# FPGA_SUP.net
KiCad netlist of a schematic drawn in Altium Designer
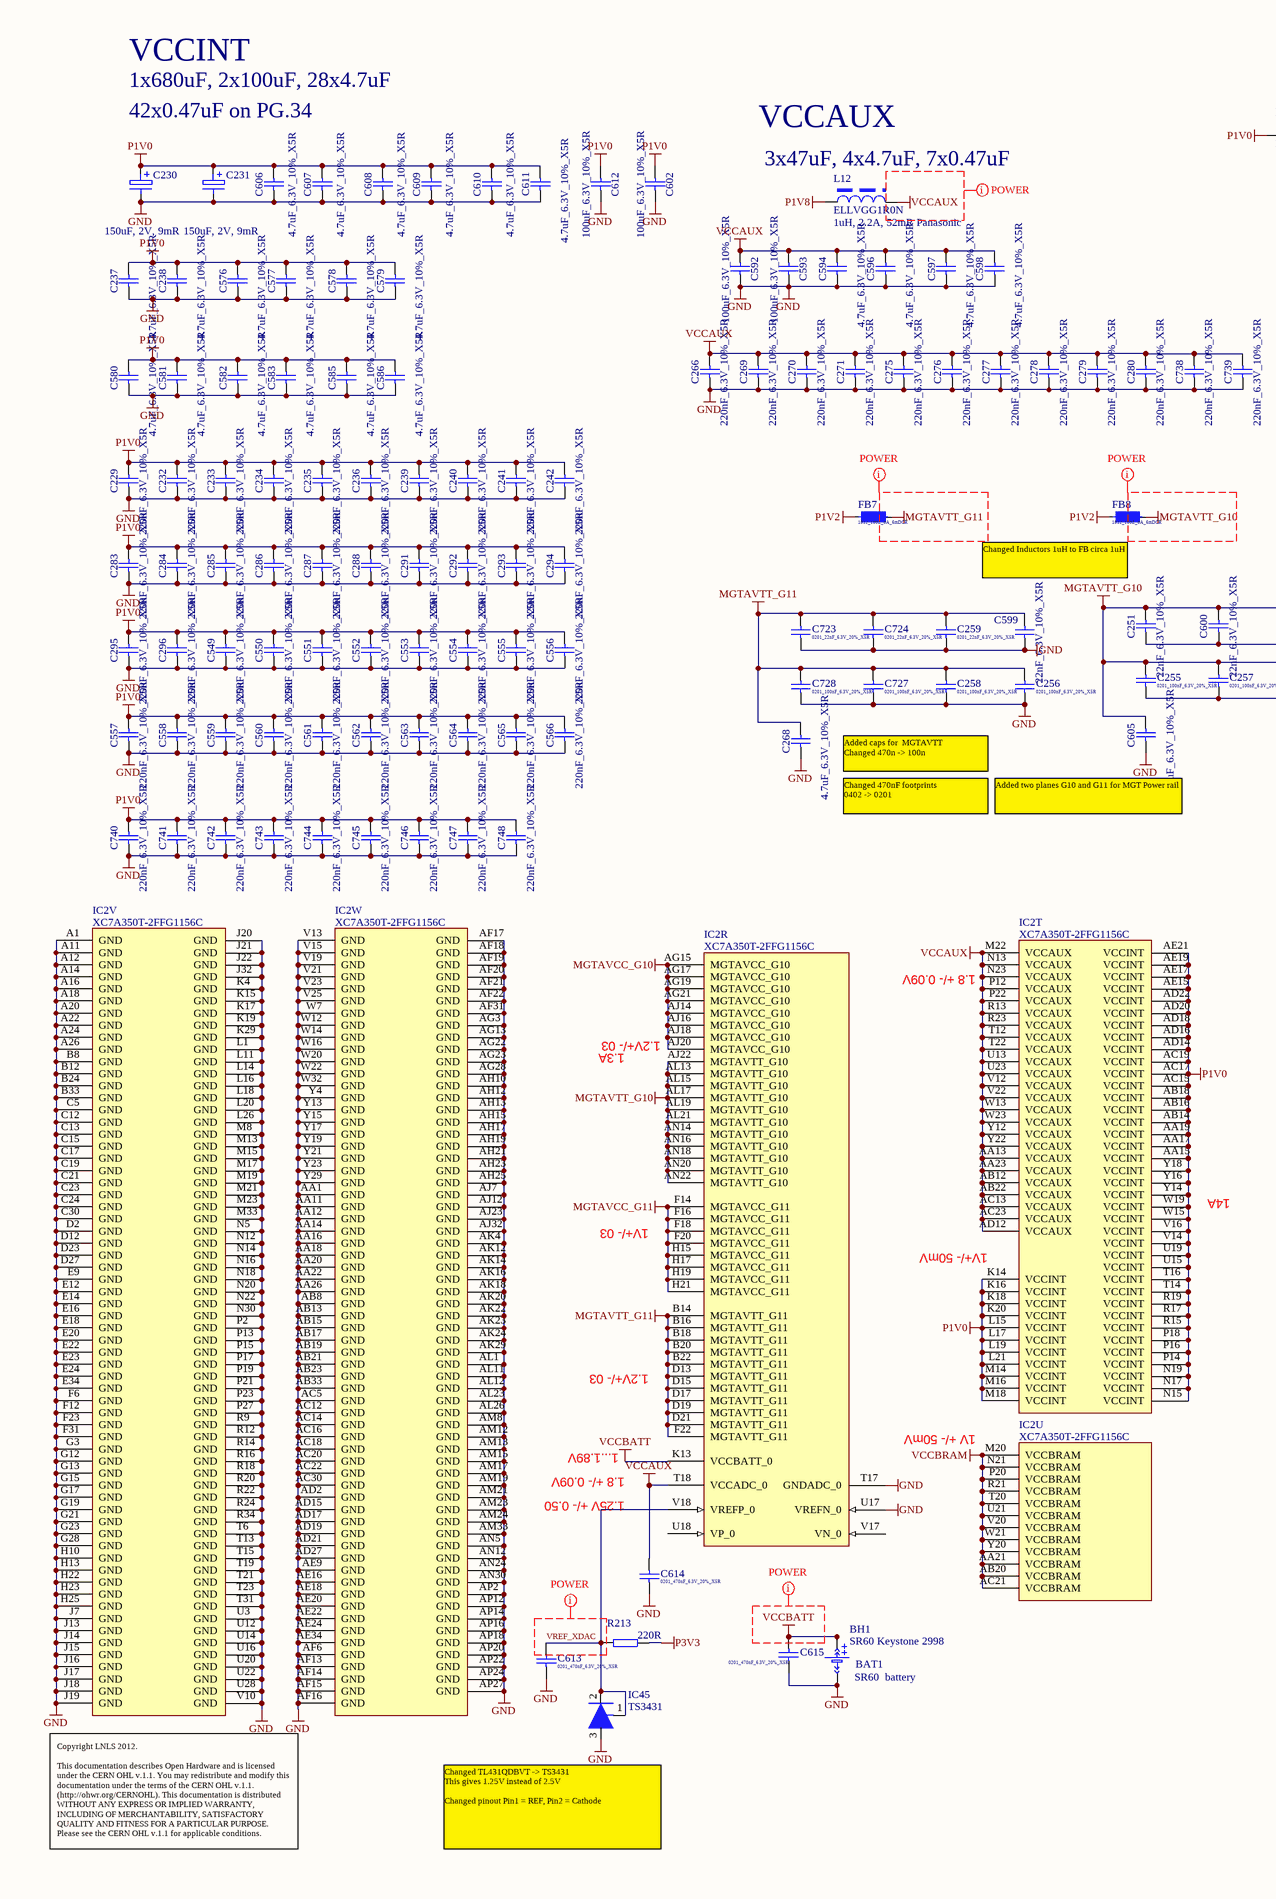
[diagram p0: FPGA_SUP.SchDoc, left]
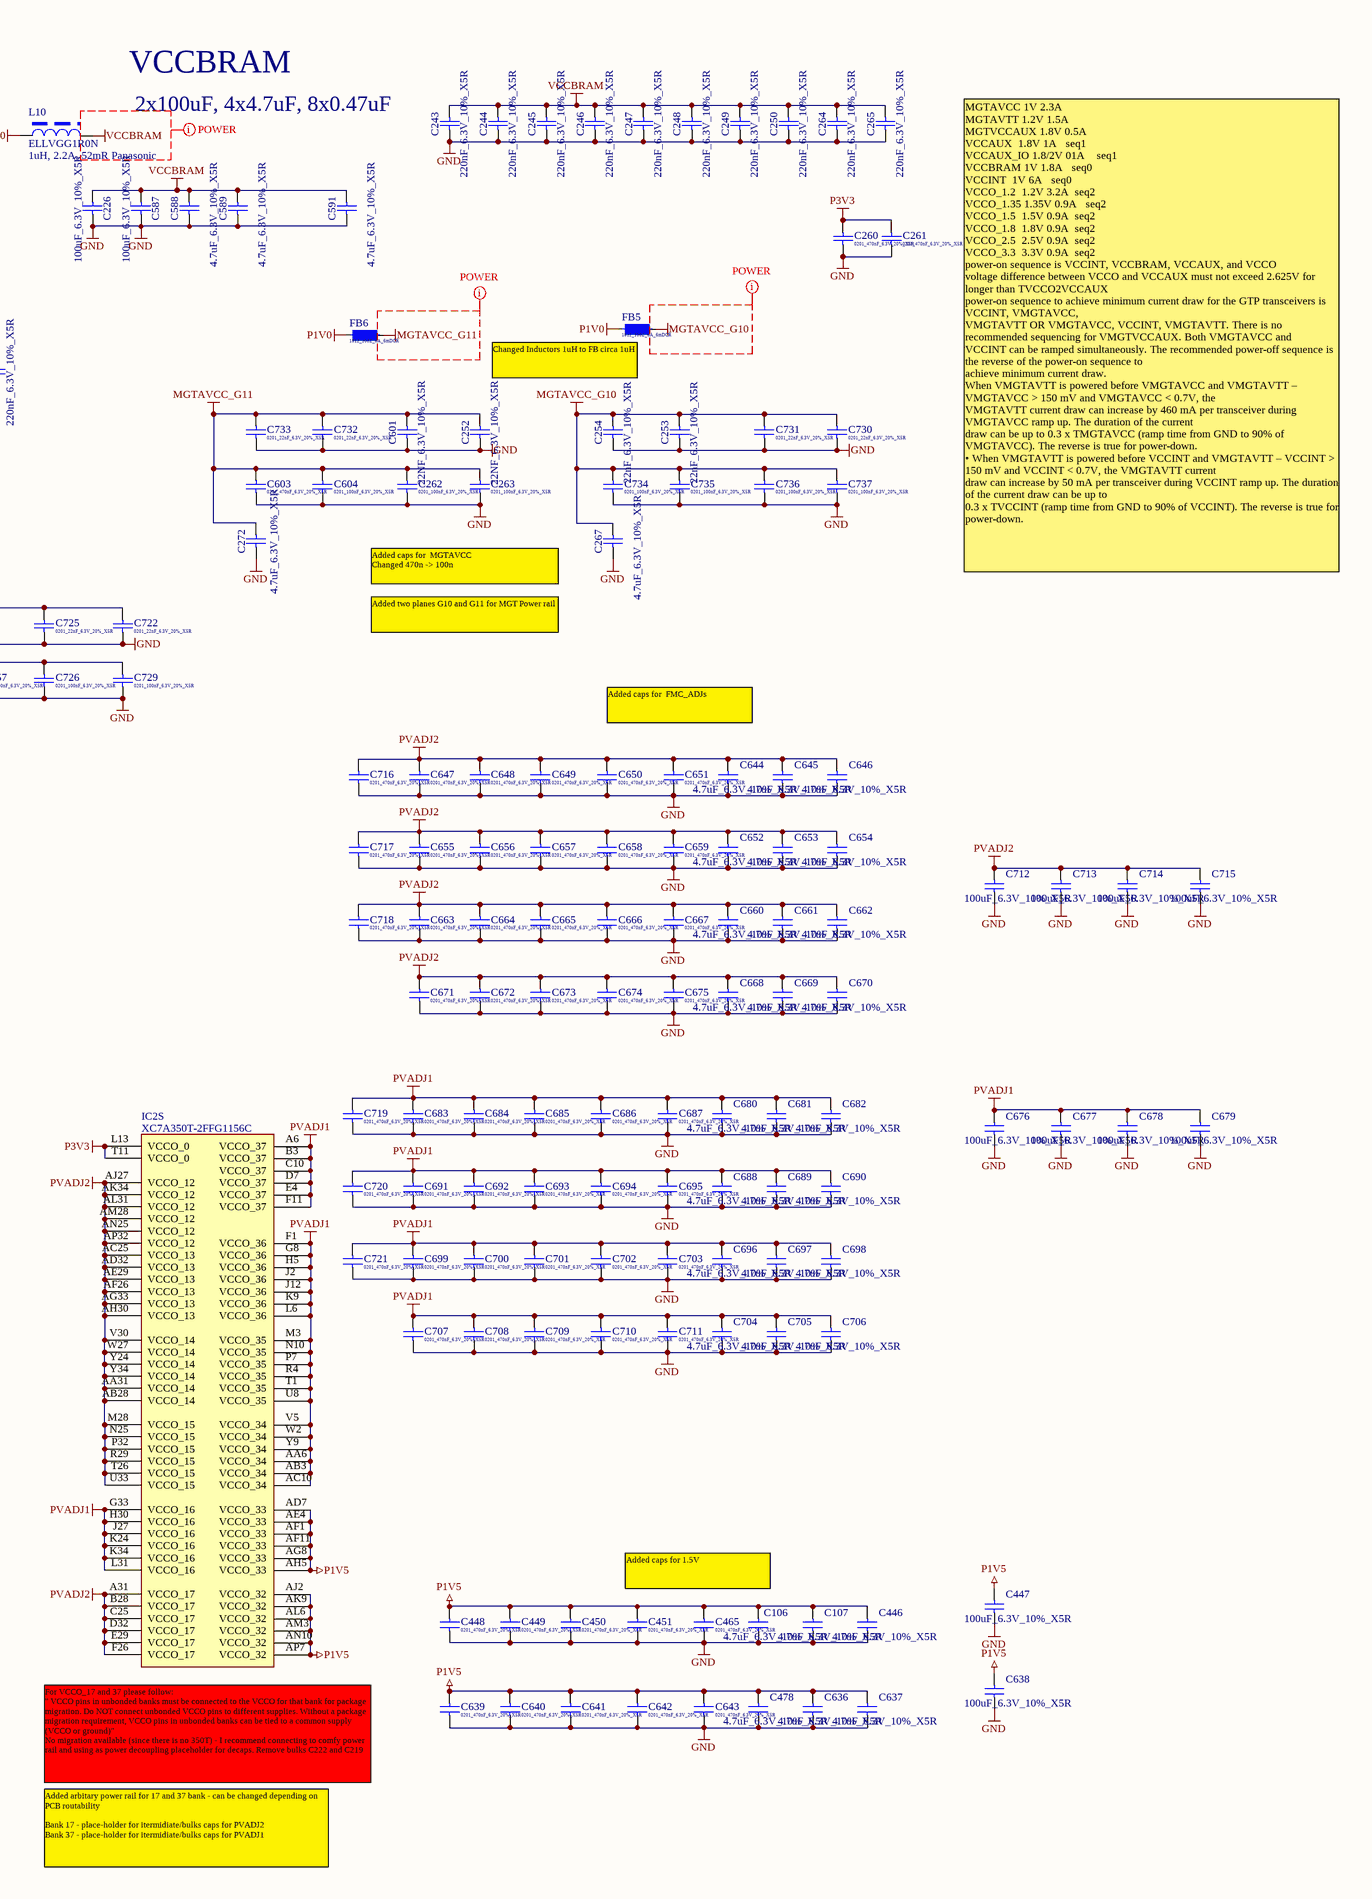
[diagram p1: FPGA_SUP.SchDoc, right]

(export (version "E")
  (design (tool "Eeschema 10.0.6"))
  (components
    (comp (ref "BAT1")
      (value "SR60  battery")
      (footprint "SR60")
      (description "SR60 6.8x2.15mm Battery 1.5V, 15mAh")
      (libsource (lib "LIBRARY_SCH") (part "BATTERY_SR60"))
    )
    (comp (ref "BH1")
      (value "SR60 Keystone 2998")
      (footprint "keystone_2998")
      (description "SR60 Battery 1.5V 17mAh (Farnell: 1854967)")
      (libsource (lib "LIBRARY_SCH") (part "BATTERY_HOLD_SR60"))
    )
    (comp (ref "C106")
      (value "4.7uF_6.3V_10%_X5R")
      (footprint "CAPC1608X87N")
      (description "Non-polarised capacitor")
      (fields
        (field (name "PART NUMBER") "CC0603_4.7UF_6.3V_10%_X5R")
        (field (name "VOLTAGE") "6.3V")
        (field (name "AUTHOR") "CERN DEM JLC")
      )
      (libsource (lib "Capacitors") (part "Capacitor - non polarized"))
    )
    (comp (ref "C107")
      (value "4.7uF_6.3V_10%_X5R")
      (footprint "CAPC1608X87N")
      (description "Non-polarised capacitor")
      (fields
        (field (name "PART NUMBER") "CC0603_4.7UF_6.3V_10%_X5R")
        (field (name "VOLTAGE") "6.3V")
        (field (name "AUTHOR") "CERN DEM JLC")
      )
      (libsource (lib "Capacitors") (part "Capacitor - non polarized"))
    )
    (comp (ref "C226")
      (value "100uF_6.3V_10%_X5R")
      (footprint "CAPC3225X270N")
      (description "Non-polarised capacitor")
      (fields
        (field (name "PART NUMBER") "CC1210_100UF_6.3V_20%_X5R")
        (field (name "VOLTAGE") "6.3V")
        (field (name "AUTHOR") "CERN DEM JLC")
      )
      (libsource (lib "Capacitors") (part "Capacitor - non polarized"))
    )
    (comp (ref "C229")
      (value "220nF_6.3V_10%_X5R")
      (footprint "CAPC0603X33N")
      (description "Non-polarised capacitor")
      (fields
        (field (name "PART NUMBER") "CC0201_220NF_6.3V_20%_X5R")
        (field (name "VOLTAGE") "6.3V")
        (field (name "AUTHOR") "CERN DEM JLC")
      )
      (libsource (lib "Capacitors") (part "Capacitor - non polarized"))
    )
    (comp (ref "C230")
      (value "150uF, 2V, 9mR")
      (footprint "2917_POLY")
      (description "POLY, 150uF, 2V, ESR: 9mR")
      (fields (field (name "Comment") "ECASD40D157M009K00"))
      (libsource (lib "LIBRARY_SCH") (part "CAP_POLYMER_SMDD"))
    )
    (comp (ref "C231")
      (value "150uF, 2V, 9mR")
      (footprint "2917_POLY")
      (description "POLY, 150uF, 2V, ESR: 9mR")
      (fields (field (name "Comment") "ECASD40D157M009K00"))
      (libsource (lib "LIBRARY_SCH") (part "CAP_POLYMER_SMDD"))
    )
    (comp (ref "C232")
      (value "220nF_6.3V_10%_X5R")
      (footprint "CAPC0603X33N")
      (description "Non-polarised capacitor")
      (fields
        (field (name "PART NUMBER") "CC0201_220NF_6.3V_20%_X5R")
        (field (name "VOLTAGE") "6.3V")
        (field (name "AUTHOR") "CERN DEM JLC")
      )
      (libsource (lib "Capacitors") (part "Capacitor - non polarized"))
    )
    (comp (ref "C233")
      (value "220nF_6.3V_10%_X5R")
      (footprint "CAPC0603X33N")
      (description "Non-polarised capacitor")
      (fields
        (field (name "PART NUMBER") "CC0201_220NF_6.3V_20%_X5R")
        (field (name "VOLTAGE") "6.3V")
        (field (name "AUTHOR") "CERN DEM JLC")
      )
      (libsource (lib "Capacitors") (part "Capacitor - non polarized"))
    )
    (comp (ref "C234")
      (value "220nF_6.3V_10%_X5R")
      (footprint "CAPC0603X33N")
      (description "Non-polarised capacitor")
      (fields
        (field (name "PART NUMBER") "CC0201_220NF_6.3V_20%_X5R")
        (field (name "VOLTAGE") "6.3V")
        (field (name "AUTHOR") "CERN DEM JLC")
      )
      (libsource (lib "Capacitors") (part "Capacitor - non polarized"))
    )
    (comp (ref "C235")
      (value "220nF_6.3V_10%_X5R")
      (footprint "CAPC0603X33N")
      (description "Non-polarised capacitor")
      (fields
        (field (name "PART NUMBER") "CC0201_220NF_6.3V_20%_X5R")
        (field (name "VOLTAGE") "6.3V")
        (field (name "AUTHOR") "CERN DEM JLC")
      )
      (libsource (lib "Capacitors") (part "Capacitor - non polarized"))
    )
    (comp (ref "C236")
      (value "220nF_6.3V_10%_X5R")
      (footprint "CAPC0603X33N")
      (description "Non-polarised capacitor")
      (fields
        (field (name "PART NUMBER") "CC0201_220NF_6.3V_20%_X5R")
        (field (name "VOLTAGE") "6.3V")
        (field (name "AUTHOR") "CERN DEM JLC")
      )
      (libsource (lib "Capacitors") (part "Capacitor - non polarized"))
    )
    (comp (ref "C237")
      (value "4.7uF_6.3V_10%_X5R")
      (footprint "CAPC1608X87N")
      (description "Non-polarised capacitor")
      (fields
        (field (name "PART NUMBER") "CC0603_4.7UF_6.3V_10%_X5R")
        (field (name "VOLTAGE") "6.3V")
        (field (name "AUTHOR") "CERN DEM JLC")
      )
      (libsource (lib "Capacitors") (part "Capacitor - non polarized"))
    )
    (comp (ref "C238")
      (value "4.7uF_6.3V_10%_X5R")
      (footprint "CAPC1608X87N")
      (description "Non-polarised capacitor")
      (fields
        (field (name "PART NUMBER") "CC0603_4.7UF_6.3V_10%_X5R")
        (field (name "VOLTAGE") "6.3V")
        (field (name "AUTHOR") "CERN DEM JLC")
      )
      (libsource (lib "Capacitors") (part "Capacitor - non polarized"))
    )
    (comp (ref "C239")
      (value "220nF_6.3V_10%_X5R")
      (footprint "CAPC0603X33N")
      (description "Non-polarised capacitor")
      (fields
        (field (name "PART NUMBER") "CC0201_220NF_6.3V_20%_X5R")
        (field (name "VOLTAGE") "6.3V")
        (field (name "AUTHOR") "CERN DEM JLC")
      )
      (libsource (lib "Capacitors") (part "Capacitor - non polarized"))
    )
    (comp (ref "C240")
      (value "220nF_6.3V_10%_X5R")
      (footprint "CAPC0603X33N")
      (description "Non-polarised capacitor")
      (fields
        (field (name "PART NUMBER") "CC0201_220NF_6.3V_20%_X5R")
        (field (name "VOLTAGE") "6.3V")
        (field (name "AUTHOR") "CERN DEM JLC")
      )
      (libsource (lib "Capacitors") (part "Capacitor - non polarized"))
    )
    (comp (ref "C241")
      (value "220nF_6.3V_10%_X5R")
      (footprint "CAPC0603X33N")
      (description "Non-polarised capacitor")
      (fields
        (field (name "PART NUMBER") "CC0201_220NF_6.3V_20%_X5R")
        (field (name "VOLTAGE") "6.3V")
        (field (name "AUTHOR") "CERN DEM JLC")
      )
      (libsource (lib "Capacitors") (part "Capacitor - non polarized"))
    )
    (comp (ref "C242")
      (value "220nF_6.3V_10%_X5R")
      (footprint "CAPC0603X33N")
      (description "Non-polarised capacitor")
      (fields
        (field (name "PART NUMBER") "CC0201_220NF_6.3V_20%_X5R")
        (field (name "VOLTAGE") "6.3V")
        (field (name "AUTHOR") "CERN DEM JLC")
      )
      (libsource (lib "Capacitors") (part "Capacitor - non polarized"))
    )
    (comp (ref "C243")
      (value "220nF_6.3V_10%_X5R")
      (footprint "CAPC0603X33N")
      (description "Non-polarised capacitor")
      (fields
        (field (name "PART NUMBER") "CC0201_220NF_6.3V_20%_X5R")
        (field (name "VOLTAGE") "6.3V")
        (field (name "AUTHOR") "CERN DEM JLC")
      )
      (libsource (lib "Capacitors") (part "Capacitor - non polarized"))
    )
    (comp (ref "C244")
      (value "220nF_6.3V_10%_X5R")
      (footprint "CAPC0603X33N")
      (description "Non-polarised capacitor")
      (fields
        (field (name "PART NUMBER") "CC0201_220NF_6.3V_20%_X5R")
        (field (name "VOLTAGE") "6.3V")
        (field (name "AUTHOR") "CERN DEM JLC")
      )
      (libsource (lib "Capacitors") (part "Capacitor - non polarized"))
    )
    (comp (ref "C245")
      (value "220nF_6.3V_10%_X5R")
      (footprint "CAPC0603X33N")
      (description "Non-polarised capacitor")
      (fields
        (field (name "PART NUMBER") "CC0201_220NF_6.3V_20%_X5R")
        (field (name "VOLTAGE") "6.3V")
        (field (name "AUTHOR") "CERN DEM JLC")
      )
      (libsource (lib "Capacitors") (part "Capacitor - non polarized"))
    )
    (comp (ref "C246")
      (value "220nF_6.3V_10%_X5R")
      (footprint "CAPC0603X33N")
      (description "Non-polarised capacitor")
      (fields
        (field (name "PART NUMBER") "CC0201_220NF_6.3V_20%_X5R")
        (field (name "VOLTAGE") "6.3V")
        (field (name "AUTHOR") "CERN DEM JLC")
      )
      (libsource (lib "Capacitors") (part "Capacitor - non polarized"))
    )
    (comp (ref "C247")
      (value "220nF_6.3V_10%_X5R")
      (footprint "CAPC0603X33N")
      (description "Non-polarised capacitor")
      (fields
        (field (name "PART NUMBER") "CC0201_220NF_6.3V_20%_X5R")
        (field (name "VOLTAGE") "6.3V")
        (field (name "AUTHOR") "CERN DEM JLC")
      )
      (libsource (lib "Capacitors") (part "Capacitor - non polarized"))
    )
    (comp (ref "C248")
      (value "220nF_6.3V_10%_X5R")
      (footprint "CAPC0603X33N")
      (description "Non-polarised capacitor")
      (fields
        (field (name "PART NUMBER") "CC0201_220NF_6.3V_20%_X5R")
        (field (name "VOLTAGE") "6.3V")
        (field (name "AUTHOR") "CERN DEM JLC")
      )
      (libsource (lib "Capacitors") (part "Capacitor - non polarized"))
    )
    (comp (ref "C249")
      (value "220nF_6.3V_10%_X5R")
      (footprint "CAPC0603X33N")
      (description "Non-polarised capacitor")
      (fields
        (field (name "PART NUMBER") "CC0201_220NF_6.3V_20%_X5R")
        (field (name "VOLTAGE") "6.3V")
        (field (name "AUTHOR") "CERN DEM JLC")
      )
      (libsource (lib "Capacitors") (part "Capacitor - non polarized"))
    )
    (comp (ref "C250")
      (value "220nF_6.3V_10%_X5R")
      (footprint "CAPC0603X33N")
      (description "Non-polarised capacitor")
      (fields
        (field (name "PART NUMBER") "CC0201_220NF_6.3V_20%_X5R")
        (field (name "VOLTAGE") "6.3V")
        (field (name "AUTHOR") "CERN DEM JLC")
      )
      (libsource (lib "Capacitors") (part "Capacitor - non polarized"))
    )
    (comp (ref "C251")
      (value "22nF_6.3V_10%_X5R")
      (footprint "CAPC0603X33N")
      (description "Non-polarised capacitor")
      (fields
        (field (name "PART NUMBER") "CC0201_22NF_6.3V_10%_X5R")
        (field (name "VOLTAGE") "6.3V")
        (field (name "AUTHOR") "CERN DEM JLC")
      )
      (libsource (lib "Capacitors") (part "Capacitor - non polarized"))
    )
    (comp (ref "C252")
      (value "22NF_6.3V_10%_X5R")
      (footprint "CAPC0603X33N")
      (description "Non-polarised capacitor")
      (fields
        (field (name "PART NUMBER") "CC0201_22NF_6.3V_10%_X5R")
        (field (name "VOLTAGE") "6.3V")
        (field (name "AUTHOR") "CERN DEM JLC")
      )
      (libsource (lib "Capacitors") (part "Capacitor - non polarized"))
    )
    (comp (ref "C253")
      (value "22nF_6.3V_10%_X5R")
      (footprint "CAPC0603X33N")
      (description "Non-polarised capacitor")
      (fields
        (field (name "PART NUMBER") "CC0201_22NF_6.3V_10%_X5R")
        (field (name "VOLTAGE") "6.3V")
        (field (name "AUTHOR") "CERN DEM JLC")
      )
      (libsource (lib "Capacitors") (part "Capacitor - non polarized"))
    )
    (comp (ref "C254")
      (value "22nF_6.3V_10%_X5R")
      (footprint "CAPC0603X33N")
      (description "Non-polarised capacitor")
      (fields
        (field (name "PART NUMBER") "CC0201_22NF_6.3V_10%_X5R")
        (field (name "VOLTAGE") "6.3V")
        (field (name "AUTHOR") "CERN DEM JLC")
      )
      (libsource (lib "Capacitors") (part "Capacitor - non polarized"))
    )
    (comp (ref "C255")
      (value "0201_100nF_6.3V_20%_X5R")
      (footprint "CAPC0603X33N")
      (fields (field (name "PART NUMBER") "Ceramic_0201"))
      (libsource (lib "Capacitors") (part "Capacitor"))
    )
    (comp (ref "C256")
      (value "0201_100nF_6.3V_20%_X5R")
      (footprint "CAPC0603X33N")
      (fields (field (name "PART NUMBER") "Ceramic_0201"))
      (libsource (lib "Capacitors") (part "Capacitor"))
    )
    (comp (ref "C257")
      (value "0201_100nF_6.3V_20%_X5R")
      (footprint "CAPC0603X33N")
      (fields (field (name "PART NUMBER") "Ceramic_0201"))
      (libsource (lib "Capacitors") (part "Capacitor"))
    )
    (comp (ref "C258")
      (value "0201_100nF_6.3V_20%_X5R")
      (footprint "CAPC0603X33N")
      (fields (field (name "PART NUMBER") "Ceramic_0201"))
      (libsource (lib "Capacitors") (part "Capacitor"))
    )
    (comp (ref "C259")
      (value "0201_22nF_6.3V_20%_X5R")
      (footprint "CAPC0603X33N")
      (fields (field (name "PART NUMBER") "Ceramic_0201"))
      (libsource (lib "Capacitors") (part "Capacitor"))
    )
    (comp (ref "C260")
      (value "0201_470nF_6.3V_20%_X5R")
      (footprint "CAPC0603X33N")
      (fields (field (name "PART NUMBER") "Ceramic_0201"))
      (libsource (lib "Capacitors") (part "Capacitor"))
    )
    (comp (ref "C261")
      (value "0201_470nF_6.3V_20%_X5R")
      (footprint "CAPC0603X33N")
      (fields (field (name "PART NUMBER") "Ceramic_0201"))
      (libsource (lib "Capacitors") (part "Capacitor"))
    )
    (comp (ref "C262")
      (value "0201_100nF_6.3V_20%_X5R")
      (footprint "CAPC0603X33N")
      (fields (field (name "PART NUMBER") "Ceramic_0201"))
      (libsource (lib "Capacitors") (part "Capacitor"))
    )
    (comp (ref "C263")
      (value "0201_100nF_6.3V_20%_X5R")
      (footprint "CAPC0603X33N")
      (fields (field (name "PART NUMBER") "Ceramic_0201"))
      (libsource (lib "Capacitors") (part "Capacitor"))
    )
    (comp (ref "C264")
      (value "220nF_6.3V_10%_X5R")
      (footprint "CAPC0603X33N")
      (description "Non-polarised capacitor")
      (fields
        (field (name "PART NUMBER") "CC0201_220NF_6.3V_20%_X5R")
        (field (name "VOLTAGE") "6.3V")
        (field (name "AUTHOR") "CERN DEM JLC")
      )
      (libsource (lib "Capacitors") (part "Capacitor - non polarized"))
    )
    (comp (ref "C265")
      (value "220nF_6.3V_10%_X5R")
      (footprint "CAPC0603X33N")
      (description "Non-polarised capacitor")
      (fields
        (field (name "PART NUMBER") "CC0201_220NF_6.3V_20%_X5R")
        (field (name "VOLTAGE") "6.3V")
        (field (name "AUTHOR") "CERN DEM JLC")
      )
      (libsource (lib "Capacitors") (part "Capacitor - non polarized"))
    )
    (comp (ref "C266")
      (value "220nF_6.3V_10%_X5R")
      (footprint "CAPC0603X33N")
      (description "Non-polarised capacitor")
      (fields
        (field (name "PART NUMBER") "CC0201_220NF_6.3V_20%_X5R")
        (field (name "VOLTAGE") "6.3V")
        (field (name "AUTHOR") "CERN DEM JLC")
      )
      (libsource (lib "Capacitors") (part "Capacitor - non polarized"))
    )
    (comp (ref "C267")
      (value "4.7uF_6.3V_10%_X5R")
      (footprint "CAPC1608X87N")
      (description "Non-polarised capacitor")
      (fields
        (field (name "PART NUMBER") "CC0603_4.7UF_6.3V_10%_X5R")
        (field (name "VOLTAGE") "6.3V")
        (field (name "AUTHOR") "CERN DEM JLC")
      )
      (libsource (lib "Capacitors") (part "Capacitor - non polarized"))
    )
    (comp (ref "C268")
      (value "4.7uF_6.3V_10%_X5R")
      (footprint "CAPC1608X87N")
      (description "Non-polarised capacitor")
      (fields
        (field (name "PART NUMBER") "CC0603_4.7UF_6.3V_10%_X5R")
        (field (name "VOLTAGE") "6.3V")
        (field (name "AUTHOR") "CERN DEM JLC")
      )
      (libsource (lib "Capacitors") (part "Capacitor - non polarized"))
    )
    (comp (ref "C269")
      (value "220nF_6.3V_10%_X5R")
      (footprint "CAPC0603X33N")
      (description "Non-polarised capacitor")
      (fields
        (field (name "PART NUMBER") "CC0201_220NF_6.3V_20%_X5R")
        (field (name "VOLTAGE") "6.3V")
        (field (name "AUTHOR") "CERN DEM JLC")
      )
      (libsource (lib "Capacitors") (part "Capacitor - non polarized"))
    )
    (comp (ref "C270")
      (value "220nF_6.3V_10%_X5R")
      (footprint "CAPC0603X33N")
      (description "Non-polarised capacitor")
      (fields
        (field (name "PART NUMBER") "CC0201_220NF_6.3V_20%_X5R")
        (field (name "VOLTAGE") "6.3V")
        (field (name "AUTHOR") "CERN DEM JLC")
      )
      (libsource (lib "Capacitors") (part "Capacitor - non polarized"))
    )
    (comp (ref "C271")
      (value "220nF_6.3V_10%_X5R")
      (footprint "CAPC0603X33N")
      (description "Non-polarised capacitor")
      (fields
        (field (name "PART NUMBER") "CC0201_220NF_6.3V_20%_X5R")
        (field (name "VOLTAGE") "6.3V")
        (field (name "AUTHOR") "CERN DEM JLC")
      )
      (libsource (lib "Capacitors") (part "Capacitor - non polarized"))
    )
    (comp (ref "C272")
      (value "4.7uF_6.3V_10%_X5R")
      (footprint "CAPC1608X87N")
      (description "Non-polarised capacitor")
      (fields
        (field (name "PART NUMBER") "CC0603_4.7UF_6.3V_10%_X5R")
        (field (name "VOLTAGE") "6.3V")
        (field (name "AUTHOR") "CERN DEM JLC")
      )
      (libsource (lib "Capacitors") (part "Capacitor - non polarized"))
    )
    (comp (ref "C275")
      (value "220nF_6.3V_10%_X5R")
      (footprint "CAPC0603X33N")
      (description "Non-polarised capacitor")
      (fields
        (field (name "PART NUMBER") "CC0201_220NF_6.3V_20%_X5R")
        (field (name "VOLTAGE") "6.3V")
        (field (name "AUTHOR") "CERN DEM JLC")
      )
      (libsource (lib "Capacitors") (part "Capacitor - non polarized"))
    )
    (comp (ref "C276")
      (value "220nF_6.3V_10%_X5R")
      (footprint "CAPC0603X33N")
      (description "Non-polarised capacitor")
      (fields
        (field (name "PART NUMBER") "CC0201_220NF_6.3V_20%_X5R")
        (field (name "VOLTAGE") "6.3V")
        (field (name "AUTHOR") "CERN DEM JLC")
      )
      (libsource (lib "Capacitors") (part "Capacitor - non polarized"))
    )
    (comp (ref "C277")
      (value "220nF_6.3V_10%_X5R")
      (footprint "CAPC0603X33N")
      (description "Non-polarised capacitor")
      (fields
        (field (name "PART NUMBER") "CC0201_220NF_6.3V_20%_X5R")
        (field (name "VOLTAGE") "6.3V")
        (field (name "AUTHOR") "CERN DEM JLC")
      )
      (libsource (lib "Capacitors") (part "Capacitor - non polarized"))
    )
    (comp (ref "C278")
      (value "220nF_6.3V_10%_X5R")
      (footprint "CAPC0603X33N")
      (description "Non-polarised capacitor")
      (fields
        (field (name "PART NUMBER") "CC0201_220NF_6.3V_20%_X5R")
        (field (name "VOLTAGE") "6.3V")
        (field (name "AUTHOR") "CERN DEM JLC")
      )
      (libsource (lib "Capacitors") (part "Capacitor - non polarized"))
    )
    (comp (ref "C279")
      (value "220nF_6.3V_10%_X5R")
      (footprint "CAPC0603X33N")
      (description "Non-polarised capacitor")
      (fields
        (field (name "PART NUMBER") "CC0201_220NF_6.3V_20%_X5R")
        (field (name "VOLTAGE") "6.3V")
        (field (name "AUTHOR") "CERN DEM JLC")
      )
      (libsource (lib "Capacitors") (part "Capacitor - non polarized"))
    )
    (comp (ref "C280")
      (value "220nF_6.3V_10%_X5R")
      (footprint "CAPC0603X33N")
      (description "Non-polarised capacitor")
      (fields
        (field (name "PART NUMBER") "CC0201_220NF_6.3V_20%_X5R")
        (field (name "VOLTAGE") "6.3V")
        (field (name "AUTHOR") "CERN DEM JLC")
      )
      (libsource (lib "Capacitors") (part "Capacitor - non polarized"))
    )
    (comp (ref "C283")
      (value "220nF_6.3V_10%_X5R")
      (footprint "CAPC0603X33N")
      (description "Non-polarised capacitor")
      (fields
        (field (name "PART NUMBER") "CC0201_220NF_6.3V_20%_X5R")
        (field (name "VOLTAGE") "6.3V")
        (field (name "AUTHOR") "CERN DEM JLC")
      )
      (libsource (lib "Capacitors") (part "Capacitor - non polarized"))
    )
    (comp (ref "C284")
      (value "220nF_6.3V_10%_X5R")
      (footprint "CAPC0603X33N")
      (description "Non-polarised capacitor")
      (fields
        (field (name "PART NUMBER") "CC0201_220NF_6.3V_20%_X5R")
        (field (name "VOLTAGE") "6.3V")
        (field (name "AUTHOR") "CERN DEM JLC")
      )
      (libsource (lib "Capacitors") (part "Capacitor - non polarized"))
    )
    (comp (ref "C285")
      (value "220nF_6.3V_10%_X5R")
      (footprint "CAPC0603X33N")
      (description "Non-polarised capacitor")
      (fields
        (field (name "PART NUMBER") "CC0201_220NF_6.3V_20%_X5R")
        (field (name "VOLTAGE") "6.3V")
        (field (name "AUTHOR") "CERN DEM JLC")
      )
      (libsource (lib "Capacitors") (part "Capacitor - non polarized"))
    )
    (comp (ref "C286")
      (value "220nF_6.3V_10%_X5R")
      (footprint "CAPC0603X33N")
      (description "Non-polarised capacitor")
      (fields
        (field (name "PART NUMBER") "CC0201_220NF_6.3V_20%_X5R")
        (field (name "VOLTAGE") "6.3V")
        (field (name "AUTHOR") "CERN DEM JLC")
      )
      (libsource (lib "Capacitors") (part "Capacitor - non polarized"))
    )
    (comp (ref "C287")
      (value "220nF_6.3V_10%_X5R")
      (footprint "CAPC0603X33N")
      (description "Non-polarised capacitor")
      (fields
        (field (name "PART NUMBER") "CC0201_220NF_6.3V_20%_X5R")
        (field (name "VOLTAGE") "6.3V")
        (field (name "AUTHOR") "CERN DEM JLC")
      )
      (libsource (lib "Capacitors") (part "Capacitor - non polarized"))
    )
    (comp (ref "C288")
      (value "220nF_6.3V_10%_X5R")
      (footprint "CAPC0603X33N")
      (description "Non-polarised capacitor")
      (fields
        (field (name "PART NUMBER") "CC0201_220NF_6.3V_20%_X5R")
        (field (name "VOLTAGE") "6.3V")
        (field (name "AUTHOR") "CERN DEM JLC")
      )
      (libsource (lib "Capacitors") (part "Capacitor - non polarized"))
    )
    (comp (ref "C291")
      (value "220nF_6.3V_10%_X5R")
      (footprint "CAPC0603X33N")
      (description "Non-polarised capacitor")
      (fields
        (field (name "PART NUMBER") "CC0201_220NF_6.3V_20%_X5R")
        (field (name "VOLTAGE") "6.3V")
        (field (name "AUTHOR") "CERN DEM JLC")
      )
      (libsource (lib "Capacitors") (part "Capacitor - non polarized"))
    )
    (comp (ref "C292")
      (value "220nF_6.3V_10%_X5R")
      (footprint "CAPC0603X33N")
      (description "Non-polarised capacitor")
      (fields
        (field (name "PART NUMBER") "CC0201_220NF_6.3V_20%_X5R")
        (field (name "VOLTAGE") "6.3V")
        (field (name "AUTHOR") "CERN DEM JLC")
      )
      (libsource (lib "Capacitors") (part "Capacitor - non polarized"))
    )
    (comp (ref "C293")
      (value "220nF_6.3V_10%_X5R")
      (footprint "CAPC0603X33N")
      (description "Non-polarised capacitor")
      (fields
        (field (name "PART NUMBER") "CC0201_220NF_6.3V_20%_X5R")
        (field (name "VOLTAGE") "6.3V")
        (field (name "AUTHOR") "CERN DEM JLC")
      )
      (libsource (lib "Capacitors") (part "Capacitor - non polarized"))
    )
    (comp (ref "C294")
      (value "220nF_6.3V_10%_X5R")
      (footprint "CAPC0603X33N")
      (description "Non-polarised capacitor")
      (fields
        (field (name "PART NUMBER") "CC0201_220NF_6.3V_20%_X5R")
        (field (name "VOLTAGE") "6.3V")
        (field (name "AUTHOR") "CERN DEM JLC")
      )
      (libsource (lib "Capacitors") (part "Capacitor - non polarized"))
    )
    (comp (ref "C295")
      (value "220nF_6.3V_10%_X5R")
      (footprint "CAPC0603X33N")
      (description "Non-polarised capacitor")
      (fields
        (field (name "PART NUMBER") "CC0201_220NF_6.3V_20%_X5R")
        (field (name "VOLTAGE") "6.3V")
        (field (name "AUTHOR") "CERN DEM JLC")
      )
      (libsource (lib "Capacitors") (part "Capacitor - non polarized"))
    )
    (comp (ref "C296")
      (value "220nF_6.3V_10%_X5R")
      (footprint "CAPC0603X33N")
      (description "Non-polarised capacitor")
      (fields
        (field (name "PART NUMBER") "CC0201_220NF_6.3V_20%_X5R")
        (field (name "VOLTAGE") "6.3V")
        (field (name "AUTHOR") "CERN DEM JLC")
      )
      (libsource (lib "Capacitors") (part "Capacitor - non polarized"))
    )
    (comp (ref "C446")
      (value "4.7uF_6.3V_10%_X5R")
      (footprint "CAPC1608X87N")
      (description "Non-polarised capacitor")
      (fields
        (field (name "PART NUMBER") "CC0603_4.7UF_6.3V_10%_X5R")
        (field (name "VOLTAGE") "6.3V")
        (field (name "AUTHOR") "CERN DEM JLC")
      )
      (libsource (lib "Capacitors") (part "Capacitor - non polarized"))
    )
    (comp (ref "C447")
      (value "100uF_6.3V_10%_X5R")
      (footprint "CAPC3225X270N")
      (description "Non-polarised capacitor")
      (fields
        (field (name "PART NUMBER") "CC1210_100UF_6.3V_20%_X5R")
        (field (name "VOLTAGE") "6.3V")
        (field (name "AUTHOR") "CERN DEM JLC")
      )
      (libsource (lib "Capacitors") (part "Capacitor - non polarized"))
    )
    (comp (ref "C448")
      (value "0201_470nF_6.3V_20%_X5R")
      (footprint "CAPC0603X33N")
      (fields (field (name "PART NUMBER") "Ceramic_0201"))
      (libsource (lib "Capacitors") (part "Capacitor"))
    )
    (comp (ref "C449")
      (value "0201_470nF_6.3V_20%_X5R")
      (footprint "CAPC0603X33N")
      (fields (field (name "PART NUMBER") "Ceramic_0201"))
      (libsource (lib "Capacitors") (part "Capacitor"))
    )
    (comp (ref "C450")
      (value "0201_470nF_6.3V_20%_X5R")
      (footprint "CAPC0603X33N")
      (fields (field (name "PART NUMBER") "Ceramic_0201"))
      (libsource (lib "Capacitors") (part "Capacitor"))
    )
    (comp (ref "C451")
      (value "0201_470nF_6.3V_20%_X5R")
      (footprint "CAPC0603X33N")
      (fields (field (name "PART NUMBER") "Ceramic_0201"))
      (libsource (lib "Capacitors") (part "Capacitor"))
    )
    (comp (ref "C465")
      (value "0201_470nF_6.3V_20%_X5R")
      (footprint "CAPC0603X33N")
      (fields (field (name "PART NUMBER") "Ceramic_0201"))
      (libsource (lib "Capacitors") (part "Capacitor"))
    )
    (comp (ref "C478")
      (value "4.7uF_6.3V_10%_X5R")
      (footprint "CAPC1608X87N")
      (description "Non-polarised capacitor")
      (fields
        (field (name "PART NUMBER") "CC0603_4.7UF_6.3V_10%_X5R")
        (field (name "VOLTAGE") "6.3V")
        (field (name "AUTHOR") "CERN DEM JLC")
      )
      (libsource (lib "Capacitors") (part "Capacitor - non polarized"))
    )
    (comp (ref "C549")
      (value "220nF_6.3V_10%_X5R")
      (footprint "CAPC0603X33N")
      (description "Non-polarised capacitor")
      (fields
        (field (name "PART NUMBER") "CC0201_220NF_6.3V_20%_X5R")
        (field (name "VOLTAGE") "6.3V")
        (field (name "AUTHOR") "CERN DEM JLC")
      )
      (libsource (lib "Capacitors") (part "Capacitor - non polarized"))
    )
    (comp (ref "C550")
      (value "220nF_6.3V_10%_X5R")
      (footprint "CAPC0603X33N")
      (description "Non-polarised capacitor")
      (fields
        (field (name "PART NUMBER") "CC0201_220NF_6.3V_20%_X5R")
        (field (name "VOLTAGE") "6.3V")
        (field (name "AUTHOR") "CERN DEM JLC")
      )
      (libsource (lib "Capacitors") (part "Capacitor - non polarized"))
    )
    (comp (ref "C551")
      (value "220nF_6.3V_10%_X5R")
      (footprint "CAPC0603X33N")
      (description "Non-polarised capacitor")
      (fields
        (field (name "PART NUMBER") "CC0201_220NF_6.3V_20%_X5R")
        (field (name "VOLTAGE") "6.3V")
        (field (name "AUTHOR") "CERN DEM JLC")
      )
      (libsource (lib "Capacitors") (part "Capacitor - non polarized"))
    )
    (comp (ref "C552")
      (value "220nF_6.3V_10%_X5R")
      (footprint "CAPC0603X33N")
      (description "Non-polarised capacitor")
      (fields
        (field (name "PART NUMBER") "CC0201_220NF_6.3V_20%_X5R")
        (field (name "VOLTAGE") "6.3V")
        (field (name "AUTHOR") "CERN DEM JLC")
      )
      (libsource (lib "Capacitors") (part "Capacitor - non polarized"))
    )
    (comp (ref "C553")
      (value "220nF_6.3V_10%_X5R")
      (footprint "CAPC0603X33N")
      (description "Non-polarised capacitor")
      (fields
        (field (name "PART NUMBER") "CC0201_220NF_6.3V_20%_X5R")
        (field (name "VOLTAGE") "6.3V")
        (field (name "AUTHOR") "CERN DEM JLC")
      )
      (libsource (lib "Capacitors") (part "Capacitor - non polarized"))
    )
    (comp (ref "C554")
      (value "220nF_6.3V_10%_X5R")
      (footprint "CAPC0603X33N")
      (description "Non-polarised capacitor")
      (fields
        (field (name "PART NUMBER") "CC0201_220NF_6.3V_20%_X5R")
        (field (name "VOLTAGE") "6.3V")
        (field (name "AUTHOR") "CERN DEM JLC")
      )
      (libsource (lib "Capacitors") (part "Capacitor - non polarized"))
    )
    (comp (ref "C555")
      (value "220nF_6.3V_10%_X5R")
      (footprint "CAPC0603X33N")
      (description "Non-polarised capacitor")
      (fields
        (field (name "PART NUMBER") "CC0201_220NF_6.3V_20%_X5R")
        (field (name "VOLTAGE") "6.3V")
        (field (name "AUTHOR") "CERN DEM JLC")
      )
      (libsource (lib "Capacitors") (part "Capacitor - non polarized"))
    )
    (comp (ref "C556")
      (value "220nF_6.3V_10%_X5R")
      (footprint "CAPC0603X33N")
      (description "Non-polarised capacitor")
      (fields
        (field (name "PART NUMBER") "CC0201_220NF_6.3V_20%_X5R")
        (field (name "VOLTAGE") "6.3V")
        (field (name "AUTHOR") "CERN DEM JLC")
      )
      (libsource (lib "Capacitors") (part "Capacitor - non polarized"))
    )
    (comp (ref "C557")
      (value "220nF_6.3V_10%_X5R")
      (footprint "CAPC0603X33N")
      (description "Non-polarised capacitor")
      (fields
        (field (name "PART NUMBER") "CC0201_220NF_6.3V_20%_X5R")
        (field (name "VOLTAGE") "6.3V")
        (field (name "AUTHOR") "CERN DEM JLC")
      )
      (libsource (lib "Capacitors") (part "Capacitor - non polarized"))
    )
    (comp (ref "C558")
      (value "220nF_6.3V_10%_X5R")
      (footprint "CAPC0603X33N")
      (description "Non-polarised capacitor")
      (fields
        (field (name "PART NUMBER") "CC0201_220NF_6.3V_20%_X5R")
        (field (name "VOLTAGE") "6.3V")
        (field (name "AUTHOR") "CERN DEM JLC")
      )
      (libsource (lib "Capacitors") (part "Capacitor - non polarized"))
    )
    (comp (ref "C559")
      (value "220nF_6.3V_10%_X5R")
      (footprint "CAPC0603X33N")
      (description "Non-polarised capacitor")
      (fields
        (field (name "PART NUMBER") "CC0201_220NF_6.3V_20%_X5R")
        (field (name "VOLTAGE") "6.3V")
        (field (name "AUTHOR") "CERN DEM JLC")
      )
      (libsource (lib "Capacitors") (part "Capacitor - non polarized"))
    )
    (comp (ref "C560")
      (value "220nF_6.3V_10%_X5R")
      (footprint "CAPC0603X33N")
      (description "Non-polarised capacitor")
      (fields
        (field (name "PART NUMBER") "CC0201_220NF_6.3V_20%_X5R")
        (field (name "VOLTAGE") "6.3V")
        (field (name "AUTHOR") "CERN DEM JLC")
      )
      (libsource (lib "Capacitors") (part "Capacitor - non polarized"))
    )
    (comp (ref "C561")
      (value "220nF_6.3V_10%_X5R")
      (footprint "CAPC0603X33N")
      (description "Non-polarised capacitor")
      (fields
        (field (name "PART NUMBER") "CC0201_220NF_6.3V_20%_X5R")
        (field (name "VOLTAGE") "6.3V")
        (field (name "AUTHOR") "CERN DEM JLC")
      )
      (libsource (lib "Capacitors") (part "Capacitor - non polarized"))
    )
    (comp (ref "C562")
      (value "220nF_6.3V_10%_X5R")
      (footprint "CAPC0603X33N")
      (description "Non-polarised capacitor")
      (fields
        (field (name "PART NUMBER") "CC0201_220NF_6.3V_20%_X5R")
        (field (name "VOLTAGE") "6.3V")
        (field (name "AUTHOR") "CERN DEM JLC")
      )
      (libsource (lib "Capacitors") (part "Capacitor - non polarized"))
    )
    (comp (ref "C563")
      (value "220nF_6.3V_10%_X5R")
      (footprint "CAPC0603X33N")
      (description "Non-polarised capacitor")
      (fields
        (field (name "PART NUMBER") "CC0201_220NF_6.3V_20%_X5R")
        (field (name "VOLTAGE") "6.3V")
        (field (name "AUTHOR") "CERN DEM JLC")
      )
      (libsource (lib "Capacitors") (part "Capacitor - non polarized"))
    )
    (comp (ref "C564")
      (value "220nF_6.3V_10%_X5R")
      (footprint "CAPC0603X33N")
      (description "Non-polarised capacitor")
      (fields
        (field (name "PART NUMBER") "CC0201_220NF_6.3V_20%_X5R")
        (field (name "VOLTAGE") "6.3V")
        (field (name "AUTHOR") "CERN DEM JLC")
      )
      (libsource (lib "Capacitors") (part "Capacitor - non polarized"))
    )
    (comp (ref "C565")
      (value "220nF_6.3V_10%_X5R")
      (footprint "CAPC0603X33N")
      (description "Non-polarised capacitor")
      (fields
        (field (name "PART NUMBER") "CC0201_220NF_6.3V_20%_X5R")
        (field (name "VOLTAGE") "6.3V")
        (field (name "AUTHOR") "CERN DEM JLC")
      )
      (libsource (lib "Capacitors") (part "Capacitor - non polarized"))
    )
    (comp (ref "C566")
      (value "220nF_6.3V_10%_X5R")
      (footprint "CAPC0603X33N")
      (description "Non-polarised capacitor")
      (fields
        (field (name "PART NUMBER") "CC0201_220NF_6.3V_20%_X5R")
        (field (name "VOLTAGE") "6.3V")
        (field (name "AUTHOR") "CERN DEM JLC")
      )
      (libsource (lib "Capacitors") (part "Capacitor - non polarized"))
    )
    (comp (ref "C576")
      (value "4.7uF_6.3V_10%_X5R")
      (footprint "CAPC1608X87N")
      (description "Non-polarised capacitor")
      (fields
        (field (name "PART NUMBER") "CC0603_4.7UF_6.3V_10%_X5R")
        (field (name "VOLTAGE") "6.3V")
        (field (name "AUTHOR") "CERN DEM JLC")
      )
      (libsource (lib "Capacitors") (part "Capacitor - non polarized"))
    )
    (comp (ref "C577")
      (value "4.7uF_6.3V_10%_X5R")
      (footprint "CAPC1608X87N")
      (description "Non-polarised capacitor")
      (fields
        (field (name "PART NUMBER") "CC0603_4.7UF_6.3V_10%_X5R")
        (field (name "VOLTAGE") "6.3V")
        (field (name "AUTHOR") "CERN DEM JLC")
      )
      (libsource (lib "Capacitors") (part "Capacitor - non polarized"))
    )
    (comp (ref "C578")
      (value "4.7uF_6.3V_10%_X5R")
      (footprint "CAPC1608X87N")
      (description "Non-polarised capacitor")
      (fields
        (field (name "PART NUMBER") "CC0603_4.7UF_6.3V_10%_X5R")
        (field (name "VOLTAGE") "6.3V")
        (field (name "AUTHOR") "CERN DEM JLC")
      )
      (libsource (lib "Capacitors") (part "Capacitor - non polarized"))
    )
    (comp (ref "C579")
      (value "4.7uF_6.3V_10%_X5R")
      (footprint "CAPC1608X87N")
      (description "Non-polarised capacitor")
      (fields
        (field (name "PART NUMBER") "CC0603_4.7UF_6.3V_10%_X5R")
        (field (name "VOLTAGE") "6.3V")
        (field (name "AUTHOR") "CERN DEM JLC")
      )
      (libsource (lib "Capacitors") (part "Capacitor - non polarized"))
    )
    (comp (ref "C580")
      (value "4.7uF_6.3V_10%_X5R")
      (footprint "CAPC1608X87N")
      (description "Non-polarised capacitor")
      (fields
        (field (name "PART NUMBER") "CC0603_4.7UF_6.3V_10%_X5R")
        (field (name "VOLTAGE") "6.3V")
        (field (name "AUTHOR") "CERN DEM JLC")
      )
      (libsource (lib "Capacitors") (part "Capacitor - non polarized"))
    )
    (comp (ref "C581")
      (value "4.7uF_6.3V_10%_X5R")
      (footprint "CAPC1608X87N")
      (description "Non-polarised capacitor")
      (fields
        (field (name "PART NUMBER") "CC0603_4.7UF_6.3V_10%_X5R")
        (field (name "VOLTAGE") "6.3V")
        (field (name "AUTHOR") "CERN DEM JLC")
      )
      (libsource (lib "Capacitors") (part "Capacitor - non polarized"))
    )
    (comp (ref "C582")
      (value "4.7uF_6.3V_10%_X5R")
      (footprint "CAPC1608X87N")
      (description "Non-polarised capacitor")
      (fields
        (field (name "PART NUMBER") "CC0603_4.7UF_6.3V_10%_X5R")
        (field (name "VOLTAGE") "6.3V")
        (field (name "AUTHOR") "CERN DEM JLC")
      )
      (libsource (lib "Capacitors") (part "Capacitor - non polarized"))
    )
    (comp (ref "C583")
      (value "4.7uF_6.3V_10%_X5R")
      (footprint "CAPC1608X87N")
      (description "Non-polarised capacitor")
      (fields
        (field (name "PART NUMBER") "CC0603_4.7UF_6.3V_10%_X5R")
        (field (name "VOLTAGE") "6.3V")
        (field (name "AUTHOR") "CERN DEM JLC")
      )
      (libsource (lib "Capacitors") (part "Capacitor - non polarized"))
    )
    (comp (ref "C585")
      (value "4.7uF_6.3V_10%_X5R")
      (footprint "CAPC1608X87N")
      (description "Non-polarised capacitor")
      (fields
        (field (name "PART NUMBER") "CC0603_4.7UF_6.3V_10%_X5R")
        (field (name "VOLTAGE") "6.3V")
        (field (name "AUTHOR") "CERN DEM JLC")
      )
      (libsource (lib "Capacitors") (part "Capacitor - non polarized"))
    )
    (comp (ref "C586")
      (value "4.7uF_6.3V_10%_X5R")
      (footprint "CAPC1608X87N")
      (description "Non-polarised capacitor")
      (fields
        (field (name "PART NUMBER") "CC0603_4.7UF_6.3V_10%_X5R")
        (field (name "VOLTAGE") "6.3V")
        (field (name "AUTHOR") "CERN DEM JLC")
      )
      (libsource (lib "Capacitors") (part "Capacitor - non polarized"))
    )
    (comp (ref "C587")
      (value "100uF_6.3V_10%_X5R")
      (footprint "CAPC3225X270N")
      (description "Non-polarised capacitor")
      (fields
        (field (name "PART NUMBER") "CC1210_100UF_6.3V_20%_X5R")
        (field (name "VOLTAGE") "6.3V")
        (field (name "AUTHOR") "CERN DEM JLC")
      )
      (libsource (lib "Capacitors") (part "Capacitor - non polarized"))
    )
    (comp (ref "C588")
      (value "4.7uF_6.3V_10%_X5R")
      (footprint "CAPC1608X87N")
      (description "Non-polarised capacitor")
      (fields
        (field (name "PART NUMBER") "CC0603_4.7UF_6.3V_10%_X5R")
        (field (name "VOLTAGE") "6.3V")
        (field (name "AUTHOR") "CERN DEM JLC")
      )
      (libsource (lib "Capacitors") (part "Capacitor - non polarized"))
    )
    (comp (ref "C589")
      (value "4.7uF_6.3V_10%_X5R")
      (footprint "CAPC1608X87N")
      (description "Non-polarised capacitor")
      (fields
        (field (name "PART NUMBER") "CC0603_4.7UF_6.3V_10%_X5R")
        (field (name "VOLTAGE") "6.3V")
        (field (name "AUTHOR") "CERN DEM JLC")
      )
      (libsource (lib "Capacitors") (part "Capacitor - non polarized"))
    )
    (comp (ref "C591")
      (value "4.7uF_6.3V_10%_X5R")
      (footprint "CAPC1608X87N")
      (description "Non-polarised capacitor")
      (fields
        (field (name "PART NUMBER") "CC0603_4.7UF_6.3V_10%_X5R")
        (field (name "VOLTAGE") "6.3V")
        (field (name "AUTHOR") "CERN DEM JLC")
      )
      (libsource (lib "Capacitors") (part "Capacitor - non polarized"))
    )
    (comp (ref "C592")
      (value "100uF_6.3V_10%_X5R")
      (footprint "CAPC3225X270N")
      (description "Non-polarised capacitor")
      (fields
        (field (name "PART NUMBER") "CC1210_100UF_6.3V_20%_X5R")
        (field (name "VOLTAGE") "6.3V")
        (field (name "AUTHOR") "CERN DEM JLC")
      )
      (libsource (lib "Capacitors") (part "Capacitor - non polarized"))
    )
    (comp (ref "C593")
      (value "100uF_6.3V_10%_X5R")
      (footprint "CAPC3225X270N")
      (description "Non-polarised capacitor")
      (fields
        (field (name "PART NUMBER") "CC1210_100UF_6.3V_20%_X5R")
        (field (name "VOLTAGE") "6.3V")
        (field (name "AUTHOR") "CERN DEM JLC")
      )
      (libsource (lib "Capacitors") (part "Capacitor - non polarized"))
    )
    (comp (ref "C594")
      (value "4.7uF_6.3V_10%_X5R")
      (footprint "CAPC1608X87N")
      (description "Non-polarised capacitor")
      (fields
        (field (name "PART NUMBER") "CC0603_4.7UF_6.3V_10%_X5R")
        (field (name "VOLTAGE") "6.3V")
        (field (name "AUTHOR") "CERN DEM JLC")
      )
      (libsource (lib "Capacitors") (part "Capacitor - non polarized"))
    )
    (comp (ref "C596")
      (value "4.7uF_6.3V_10%_X5R")
      (footprint "CAPC1608X87N")
      (description "Non-polarised capacitor")
      (fields
        (field (name "PART NUMBER") "CC0603_4.7UF_6.3V_10%_X5R")
        (field (name "VOLTAGE") "6.3V")
        (field (name "AUTHOR") "CERN DEM JLC")
      )
      (libsource (lib "Capacitors") (part "Capacitor - non polarized"))
    )
    (comp (ref "C597")
      (value "4.7uF_6.3V_10%_X5R")
      (footprint "CAPC1608X87N")
      (description "Non-polarised capacitor")
      (fields
        (field (name "PART NUMBER") "CC0603_4.7UF_6.3V_10%_X5R")
        (field (name "VOLTAGE") "6.3V")
        (field (name "AUTHOR") "CERN DEM JLC")
      )
      (libsource (lib "Capacitors") (part "Capacitor - non polarized"))
    )
    (comp (ref "C598")
      (value "4.7uF_6.3V_10%_X5R")
      (footprint "CAPC1608X87N")
      (description "Non-polarised capacitor")
      (fields
        (field (name "PART NUMBER") "CC0603_4.7UF_6.3V_10%_X5R")
        (field (name "VOLTAGE") "6.3V")
        (field (name "AUTHOR") "CERN DEM JLC")
      )
      (libsource (lib "Capacitors") (part "Capacitor - non polarized"))
    )
    (comp (ref "C599")
      (value "22nF_6.3V_10%_X5R")
      (footprint "CAPC0603X33N")
      (description "Non-polarised capacitor")
      (fields
        (field (name "PART NUMBER") "CC0201_22NF_6.3V_10%_X5R")
        (field (name "VOLTAGE") "6.3V")
        (field (name "AUTHOR") "CERN DEM JLC")
      )
      (libsource (lib "Capacitors") (part "Capacitor - non polarized"))
    )
    (comp (ref "C600")
      (value "22nF_6.3V_10%_X5R")
      (footprint "CAPC0603X33N")
      (description "Non-polarised capacitor")
      (fields
        (field (name "PART NUMBER") "CC0201_22NF_6.3V_10%_X5R")
        (field (name "VOLTAGE") "6.3V")
        (field (name "AUTHOR") "CERN DEM JLC")
      )
      (libsource (lib "Capacitors") (part "Capacitor - non polarized"))
    )
    (comp (ref "C601")
      (value "22NF_6.3V_10%_X5R")
      (footprint "CAPC0603X33N")
      (description "Non-polarised capacitor")
      (fields
        (field (name "PART NUMBER") "CC0201_22NF_6.3V_10%_X5R")
        (field (name "VOLTAGE") "6.3V")
        (field (name "AUTHOR") "CERN DEM JLC")
      )
      (libsource (lib "Capacitors") (part "Capacitor - non polarized"))
    )
    (comp (ref "C602")
      (value "100uF_6.3V_10%_X5R")
      (footprint "CAPC3225X270N")
      (description "Non-polarised capacitor")
      (fields
        (field (name "PART NUMBER") "CC1210_100UF_6.3V_20%_X5R")
        (field (name "VOLTAGE") "6.3V")
        (field (name "AUTHOR") "CERN DEM JLC")
      )
      (libsource (lib "Capacitors") (part "Capacitor - non polarized"))
    )
    (comp (ref "C603")
      (value "0201_470nF_6.3V_20%_X5R")
      (footprint "CAPC0603X33N")
      (fields (field (name "PART NUMBER") "Ceramic_0201"))
      (libsource (lib "Capacitors") (part "Capacitor"))
    )
    (comp (ref "C604")
      (value "0201_100nF_6.3V_20%_X5R")
      (footprint "CAPC0603X33N")
      (fields (field (name "PART NUMBER") "Ceramic_0201"))
      (libsource (lib "Capacitors") (part "Capacitor"))
    )
    (comp (ref "C605")
      (value "4.7uF_6.3V_10%_X5R")
      (footprint "CAPC1608X87N")
      (description "Non-polarised capacitor")
      (fields
        (field (name "PART NUMBER") "CC0603_4.7UF_6.3V_10%_X5R")
        (field (name "VOLTAGE") "6.3V")
        (field (name "AUTHOR") "CERN DEM JLC")
      )
      (libsource (lib "Capacitors") (part "Capacitor - non polarized"))
    )
    (comp (ref "C606")
      (value "4.7uF_6.3V_10%_X5R")
      (footprint "CAPC1608X87N")
      (description "Non-polarised capacitor")
      (fields
        (field (name "PART NUMBER") "CC0603_4.7UF_6.3V_10%_X5R")
        (field (name "VOLTAGE") "6.3V")
        (field (name "AUTHOR") "CERN DEM JLC")
      )
      (libsource (lib "Capacitors") (part "Capacitor - non polarized"))
    )
    (comp (ref "C607")
      (value "4.7uF_6.3V_10%_X5R")
      (footprint "CAPC1608X87N")
      (description "Non-polarised capacitor")
      (fields
        (field (name "PART NUMBER") "CC0603_4.7UF_6.3V_10%_X5R")
        (field (name "VOLTAGE") "6.3V")
        (field (name "AUTHOR") "CERN DEM JLC")
      )
      (libsource (lib "Capacitors") (part "Capacitor - non polarized"))
    )
    (comp (ref "C608")
      (value "4.7uF_6.3V_10%_X5R")
      (footprint "CAPC1608X87N")
      (description "Non-polarised capacitor")
      (fields
        (field (name "PART NUMBER") "CC0603_4.7UF_6.3V_10%_X5R")
        (field (name "VOLTAGE") "6.3V")
        (field (name "AUTHOR") "CERN DEM JLC")
      )
      (libsource (lib "Capacitors") (part "Capacitor - non polarized"))
    )
    (comp (ref "C609")
      (value "4.7uF_6.3V_10%_X5R")
      (footprint "CAPC1608X87N")
      (description "Non-polarised capacitor")
      (fields
        (field (name "PART NUMBER") "CC0603_4.7UF_6.3V_10%_X5R")
        (field (name "VOLTAGE") "6.3V")
        (field (name "AUTHOR") "CERN DEM JLC")
      )
      (libsource (lib "Capacitors") (part "Capacitor - non polarized"))
    )
    (comp (ref "C610")
      (value "4.7uF_6.3V_10%_X5R")
      (footprint "CAPC1608X87N")
      (description "Non-polarised capacitor")
      (fields
        (field (name "PART NUMBER") "CC0603_4.7UF_6.3V_10%_X5R")
        (field (name "VOLTAGE") "6.3V")
        (field (name "AUTHOR") "CERN DEM JLC")
      )
      (libsource (lib "Capacitors") (part "Capacitor - non polarized"))
    )
    (comp (ref "C611")
      (value "4.7uF_6.3V_10%_X5R")
      (footprint "CAPC1608X87N")
      (description "Non-polarised capacitor")
      (fields
        (field (name "PART NUMBER") "CC0603_4.7UF_6.3V_10%_X5R")
        (field (name "VOLTAGE") "6.3V")
        (field (name "AUTHOR") "CERN DEM JLC")
      )
      (libsource (lib "Capacitors") (part "Capacitor - non polarized"))
    )
    (comp (ref "C612")
      (value "100uF_6.3V_10%_X5R")
      (footprint "CAPC3225X270N")
      (description "Non-polarised capacitor")
      (fields
        (field (name "PART NUMBER") "CC1210_100UF_6.3V_20%_X5R")
        (field (name "VOLTAGE") "6.3V")
        (field (name "AUTHOR") "CERN DEM JLC")
      )
      (libsource (lib "Capacitors") (part "Capacitor - non polarized"))
    )
    (comp (ref "C613")
      (value "0201_470nF_6.3V_20%_X5R")
      (footprint "CAPC0603X33N")
      (fields (field (name "PART NUMBER") "Ceramic_0201"))
      (libsource (lib "Capacitors") (part "Capacitor"))
    )
    (comp (ref "C614")
      (value "0201_470nF_6.3V_20%_X5R")
      (footprint "CAPC0603X33N")
      (fields (field (name "PART NUMBER") "Ceramic_0201"))
      (libsource (lib "Capacitors") (part "Capacitor"))
    )
    (comp (ref "C615")
      (value "0201_470nF_6.3V_20%_X5R")
      (footprint "CAPC0603X33N")
      (fields (field (name "PART NUMBER") "Ceramic_0201"))
      (libsource (lib "Capacitors") (part "Capacitor"))
    )
    (comp (ref "C636")
      (value "4.7uF_6.3V_10%_X5R")
      (footprint "CAPC1608X87N")
      (description "Non-polarised capacitor")
      (fields
        (field (name "PART NUMBER") "CC0603_4.7UF_6.3V_10%_X5R")
        (field (name "VOLTAGE") "6.3V")
        (field (name "AUTHOR") "CERN DEM JLC")
      )
      (libsource (lib "Capacitors") (part "Capacitor - non polarized"))
    )
    (comp (ref "C637")
      (value "4.7uF_6.3V_10%_X5R")
      (footprint "CAPC1608X87N")
      (description "Non-polarised capacitor")
      (fields
        (field (name "PART NUMBER") "CC0603_4.7UF_6.3V_10%_X5R")
        (field (name "VOLTAGE") "6.3V")
        (field (name "AUTHOR") "CERN DEM JLC")
      )
      (libsource (lib "Capacitors") (part "Capacitor - non polarized"))
    )
    (comp (ref "C638")
      (value "100uF_6.3V_10%_X5R")
      (footprint "CAPC3225X270N")
      (description "Non-polarised capacitor")
      (fields
        (field (name "PART NUMBER") "CC1210_100UF_6.3V_20%_X5R")
        (field (name "VOLTAGE") "6.3V")
        (field (name "AUTHOR") "CERN DEM JLC")
      )
      (libsource (lib "Capacitors") (part "Capacitor - non polarized"))
    )
    (comp (ref "C639")
      (value "0201_470nF_6.3V_20%_X5R")
      (footprint "CAPC0603X33N")
      (fields (field (name "PART NUMBER") "Ceramic_0201"))
      (libsource (lib "Capacitors") (part "Capacitor"))
    )
    (comp (ref "C640")
      (value "0201_470nF_6.3V_20%_X5R")
      (footprint "CAPC0603X33N")
      (fields (field (name "PART NUMBER") "Ceramic_0201"))
      (libsource (lib "Capacitors") (part "Capacitor"))
    )
    (comp (ref "C641")
      (value "0201_470nF_6.3V_20%_X5R")
      (footprint "CAPC0603X33N")
      (fields (field (name "PART NUMBER") "Ceramic_0201"))
      (libsource (lib "Capacitors") (part "Capacitor"))
    )
    (comp (ref "C642")
      (value "0201_470nF_6.3V_20%_X5R")
      (footprint "CAPC0603X33N")
      (fields (field (name "PART NUMBER") "Ceramic_0201"))
      (libsource (lib "Capacitors") (part "Capacitor"))
    )
    (comp (ref "C643")
      (value "0201_470nF_6.3V_20%_X5R")
      (footprint "CAPC0603X33N")
      (fields (field (name "PART NUMBER") "Ceramic_0201"))
      (libsource (lib "Capacitors") (part "Capacitor"))
    )
    (comp (ref "C644")
      (value "4.7uF_6.3V_10%_X5R")
      (footprint "CAPC1608X87N")
      (description "Non-polarised capacitor")
      (fields
        (field (name "PART NUMBER") "CC0603_4.7UF_6.3V_10%_X5R")
        (field (name "VOLTAGE") "6.3V")
        (field (name "AUTHOR") "CERN DEM JLC")
      )
      (libsource (lib "Capacitors") (part "Capacitor - non polarized"))
    )
    (comp (ref "C645")
      (value "4.7uF_6.3V_10%_X5R")
      (footprint "CAPC1608X87N")
      (description "Non-polarised capacitor")
      (fields
        (field (name "PART NUMBER") "CC0603_4.7UF_6.3V_10%_X5R")
        (field (name "VOLTAGE") "6.3V")
        (field (name "AUTHOR") "CERN DEM JLC")
      )
      (libsource (lib "Capacitors") (part "Capacitor - non polarized"))
    )
    (comp (ref "C646")
      (value "4.7uF_6.3V_10%_X5R")
      (footprint "CAPC1608X87N")
      (description "Non-polarised capacitor")
      (fields
        (field (name "PART NUMBER") "CC0603_4.7UF_6.3V_10%_X5R")
        (field (name "VOLTAGE") "6.3V")
        (field (name "AUTHOR") "CERN DEM JLC")
      )
      (libsource (lib "Capacitors") (part "Capacitor - non polarized"))
    )
    (comp (ref "C647")
      (value "0201_470nF_6.3V_20%_X5R")
      (footprint "CAPC0603X33N")
      (fields (field (name "PART NUMBER") "Ceramic_0201"))
      (libsource (lib "Capacitors") (part "Capacitor"))
    )
    (comp (ref "C648")
      (value "0201_470nF_6.3V_20%_X5R")
      (footprint "CAPC0603X33N")
      (fields (field (name "PART NUMBER") "Ceramic_0201"))
      (libsource (lib "Capacitors") (part "Capacitor"))
    )
    (comp (ref "C649")
      (value "0201_470nF_6.3V_20%_X5R")
      (footprint "CAPC0603X33N")
      (fields (field (name "PART NUMBER") "Ceramic_0201"))
      (libsource (lib "Capacitors") (part "Capacitor"))
    )
    (comp (ref "C650")
      (value "0201_470nF_6.3V_20%_X5R")
      (footprint "CAPC0603X33N")
      (fields (field (name "PART NUMBER") "Ceramic_0201"))
      (libsource (lib "Capacitors") (part "Capacitor"))
    )
    (comp (ref "C651")
      (value "0201_470nF_6.3V_20%_X5R")
      (footprint "CAPC0603X33N")
      (fields (field (name "PART NUMBER") "Ceramic_0201"))
      (libsource (lib "Capacitors") (part "Capacitor"))
    )
    (comp (ref "C652")
      (value "4.7uF_6.3V_10%_X5R")
      (footprint "CAPC1608X87N")
      (description "Non-polarised capacitor")
      (fields
        (field (name "PART NUMBER") "CC0603_4.7UF_6.3V_10%_X5R")
        (field (name "VOLTAGE") "6.3V")
        (field (name "AUTHOR") "CERN DEM JLC")
      )
      (libsource (lib "Capacitors") (part "Capacitor - non polarized"))
    )
    (comp (ref "C653")
      (value "4.7uF_6.3V_10%_X5R")
      (footprint "CAPC1608X87N")
      (description "Non-polarised capacitor")
      (fields
        (field (name "PART NUMBER") "CC0603_4.7UF_6.3V_10%_X5R")
        (field (name "VOLTAGE") "6.3V")
        (field (name "AUTHOR") "CERN DEM JLC")
      )
      (libsource (lib "Capacitors") (part "Capacitor - non polarized"))
    )
    (comp (ref "C654")
      (value "4.7uF_6.3V_10%_X5R")
      (footprint "CAPC1608X87N")
      (description "Non-polarised capacitor")
      (fields
        (field (name "PART NUMBER") "CC0603_4.7UF_6.3V_10%_X5R")
        (field (name "VOLTAGE") "6.3V")
        (field (name "AUTHOR") "CERN DEM JLC")
      )
      (libsource (lib "Capacitors") (part "Capacitor - non polarized"))
    )
    (comp (ref "C655")
      (value "0201_470nF_6.3V_20%_X5R")
      (footprint "CAPC0603X33N")
      (fields (field (name "PART NUMBER") "Ceramic_0201"))
      (libsource (lib "Capacitors") (part "Capacitor"))
    )
    (comp (ref "C656")
      (value "0201_470nF_6.3V_20%_X5R")
      (footprint "CAPC0603X33N")
      (fields (field (name "PART NUMBER") "Ceramic_0201"))
      (libsource (lib "Capacitors") (part "Capacitor"))
    )
    (comp (ref "C657")
      (value "0201_470nF_6.3V_20%_X5R")
      (footprint "CAPC0603X33N")
      (fields (field (name "PART NUMBER") "Ceramic_0201"))
      (libsource (lib "Capacitors") (part "Capacitor"))
    )
    (comp (ref "C658")
      (value "0201_470nF_6.3V_20%_X5R")
      (footprint "CAPC0603X33N")
      (fields (field (name "PART NUMBER") "Ceramic_0201"))
      (libsource (lib "Capacitors") (part "Capacitor"))
    )
    (comp (ref "C659")
      (value "0201_470nF_6.3V_20%_X5R")
      (footprint "CAPC0603X33N")
      (fields (field (name "PART NUMBER") "Ceramic_0201"))
      (libsource (lib "Capacitors") (part "Capacitor"))
    )
    (comp (ref "C660")
      (value "4.7uF_6.3V_10%_X5R")
      (footprint "CAPC1608X87N")
      (description "Non-polarised capacitor")
      (fields
        (field (name "PART NUMBER") "CC0603_4.7UF_6.3V_10%_X5R")
        (field (name "VOLTAGE") "6.3V")
        (field (name "AUTHOR") "CERN DEM JLC")
      )
      (libsource (lib "Capacitors") (part "Capacitor - non polarized"))
    )
    (comp (ref "C661")
      (value "4.7uF_6.3V_10%_X5R")
      (footprint "CAPC1608X87N")
      (description "Non-polarised capacitor")
      (fields
        (field (name "PART NUMBER") "CC0603_4.7UF_6.3V_10%_X5R")
        (field (name "VOLTAGE") "6.3V")
        (field (name "AUTHOR") "CERN DEM JLC")
      )
      (libsource (lib "Capacitors") (part "Capacitor - non polarized"))
    )
    (comp (ref "C662")
      (value "4.7uF_6.3V_10%_X5R")
      (footprint "CAPC1608X87N")
      (description "Non-polarised capacitor")
      (fields
        (field (name "PART NUMBER") "CC0603_4.7UF_6.3V_10%_X5R")
        (field (name "VOLTAGE") "6.3V")
        (field (name "AUTHOR") "CERN DEM JLC")
      )
      (libsource (lib "Capacitors") (part "Capacitor - non polarized"))
    )
    (comp (ref "C663")
      (value "0201_470nF_6.3V_20%_X5R")
      (footprint "CAPC0603X33N")
      (fields (field (name "PART NUMBER") "Ceramic_0201"))
      (libsource (lib "Capacitors") (part "Capacitor"))
    )
    (comp (ref "C664")
      (value "0201_470nF_6.3V_20%_X5R")
      (footprint "CAPC0603X33N")
      (fields (field (name "PART NUMBER") "Ceramic_0201"))
      (libsource (lib "Capacitors") (part "Capacitor"))
    )
    (comp (ref "C665")
      (value "0201_470nF_6.3V_20%_X5R")
      (footprint "CAPC0603X33N")
      (fields (field (name "PART NUMBER") "Ceramic_0201"))
      (libsource (lib "Capacitors") (part "Capacitor"))
    )
    (comp (ref "C666")
      (value "0201_470nF_6.3V_20%_X5R")
      (footprint "CAPC0603X33N")
      (fields (field (name "PART NUMBER") "Ceramic_0201"))
      (libsource (lib "Capacitors") (part "Capacitor"))
    )
    (comp (ref "C667")
      (value "0201_470nF_6.3V_20%_X5R")
      (footprint "CAPC0603X33N")
      (fields (field (name "PART NUMBER") "Ceramic_0201"))
      (libsource (lib "Capacitors") (part "Capacitor"))
    )
    (comp (ref "C668")
      (value "4.7uF_6.3V_10%_X5R")
      (footprint "CAPC1608X87N")
      (description "Non-polarised capacitor")
      (fields
        (field (name "PART NUMBER") "CC0603_4.7UF_6.3V_10%_X5R")
        (field (name "VOLTAGE") "6.3V")
        (field (name "AUTHOR") "CERN DEM JLC")
      )
      (libsource (lib "Capacitors") (part "Capacitor - non polarized"))
    )
    (comp (ref "C669")
      (value "4.7uF_6.3V_10%_X5R")
      (footprint "CAPC1608X87N")
      (description "Non-polarised capacitor")
      (fields
        (field (name "PART NUMBER") "CC0603_4.7UF_6.3V_10%_X5R")
        (field (name "VOLTAGE") "6.3V")
        (field (name "AUTHOR") "CERN DEM JLC")
      )
      (libsource (lib "Capacitors") (part "Capacitor - non polarized"))
    )
    (comp (ref "C670")
      (value "4.7uF_6.3V_10%_X5R")
      (footprint "CAPC1608X87N")
      (description "Non-polarised capacitor")
      (fields
        (field (name "PART NUMBER") "CC0603_4.7UF_6.3V_10%_X5R")
        (field (name "VOLTAGE") "6.3V")
        (field (name "AUTHOR") "CERN DEM JLC")
      )
      (libsource (lib "Capacitors") (part "Capacitor - non polarized"))
    )
    (comp (ref "C671")
      (value "0201_470nF_6.3V_20%_X5R")
      (footprint "CAPC0603X33N")
      (fields (field (name "PART NUMBER") "Ceramic_0201"))
      (libsource (lib "Capacitors") (part "Capacitor"))
    )
    (comp (ref "C672")
      (value "0201_470nF_6.3V_20%_X5R")
      (footprint "CAPC0603X33N")
      (fields (field (name "PART NUMBER") "Ceramic_0201"))
      (libsource (lib "Capacitors") (part "Capacitor"))
    )
    (comp (ref "C673")
      (value "0201_470nF_6.3V_20%_X5R")
      (footprint "CAPC0603X33N")
      (fields (field (name "PART NUMBER") "Ceramic_0201"))
      (libsource (lib "Capacitors") (part "Capacitor"))
    )
    (comp (ref "C674")
      (value "0201_470nF_6.3V_20%_X5R")
      (footprint "CAPC0603X33N")
      (fields (field (name "PART NUMBER") "Ceramic_0201"))
      (libsource (lib "Capacitors") (part "Capacitor"))
    )
    (comp (ref "C675")
      (value "0201_470nF_6.3V_20%_X5R")
      (footprint "CAPC0603X33N")
      (fields (field (name "PART NUMBER") "Ceramic_0201"))
      (libsource (lib "Capacitors") (part "Capacitor"))
    )
    (comp (ref "C676")
      (value "100uF_6.3V_10%_X5R")
      (footprint "CAPC3225X270N")
      (description "Non-polarised capacitor")
      (fields
        (field (name "PART NUMBER") "CC1210_100UF_6.3V_20%_X5R")
        (field (name "VOLTAGE") "6.3V")
        (field (name "AUTHOR") "CERN DEM JLC")
      )
      (libsource (lib "Capacitors") (part "Capacitor - non polarized"))
    )
    (comp (ref "C677")
      (value "100uF_6.3V_10%_X5R")
      (footprint "CAPC3225X270N")
      (description "Non-polarised capacitor")
      (fields
        (field (name "PART NUMBER") "CC1210_100UF_6.3V_20%_X5R")
        (field (name "VOLTAGE") "6.3V")
        (field (name "AUTHOR") "CERN DEM JLC")
      )
      (libsource (lib "Capacitors") (part "Capacitor - non polarized"))
    )
    (comp (ref "C678")
      (value "100uF_6.3V_10%_X5R")
      (footprint "CAPC3225X270N")
      (description "Non-polarised capacitor")
      (fields
        (field (name "PART NUMBER") "CC1210_100UF_6.3V_20%_X5R")
        (field (name "VOLTAGE") "6.3V")
        (field (name "AUTHOR") "CERN DEM JLC")
      )
      (libsource (lib "Capacitors") (part "Capacitor - non polarized"))
    )
    (comp (ref "C679")
      (value "100uF_6.3V_10%_X5R")
      (footprint "CAPC3225X270N")
      (description "Non-polarised capacitor")
      (fields
        (field (name "PART NUMBER") "CC1210_100UF_6.3V_20%_X5R")
        (field (name "VOLTAGE") "6.3V")
        (field (name "AUTHOR") "CERN DEM JLC")
      )
      (libsource (lib "Capacitors") (part "Capacitor - non polarized"))
    )
    (comp (ref "C680")
      (value "4.7uF_6.3V_10%_X5R")
      (footprint "CAPC1608X87N")
      (description "Non-polarised capacitor")
      (fields
        (field (name "PART NUMBER") "CC0603_4.7UF_6.3V_10%_X5R")
        (field (name "VOLTAGE") "6.3V")
        (field (name "AUTHOR") "CERN DEM JLC")
      )
      (libsource (lib "Capacitors") (part "Capacitor - non polarized"))
    )
    (comp (ref "C681")
      (value "4.7uF_6.3V_10%_X5R")
      (footprint "CAPC1608X87N")
      (description "Non-polarised capacitor")
      (fields
        (field (name "PART NUMBER") "CC0603_4.7UF_6.3V_10%_X5R")
        (field (name "VOLTAGE") "6.3V")
        (field (name "AUTHOR") "CERN DEM JLC")
      )
      (libsource (lib "Capacitors") (part "Capacitor - non polarized"))
    )
    (comp (ref "C682")
      (value "4.7uF_6.3V_10%_X5R")
      (footprint "CAPC1608X87N")
      (description "Non-polarised capacitor")
      (fields
        (field (name "PART NUMBER") "CC0603_4.7UF_6.3V_10%_X5R")
        (field (name "VOLTAGE") "6.3V")
        (field (name "AUTHOR") "CERN DEM JLC")
      )
      (libsource (lib "Capacitors") (part "Capacitor - non polarized"))
    )
    (comp (ref "C683")
      (value "0201_470nF_6.3V_20%_X5R")
      (footprint "CAPC0603X33N")
      (fields (field (name "PART NUMBER") "Ceramic_0201"))
      (libsource (lib "Capacitors") (part "Capacitor"))
    )
    (comp (ref "C684")
      (value "0201_470nF_6.3V_20%_X5R")
      (footprint "CAPC0603X33N")
      (fields (field (name "PART NUMBER") "Ceramic_0201"))
      (libsource (lib "Capacitors") (part "Capacitor"))
    )
    (comp (ref "C685")
      (value "0201_470nF_6.3V_20%_X5R")
      (footprint "CAPC0603X33N")
      (fields (field (name "PART NUMBER") "Ceramic_0201"))
      (libsource (lib "Capacitors") (part "Capacitor"))
    )
    (comp (ref "C686")
      (value "0201_470nF_6.3V_20%_X5R")
      (footprint "CAPC0603X33N")
      (fields (field (name "PART NUMBER") "Ceramic_0201"))
      (libsource (lib "Capacitors") (part "Capacitor"))
    )
    (comp (ref "C687")
      (value "0201_470nF_6.3V_20%_X5R")
      (footprint "CAPC0603X33N")
      (fields (field (name "PART NUMBER") "Ceramic_0201"))
      (libsource (lib "Capacitors") (part "Capacitor"))
    )
    (comp (ref "C688")
      (value "4.7uF_6.3V_10%_X5R")
      (footprint "CAPC1608X87N")
      (description "Non-polarised capacitor")
      (fields
        (field (name "PART NUMBER") "CC0603_4.7UF_6.3V_10%_X5R")
        (field (name "VOLTAGE") "6.3V")
        (field (name "AUTHOR") "CERN DEM JLC")
      )
      (libsource (lib "Capacitors") (part "Capacitor - non polarized"))
    )
    (comp (ref "C689")
      (value "4.7uF_6.3V_10%_X5R")
      (footprint "CAPC1608X87N")
      (description "Non-polarised capacitor")
      (fields
        (field (name "PART NUMBER") "CC0603_4.7UF_6.3V_10%_X5R")
        (field (name "VOLTAGE") "6.3V")
        (field (name "AUTHOR") "CERN DEM JLC")
      )
      (libsource (lib "Capacitors") (part "Capacitor - non polarized"))
    )
    (comp (ref "C690")
      (value "4.7uF_6.3V_10%_X5R")
      (footprint "CAPC1608X87N")
      (description "Non-polarised capacitor")
      (fields
        (field (name "PART NUMBER") "CC0603_4.7UF_6.3V_10%_X5R")
        (field (name "VOLTAGE") "6.3V")
        (field (name "AUTHOR") "CERN DEM JLC")
      )
      (libsource (lib "Capacitors") (part "Capacitor - non polarized"))
    )
    (comp (ref "C691")
      (value "0201_470nF_6.3V_20%_X5R")
      (footprint "CAPC0603X33N")
      (fields (field (name "PART NUMBER") "Ceramic_0201"))
      (libsource (lib "Capacitors") (part "Capacitor"))
    )
    (comp (ref "C692")
      (value "0201_470nF_6.3V_20%_X5R")
      (footprint "CAPC0603X33N")
      (fields (field (name "PART NUMBER") "Ceramic_0201"))
      (libsource (lib "Capacitors") (part "Capacitor"))
    )
    (comp (ref "C693")
      (value "0201_470nF_6.3V_20%_X5R")
      (footprint "CAPC0603X33N")
      (fields (field (name "PART NUMBER") "Ceramic_0201"))
      (libsource (lib "Capacitors") (part "Capacitor"))
    )
    (comp (ref "C694")
      (value "0201_470nF_6.3V_20%_X5R")
      (footprint "CAPC0603X33N")
      (fields (field (name "PART NUMBER") "Ceramic_0201"))
      (libsource (lib "Capacitors") (part "Capacitor"))
    )
    (comp (ref "C695")
      (value "0201_470nF_6.3V_20%_X5R")
      (footprint "CAPC0603X33N")
      (fields (field (name "PART NUMBER") "Ceramic_0201"))
      (libsource (lib "Capacitors") (part "Capacitor"))
    )
    (comp (ref "C696")
      (value "4.7uF_6.3V_10%_X5R")
      (footprint "CAPC1608X87N")
      (description "Non-polarised capacitor")
      (fields
        (field (name "PART NUMBER") "CC0603_4.7UF_6.3V_10%_X5R")
        (field (name "VOLTAGE") "6.3V")
        (field (name "AUTHOR") "CERN DEM JLC")
      )
      (libsource (lib "Capacitors") (part "Capacitor - non polarized"))
    )
    (comp (ref "C697")
      (value "4.7uF_6.3V_10%_X5R")
      (footprint "CAPC1608X87N")
      (description "Non-polarised capacitor")
      (fields
        (field (name "PART NUMBER") "CC0603_4.7UF_6.3V_10%_X5R")
        (field (name "VOLTAGE") "6.3V")
        (field (name "AUTHOR") "CERN DEM JLC")
      )
      (libsource (lib "Capacitors") (part "Capacitor - non polarized"))
    )
    (comp (ref "C698")
      (value "4.7uF_6.3V_10%_X5R")
      (footprint "CAPC1608X87N")
      (description "Non-polarised capacitor")
      (fields
        (field (name "PART NUMBER") "CC0603_4.7UF_6.3V_10%_X5R")
        (field (name "VOLTAGE") "6.3V")
        (field (name "AUTHOR") "CERN DEM JLC")
      )
      (libsource (lib "Capacitors") (part "Capacitor - non polarized"))
    )
    (comp (ref "C699")
      (value "0201_470nF_6.3V_20%_X5R")
      (footprint "CAPC0603X33N")
      (fields (field (name "PART NUMBER") "Ceramic_0201"))
      (libsource (lib "Capacitors") (part "Capacitor"))
    )
    (comp (ref "C700")
      (value "0201_470nF_6.3V_20%_X5R")
      (footprint "CAPC0603X33N")
      (fields (field (name "PART NUMBER") "Ceramic_0201"))
      (libsource (lib "Capacitors") (part "Capacitor"))
    )
    (comp (ref "C701")
      (value "0201_470nF_6.3V_20%_X5R")
      (footprint "CAPC0603X33N")
      (fields (field (name "PART NUMBER") "Ceramic_0201"))
      (libsource (lib "Capacitors") (part "Capacitor"))
    )
    (comp (ref "C702")
      (value "0201_470nF_6.3V_20%_X5R")
      (footprint "CAPC0603X33N")
      (fields (field (name "PART NUMBER") "Ceramic_0201"))
      (libsource (lib "Capacitors") (part "Capacitor"))
    )
    (comp (ref "C703")
      (value "0201_470nF_6.3V_20%_X5R")
      (footprint "CAPC0603X33N")
      (fields (field (name "PART NUMBER") "Ceramic_0201"))
      (libsource (lib "Capacitors") (part "Capacitor"))
    )
    (comp (ref "C704")
      (value "4.7uF_6.3V_10%_X5R")
      (footprint "CAPC1608X87N")
      (description "Non-polarised capacitor")
      (fields
        (field (name "PART NUMBER") "CC0603_4.7UF_6.3V_10%_X5R")
        (field (name "VOLTAGE") "6.3V")
        (field (name "AUTHOR") "CERN DEM JLC")
      )
      (libsource (lib "Capacitors") (part "Capacitor - non polarized"))
    )
    (comp (ref "C705")
      (value "4.7uF_6.3V_10%_X5R")
      (footprint "CAPC1608X87N")
      (description "Non-polarised capacitor")
      (fields
        (field (name "PART NUMBER") "CC0603_4.7UF_6.3V_10%_X5R")
        (field (name "VOLTAGE") "6.3V")
        (field (name "AUTHOR") "CERN DEM JLC")
      )
      (libsource (lib "Capacitors") (part "Capacitor - non polarized"))
    )
    (comp (ref "C706")
      (value "4.7uF_6.3V_10%_X5R")
      (footprint "CAPC1608X87N")
      (description "Non-polarised capacitor")
      (fields
        (field (name "PART NUMBER") "CC0603_4.7UF_6.3V_10%_X5R")
        (field (name "VOLTAGE") "6.3V")
        (field (name "AUTHOR") "CERN DEM JLC")
      )
      (libsource (lib "Capacitors") (part "Capacitor - non polarized"))
    )
    (comp (ref "C707")
      (value "0201_470nF_6.3V_20%_X5R")
      (footprint "CAPC0603X33N")
      (fields (field (name "PART NUMBER") "Ceramic_0201"))
      (libsource (lib "Capacitors") (part "Capacitor"))
    )
    (comp (ref "C708")
      (value "0201_470nF_6.3V_20%_X5R")
      (footprint "CAPC0603X33N")
      (fields (field (name "PART NUMBER") "Ceramic_0201"))
      (libsource (lib "Capacitors") (part "Capacitor"))
    )
    (comp (ref "C709")
      (value "0201_470nF_6.3V_20%_X5R")
      (footprint "CAPC0603X33N")
      (fields (field (name "PART NUMBER") "Ceramic_0201"))
      (libsource (lib "Capacitors") (part "Capacitor"))
    )
    (comp (ref "C710")
      (value "0201_470nF_6.3V_20%_X5R")
      (footprint "CAPC0603X33N")
      (fields (field (name "PART NUMBER") "Ceramic_0201"))
      (libsource (lib "Capacitors") (part "Capacitor"))
    )
    (comp (ref "C711")
      (value "0201_470nF_6.3V_20%_X5R")
      (footprint "CAPC0603X33N")
      (fields (field (name "PART NUMBER") "Ceramic_0201"))
      (libsource (lib "Capacitors") (part "Capacitor"))
    )
    (comp (ref "C712")
      (value "100uF_6.3V_10%_X5R")
      (footprint "CAPC3225X270N")
      (description "Non-polarised capacitor")
      (fields
        (field (name "PART NUMBER") "CC1210_100UF_6.3V_20%_X5R")
        (field (name "VOLTAGE") "6.3V")
        (field (name "AUTHOR") "CERN DEM JLC")
      )
      (libsource (lib "Capacitors") (part "Capacitor - non polarized"))
    )
    (comp (ref "C713")
      (value "100uF_6.3V_10%_X5R")
      (footprint "CAPC3225X270N")
      (description "Non-polarised capacitor")
      (fields
        (field (name "PART NUMBER") "CC1210_100UF_6.3V_20%_X5R")
        (field (name "VOLTAGE") "6.3V")
        (field (name "AUTHOR") "CERN DEM JLC")
      )
      (libsource (lib "Capacitors") (part "Capacitor - non polarized"))
    )
    (comp (ref "C714")
      (value "100uF_6.3V_10%_X5R")
      (footprint "CAPC3225X270N")
      (description "Non-polarised capacitor")
      (fields
        (field (name "PART NUMBER") "CC1210_100UF_6.3V_20%_X5R")
        (field (name "VOLTAGE") "6.3V")
        (field (name "AUTHOR") "CERN DEM JLC")
      )
      (libsource (lib "Capacitors") (part "Capacitor - non polarized"))
    )
    (comp (ref "C715")
      (value "100uF_6.3V_10%_X5R")
      (footprint "CAPC3225X270N")
      (description "Non-polarised capacitor")
      (fields
        (field (name "PART NUMBER") "CC1210_100UF_6.3V_20%_X5R")
        (field (name "VOLTAGE") "6.3V")
        (field (name "AUTHOR") "CERN DEM JLC")
      )
      (libsource (lib "Capacitors") (part "Capacitor - non polarized"))
    )
    (comp (ref "C716")
      (value "0201_470nF_6.3V_20%_X5R")
      (footprint "CAPC0603X33N")
      (fields (field (name "PART NUMBER") "Ceramic_0201"))
      (libsource (lib "Capacitors") (part "Capacitor"))
    )
    (comp (ref "C717")
      (value "0201_470nF_6.3V_20%_X5R")
      (footprint "CAPC0603X33N")
      (fields (field (name "PART NUMBER") "Ceramic_0201"))
      (libsource (lib "Capacitors") (part "Capacitor"))
    )
    (comp (ref "C718")
      (value "0201_470nF_6.3V_20%_X5R")
      (footprint "CAPC0603X33N")
      (fields (field (name "PART NUMBER") "Ceramic_0201"))
      (libsource (lib "Capacitors") (part "Capacitor"))
    )
    (comp (ref "C719")
      (value "0201_470nF_6.3V_20%_X5R")
      (footprint "CAPC0603X33N")
      (fields (field (name "PART NUMBER") "Ceramic_0201"))
      (libsource (lib "Capacitors") (part "Capacitor"))
    )
    (comp (ref "C720")
      (value "0201_470nF_6.3V_20%_X5R")
      (footprint "CAPC0603X33N")
      (fields (field (name "PART NUMBER") "Ceramic_0201"))
      (libsource (lib "Capacitors") (part "Capacitor"))
    )
    (comp (ref "C721")
      (value "0201_470nF_6.3V_20%_X5R")
      (footprint "CAPC0603X33N")
      (fields (field (name "PART NUMBER") "Ceramic_0201"))
      (libsource (lib "Capacitors") (part "Capacitor"))
    )
    (comp (ref "C722")
      (value "0201_22nF_6.3V_20%_X5R")
      (footprint "CAPC0603X33N")
      (fields (field (name "PART NUMBER") "Ceramic_0201"))
      (libsource (lib "Capacitors") (part "Capacitor"))
    )
    (comp (ref "C723")
      (value "0201_22nF_6.3V_20%_X5R")
      (footprint "CAPC0603X33N")
      (fields (field (name "PART NUMBER") "Ceramic_0201"))
      (libsource (lib "Capacitors") (part "Capacitor"))
    )
    (comp (ref "C724")
      (value "0201_22nF_6.3V_20%_X5R")
      (footprint "CAPC0603X33N")
      (fields (field (name "PART NUMBER") "Ceramic_0201"))
      (libsource (lib "Capacitors") (part "Capacitor"))
    )
    (comp (ref "C725")
      (value "0201_22nF_6.3V_20%_X5R")
      (footprint "CAPC0603X33N")
      (fields (field (name "PART NUMBER") "Ceramic_0201"))
      (libsource (lib "Capacitors") (part "Capacitor"))
    )
    (comp (ref "C726")
      (value "0201_100nF_6.3V_20%_X5R")
      (footprint "CAPC0603X33N")
      (fields (field (name "PART NUMBER") "Ceramic_0201"))
      (libsource (lib "Capacitors") (part "Capacitor"))
    )
    (comp (ref "C727")
      (value "0201_100nF_6.3V_20%_X5R")
      (footprint "CAPC0603X33N")
      (fields (field (name "PART NUMBER") "Ceramic_0201"))
      (libsource (lib "Capacitors") (part "Capacitor"))
    )
    (comp (ref "C728")
      (value "0201_100nF_6.3V_20%_X5R")
      (footprint "CAPC0603X33N")
      (fields (field (name "PART NUMBER") "Ceramic_0201"))
      (libsource (lib "Capacitors") (part "Capacitor"))
    )
    (comp (ref "C729")
      (value "0201_100nF_6.3V_20%_X5R")
      (footprint "CAPC0603X33N")
      (fields (field (name "PART NUMBER") "Ceramic_0201"))
      (libsource (lib "Capacitors") (part "Capacitor"))
    )
    (comp (ref "C730")
      (value "0201_22nF_6.3V_20%_X5R")
      (footprint "CAPC0603X33N")
      (fields (field (name "PART NUMBER") "Ceramic_0201"))
      (libsource (lib "Capacitors") (part "Capacitor"))
    )
    (comp (ref "C731")
      (value "0201_22nF_6.3V_20%_X5R")
      (footprint "CAPC0603X33N")
      (fields (field (name "PART NUMBER") "Ceramic_0201"))
      (libsource (lib "Capacitors") (part "Capacitor"))
    )
    (comp (ref "C732")
      (value "0201_22nF_6.3V_20%_X5R")
      (footprint "CAPC0603X33N")
      (fields (field (name "PART NUMBER") "Ceramic_0201"))
      (libsource (lib "Capacitors") (part "Capacitor"))
    )
    (comp (ref "C733")
      (value "0201_22nF_6.3V_20%_X5R")
      (footprint "CAPC0603X33N")
      (fields (field (name "PART NUMBER") "Ceramic_0201"))
      (libsource (lib "Capacitors") (part "Capacitor"))
    )
    (comp (ref "C734")
      (value "0201_100nF_6.3V_20%_X5R")
      (footprint "CAPC0603X33N")
      (fields (field (name "PART NUMBER") "Ceramic_0201"))
      (libsource (lib "Capacitors") (part "Capacitor"))
    )
    (comp (ref "C735")
      (value "0201_100nF_6.3V_20%_X5R")
      (footprint "CAPC0603X33N")
      (fields (field (name "PART NUMBER") "Ceramic_0201"))
      (libsource (lib "Capacitors") (part "Capacitor"))
    )
    (comp (ref "C736")
      (value "0201_100nF_6.3V_20%_X5R")
      (footprint "CAPC0603X33N")
      (fields (field (name "PART NUMBER") "Ceramic_0201"))
      (libsource (lib "Capacitors") (part "Capacitor"))
    )
    (comp (ref "C737")
      (value "0201_100nF_6.3V_20%_X5R")
      (footprint "CAPC0603X33N")
      (fields (field (name "PART NUMBER") "Ceramic_0201"))
      (libsource (lib "Capacitors") (part "Capacitor"))
    )
    (comp (ref "C738")
      (value "220nF_6.3V_10%_X5R")
      (footprint "CAPC0603X33N")
      (description "Non-polarised capacitor")
      (fields
        (field (name "PART NUMBER") "CC0201_220NF_6.3V_20%_X5R")
        (field (name "VOLTAGE") "6.3V")
        (field (name "AUTHOR") "CERN DEM JLC")
      )
      (libsource (lib "Capacitors") (part "Capacitor - non polarized"))
    )
    (comp (ref "C739")
      (value "220nF_6.3V_10%_X5R")
      (footprint "CAPC0603X33N")
      (description "Non-polarised capacitor")
      (fields
        (field (name "PART NUMBER") "CC0201_220NF_6.3V_20%_X5R")
        (field (name "VOLTAGE") "6.3V")
        (field (name "AUTHOR") "CERN DEM JLC")
      )
      (libsource (lib "Capacitors") (part "Capacitor - non polarized"))
    )
    (comp (ref "C740")
      (value "220nF_6.3V_10%_X5R")
      (footprint "CAPC0603X33N")
      (description "Non-polarised capacitor")
      (fields
        (field (name "PART NUMBER") "CC0201_220NF_6.3V_20%_X5R")
        (field (name "VOLTAGE") "6.3V")
        (field (name "AUTHOR") "CERN DEM JLC")
      )
      (libsource (lib "Capacitors") (part "Capacitor - non polarized"))
    )
    (comp (ref "C741")
      (value "220nF_6.3V_10%_X5R")
      (footprint "CAPC0603X33N")
      (description "Non-polarised capacitor")
      (fields
        (field (name "PART NUMBER") "CC0201_220NF_6.3V_20%_X5R")
        (field (name "VOLTAGE") "6.3V")
        (field (name "AUTHOR") "CERN DEM JLC")
      )
      (libsource (lib "Capacitors") (part "Capacitor - non polarized"))
    )
    (comp (ref "C742")
      (value "220nF_6.3V_10%_X5R")
      (footprint "CAPC0603X33N")
      (description "Non-polarised capacitor")
      (fields
        (field (name "PART NUMBER") "CC0201_220NF_6.3V_20%_X5R")
        (field (name "VOLTAGE") "6.3V")
        (field (name "AUTHOR") "CERN DEM JLC")
      )
      (libsource (lib "Capacitors") (part "Capacitor - non polarized"))
    )
    (comp (ref "C743")
      (value "220nF_6.3V_10%_X5R")
      (footprint "CAPC0603X33N")
      (description "Non-polarised capacitor")
      (fields
        (field (name "PART NUMBER") "CC0201_220NF_6.3V_20%_X5R")
        (field (name "VOLTAGE") "6.3V")
        (field (name "AUTHOR") "CERN DEM JLC")
      )
      (libsource (lib "Capacitors") (part "Capacitor - non polarized"))
    )
    (comp (ref "C744")
      (value "220nF_6.3V_10%_X5R")
      (footprint "CAPC0603X33N")
      (description "Non-polarised capacitor")
      (fields
        (field (name "PART NUMBER") "CC0201_220NF_6.3V_20%_X5R")
        (field (name "VOLTAGE") "6.3V")
        (field (name "AUTHOR") "CERN DEM JLC")
      )
      (libsource (lib "Capacitors") (part "Capacitor - non polarized"))
    )
    (comp (ref "C745")
      (value "220nF_6.3V_10%_X5R")
      (footprint "CAPC0603X33N")
      (description "Non-polarised capacitor")
      (fields
        (field (name "PART NUMBER") "CC0201_220NF_6.3V_20%_X5R")
        (field (name "VOLTAGE") "6.3V")
        (field (name "AUTHOR") "CERN DEM JLC")
      )
      (libsource (lib "Capacitors") (part "Capacitor - non polarized"))
    )
    (comp (ref "C746")
      (value "220nF_6.3V_10%_X5R")
      (footprint "CAPC0603X33N")
      (description "Non-polarised capacitor")
      (fields
        (field (name "PART NUMBER") "CC0201_220NF_6.3V_20%_X5R")
        (field (name "VOLTAGE") "6.3V")
        (field (name "AUTHOR") "CERN DEM JLC")
      )
      (libsource (lib "Capacitors") (part "Capacitor - non polarized"))
    )
    (comp (ref "C747")
      (value "220nF_6.3V_10%_X5R")
      (footprint "CAPC0603X33N")
      (description "Non-polarised capacitor")
      (fields
        (field (name "PART NUMBER") "CC0201_220NF_6.3V_20%_X5R")
        (field (name "VOLTAGE") "6.3V")
        (field (name "AUTHOR") "CERN DEM JLC")
      )
      (libsource (lib "Capacitors") (part "Capacitor - non polarized"))
    )
    (comp (ref "C748")
      (value "220nF_6.3V_10%_X5R")
      (footprint "CAPC0603X33N")
      (description "Non-polarised capacitor")
      (fields
        (field (name "PART NUMBER") "CC0201_220NF_6.3V_20%_X5R")
        (field (name "VOLTAGE") "6.3V")
        (field (name "AUTHOR") "CERN DEM JLC")
      )
      (libsource (lib "Capacitors") (part "Capacitor - non polarized"))
    )
    (comp (ref "FB5")
      (value "1812_100Z_8A_6mDCR")
      (footprint "INDC4532X340N")
      (description "FERRITE BEAD 100 OHM 8A SMD 1812")
      (fields
        (field (name "PART NUMBER") "74279226101")
        (field (name "MANUFACTURER") "Wurth Electronics Inc")
      )
      (libsource (lib "Filters") (part "Ferrite Bead 2-pin"))
    )
    (comp (ref "FB6")
      (value "1812_100Z_8A_6mDCR")
      (footprint "INDC4532X340N")
      (description "FERRITE BEAD 100 OHM 8A SMD 1812")
      (fields
        (field (name "PART NUMBER") "74279226101")
        (field (name "MANUFACTURER") "Wurth Electronics Inc")
      )
      (libsource (lib "Filters") (part "Ferrite Bead 2-pin"))
    )
    (comp (ref "FB7")
      (value "1812_100Z_8A_6mDCR")
      (footprint "INDC4532X340N")
      (description "FERRITE BEAD 100 OHM 8A SMD 1812")
      (fields
        (field (name "PART NUMBER") "74279226101")
        (field (name "MANUFACTURER") "Wurth Electronics Inc")
      )
      (libsource (lib "Filters") (part "Ferrite Bead 2-pin"))
    )
    (comp (ref "FB8")
      (value "1812_100Z_8A_6mDCR")
      (footprint "INDC4532X340N")
      (description "FERRITE BEAD 100 OHM 8A SMD 1812")
      (fields
        (field (name "PART NUMBER") "74279226101")
        (field (name "MANUFACTURER") "Wurth Electronics Inc")
      )
      (libsource (lib "Filters") (part "Ferrite Bead 2-pin"))
    )
    (comp (ref "IC2")
      (value "XC7A350T-2FFG1156C")
      (footprint "BGA1156C100P34X34_3500X3500X335")
      (description "Artix-6 FPGA, 16 GTPs, 600 User I/Os, 1156-Pin BGA, Speed Grade 2, Commercial Grade, Pb-Free")
      (fields (field (name "MANUFACTURER") "XILINX") (field (name "AUTHOR") "CERN DEM JLC"))
      (libsource (lib "AMC_FMC_Carrier") (part "XC7A350T-2FFG1156C"))
    )
    (comp (ref "IC45")
      (value "TS3431")
      (footprint "SOT-23")
      (description "2.5V ADJ Voltage reference")
      (libsource (lib "LIBRARY_SCH") (part "REF_TL431_SOT23"))
    )
    (comp (ref "L10")
      (value "ELLVGG1R0N")
      (footprint "L_ELLVGG2R2N")
      (description "2.2uH, 1.4A, 92mR Panasonic")
      (fields (field (name "ALTIUM_UNNAMED_1") "1uH, 2.2A, 52mR Panasonic"))
      (libsource (lib "LIBRARY_SCH") (part "L_CHOKE_ELLVGG"))
    )
    (comp (ref "L12")
      (value "ELLVGG1R0N")
      (footprint "L_ELLVGG2R2N")
      (description "2.2uH, 1.4A, 92mR Panasonic")
      (fields (field (name "ALTIUM_UNNAMED_1") "1uH, 2.2A, 52mR Panasonic"))
      (libsource (lib "LIBRARY_SCH") (part "L_CHOKE_ELLVGG"))
    )
    (comp (ref "R213")
      (value "220R")
      (footprint "0402R")
      (description "SMD Resistor")
      (libsource (lib "LIBRARY_SCH") (part "RES_0402"))
    )
  )
  (nets
    (net (code "1") (name "/VREF_XDAC") (class "Default")
      (node (ref "C613") (pin "2") (pinfunction "2_2") (pintype "passive"))
      (node (ref "IC2") (pin "V18") (pinfunction "VREFP_0_V18") (pintype "input"))
      (node (ref "IC45") (pin "1") (pinfunction "REF_1") (pintype "passive"))
      (node (ref "IC45") (pin "2") (pinfunction "C_2") (pintype "passive"))
      (node (ref "R213") (pin "1") (pinfunction "1_1") (pintype "passive"))
    )
    (net (code "2") (name "GND") (class "Default")
      (node (ref "BH1") (pin "neg") (pinfunction "+_neg") (pintype "power_in"))
      (node (ref "C106") (pin "1") (pinfunction "1_1") (pintype "passive"))
      (node (ref "C107") (pin "1") (pinfunction "1_1") (pintype "passive"))
      (node (ref "C226") (pin "2") (pinfunction "2_2") (pintype "passive"))
      (node (ref "C229") (pin "1") (pinfunction "1_1") (pintype "passive"))
      (node (ref "C230") (pin "2") (pinfunction "2_2") (pintype "passive"))
      (node (ref "C231") (pin "2") (pinfunction "2_2") (pintype "passive"))
      (node (ref "C232") (pin "1") (pinfunction "1_1") (pintype "passive"))
      (node (ref "C233") (pin "1") (pinfunction "1_1") (pintype "passive"))
      (node (ref "C234") (pin "1") (pinfunction "1_1") (pintype "passive"))
      (node (ref "C235") (pin "1") (pinfunction "1_1") (pintype "passive"))
      (node (ref "C236") (pin "1") (pinfunction "1_1") (pintype "passive"))
      (node (ref "C237") (pin "1") (pinfunction "1_1") (pintype "passive"))
      (node (ref "C238") (pin "1") (pinfunction "1_1") (pintype "passive"))
      (node (ref "C239") (pin "1") (pinfunction "1_1") (pintype "passive"))
      (node (ref "C240") (pin "1") (pinfunction "1_1") (pintype "passive"))
      (node (ref "C241") (pin "1") (pinfunction "1_1") (pintype "passive"))
      (node (ref "C242") (pin "1") (pinfunction "1_1") (pintype "passive"))
      (node (ref "C243") (pin "1") (pinfunction "1_1") (pintype "passive"))
      (node (ref "C244") (pin "1") (pinfunction "1_1") (pintype "passive"))
      (node (ref "C245") (pin "1") (pinfunction "1_1") (pintype "passive"))
      (node (ref "C246") (pin "1") (pinfunction "1_1") (pintype "passive"))
      (node (ref "C247") (pin "1") (pinfunction "1_1") (pintype "passive"))
      (node (ref "C248") (pin "1") (pinfunction "1_1") (pintype "passive"))
      (node (ref "C249") (pin "1") (pinfunction "1_1") (pintype "passive"))
      (node (ref "C250") (pin "1") (pinfunction "1_1") (pintype "passive"))
      (node (ref "C251") (pin "1") (pinfunction "1_1") (pintype "passive"))
      (node (ref "C252") (pin "1") (pinfunction "1_1") (pintype "passive"))
      (node (ref "C253") (pin "1") (pinfunction "1_1") (pintype "passive"))
      (node (ref "C254") (pin "1") (pinfunction "1_1") (pintype "passive"))
      (node (ref "C255") (pin "1") (pinfunction "1_1") (pintype "passive"))
      (node (ref "C256") (pin "1") (pinfunction "1_1") (pintype "passive"))
      (node (ref "C257") (pin "1") (pinfunction "1_1") (pintype "passive"))
      (node (ref "C258") (pin "1") (pinfunction "1_1") (pintype "passive"))
      (node (ref "C259") (pin "1") (pinfunction "1_1") (pintype "passive"))
      (node (ref "C260") (pin "1") (pinfunction "1_1") (pintype "passive"))
      (node (ref "C261") (pin "1") (pinfunction "1_1") (pintype "passive"))
      (node (ref "C262") (pin "1") (pinfunction "1_1") (pintype "passive"))
      (node (ref "C263") (pin "1") (pinfunction "1_1") (pintype "passive"))
      (node (ref "C264") (pin "1") (pinfunction "1_1") (pintype "passive"))
      (node (ref "C265") (pin "1") (pinfunction "1_1") (pintype "passive"))
      (node (ref "C266") (pin "1") (pinfunction "1_1") (pintype "passive"))
      (node (ref "C267") (pin "1") (pinfunction "1_1") (pintype "passive"))
      (node (ref "C268") (pin "1") (pinfunction "1_1") (pintype "passive"))
      (node (ref "C269") (pin "1") (pinfunction "1_1") (pintype "passive"))
      (node (ref "C270") (pin "1") (pinfunction "1_1") (pintype "passive"))
      (node (ref "C271") (pin "1") (pinfunction "1_1") (pintype "passive"))
      (node (ref "C272") (pin "1") (pinfunction "1_1") (pintype "passive"))
      (node (ref "C275") (pin "1") (pinfunction "1_1") (pintype "passive"))
      (node (ref "C276") (pin "1") (pinfunction "1_1") (pintype "passive"))
      (node (ref "C277") (pin "1") (pinfunction "1_1") (pintype "passive"))
      (node (ref "C278") (pin "1") (pinfunction "1_1") (pintype "passive"))
      (node (ref "C279") (pin "1") (pinfunction "1_1") (pintype "passive"))
      (node (ref "C280") (pin "1") (pinfunction "1_1") (pintype "passive"))
      (node (ref "C283") (pin "1") (pinfunction "1_1") (pintype "passive"))
      (node (ref "C284") (pin "1") (pinfunction "1_1") (pintype "passive"))
      (node (ref "C285") (pin "1") (pinfunction "1_1") (pintype "passive"))
      (node (ref "C286") (pin "1") (pinfunction "1_1") (pintype "passive"))
      (node (ref "C287") (pin "1") (pinfunction "1_1") (pintype "passive"))
      (node (ref "C288") (pin "1") (pinfunction "1_1") (pintype "passive"))
      (node (ref "C291") (pin "1") (pinfunction "1_1") (pintype "passive"))
      (node (ref "C292") (pin "1") (pinfunction "1_1") (pintype "passive"))
      (node (ref "C293") (pin "1") (pinfunction "1_1") (pintype "passive"))
      (node (ref "C294") (pin "1") (pinfunction "1_1") (pintype "passive"))
      (node (ref "C295") (pin "1") (pinfunction "1_1") (pintype "passive"))
      (node (ref "C296") (pin "1") (pinfunction "1_1") (pintype "passive"))
      (node (ref "C446") (pin "1") (pinfunction "1_1") (pintype "passive"))
      (node (ref "C447") (pin "2") (pinfunction "2_2") (pintype "passive"))
      (node (ref "C448") (pin "1") (pinfunction "1_1") (pintype "passive"))
      (node (ref "C449") (pin "1") (pinfunction "1_1") (pintype "passive"))
      (node (ref "C450") (pin "1") (pinfunction "1_1") (pintype "passive"))
      (node (ref "C451") (pin "1") (pinfunction "1_1") (pintype "passive"))
      (node (ref "C465") (pin "1") (pinfunction "1_1") (pintype "passive"))
      (node (ref "C478") (pin "1") (pinfunction "1_1") (pintype "passive"))
      (node (ref "C549") (pin "1") (pinfunction "1_1") (pintype "passive"))
      (node (ref "C550") (pin "1") (pinfunction "1_1") (pintype "passive"))
      (node (ref "C551") (pin "1") (pinfunction "1_1") (pintype "passive"))
      (node (ref "C552") (pin "1") (pinfunction "1_1") (pintype "passive"))
      (node (ref "C553") (pin "1") (pinfunction "1_1") (pintype "passive"))
      (node (ref "C554") (pin "1") (pinfunction "1_1") (pintype "passive"))
      (node (ref "C555") (pin "1") (pinfunction "1_1") (pintype "passive"))
      (node (ref "C556") (pin "1") (pinfunction "1_1") (pintype "passive"))
      (node (ref "C557") (pin "1") (pinfunction "1_1") (pintype "passive"))
      (node (ref "C558") (pin "1") (pinfunction "1_1") (pintype "passive"))
      (node (ref "C559") (pin "1") (pinfunction "1_1") (pintype "passive"))
      (node (ref "C560") (pin "1") (pinfunction "1_1") (pintype "passive"))
      (node (ref "C561") (pin "1") (pinfunction "1_1") (pintype "passive"))
      (node (ref "C562") (pin "1") (pinfunction "1_1") (pintype "passive"))
      (node (ref "C563") (pin "1") (pinfunction "1_1") (pintype "passive"))
      (node (ref "C564") (pin "1") (pinfunction "1_1") (pintype "passive"))
      (node (ref "C565") (pin "1") (pinfunction "1_1") (pintype "passive"))
      (node (ref "C566") (pin "1") (pinfunction "1_1") (pintype "passive"))
      (node (ref "C576") (pin "1") (pinfunction "1_1") (pintype "passive"))
      (node (ref "C577") (pin "1") (pinfunction "1_1") (pintype "passive"))
      (node (ref "C578") (pin "1") (pinfunction "1_1") (pintype "passive"))
      (node (ref "C579") (pin "1") (pinfunction "1_1") (pintype "passive"))
      (node (ref "C580") (pin "1") (pinfunction "1_1") (pintype "passive"))
      (node (ref "C581") (pin "1") (pinfunction "1_1") (pintype "passive"))
      (node (ref "C582") (pin "1") (pinfunction "1_1") (pintype "passive"))
      (node (ref "C583") (pin "1") (pinfunction "1_1") (pintype "passive"))
      (node (ref "C585") (pin "1") (pinfunction "1_1") (pintype "passive"))
      (node (ref "C586") (pin "1") (pinfunction "1_1") (pintype "passive"))
      (node (ref "C587") (pin "2") (pinfunction "2_2") (pintype "passive"))
      (node (ref "C588") (pin "1") (pinfunction "1_1") (pintype "passive"))
      (node (ref "C589") (pin "1") (pinfunction "1_1") (pintype "passive"))
      (node (ref "C591") (pin "1") (pinfunction "1_1") (pintype "passive"))
      (node (ref "C592") (pin "2") (pinfunction "2_2") (pintype "passive"))
      (node (ref "C593") (pin "2") (pinfunction "2_2") (pintype "passive"))
      (node (ref "C594") (pin "1") (pinfunction "1_1") (pintype "passive"))
      (node (ref "C596") (pin "1") (pinfunction "1_1") (pintype "passive"))
      (node (ref "C597") (pin "1") (pinfunction "1_1") (pintype "passive"))
      (node (ref "C598") (pin "1") (pinfunction "1_1") (pintype "passive"))
      (node (ref "C599") (pin "1") (pinfunction "1_1") (pintype "passive"))
      (node (ref "C600") (pin "1") (pinfunction "1_1") (pintype "passive"))
      (node (ref "C601") (pin "1") (pinfunction "1_1") (pintype "passive"))
      (node (ref "C602") (pin "2") (pinfunction "2_2") (pintype "passive"))
      (node (ref "C603") (pin "1") (pinfunction "1_1") (pintype "passive"))
      (node (ref "C604") (pin "1") (pinfunction "1_1") (pintype "passive"))
      (node (ref "C605") (pin "1") (pinfunction "1_1") (pintype "passive"))
      (node (ref "C606") (pin "1") (pinfunction "1_1") (pintype "passive"))
      (node (ref "C607") (pin "1") (pinfunction "1_1") (pintype "passive"))
      (node (ref "C608") (pin "1") (pinfunction "1_1") (pintype "passive"))
      (node (ref "C609") (pin "1") (pinfunction "1_1") (pintype "passive"))
      (node (ref "C610") (pin "1") (pinfunction "1_1") (pintype "passive"))
      (node (ref "C611") (pin "1") (pinfunction "1_1") (pintype "passive"))
      (node (ref "C612") (pin "2") (pinfunction "2_2") (pintype "passive"))
      (node (ref "C613") (pin "1") (pinfunction "1_1") (pintype "passive"))
      (node (ref "C614") (pin "1") (pinfunction "1_1") (pintype "passive"))
      (node (ref "C615") (pin "1") (pinfunction "1_1") (pintype "passive"))
      (node (ref "C636") (pin "1") (pinfunction "1_1") (pintype "passive"))
      (node (ref "C637") (pin "1") (pinfunction "1_1") (pintype "passive"))
      (node (ref "C638") (pin "2") (pinfunction "2_2") (pintype "passive"))
      (node (ref "C639") (pin "1") (pinfunction "1_1") (pintype "passive"))
      (node (ref "C640") (pin "1") (pinfunction "1_1") (pintype "passive"))
      (node (ref "C641") (pin "1") (pinfunction "1_1") (pintype "passive"))
      (node (ref "C642") (pin "1") (pinfunction "1_1") (pintype "passive"))
      (node (ref "C643") (pin "1") (pinfunction "1_1") (pintype "passive"))
      (node (ref "C644") (pin "1") (pinfunction "1_1") (pintype "passive"))
      (node (ref "C645") (pin "1") (pinfunction "1_1") (pintype "passive"))
      (node (ref "C646") (pin "1") (pinfunction "1_1") (pintype "passive"))
      (node (ref "C647") (pin "1") (pinfunction "1_1") (pintype "passive"))
      (node (ref "C648") (pin "1") (pinfunction "1_1") (pintype "passive"))
      (node (ref "C649") (pin "1") (pinfunction "1_1") (pintype "passive"))
      (node (ref "C650") (pin "1") (pinfunction "1_1") (pintype "passive"))
      (node (ref "C651") (pin "1") (pinfunction "1_1") (pintype "passive"))
      (node (ref "C652") (pin "1") (pinfunction "1_1") (pintype "passive"))
      (node (ref "C653") (pin "1") (pinfunction "1_1") (pintype "passive"))
      (node (ref "C654") (pin "1") (pinfunction "1_1") (pintype "passive"))
      (node (ref "C655") (pin "1") (pinfunction "1_1") (pintype "passive"))
      (node (ref "C656") (pin "1") (pinfunction "1_1") (pintype "passive"))
      (node (ref "C657") (pin "1") (pinfunction "1_1") (pintype "passive"))
      (node (ref "C658") (pin "1") (pinfunction "1_1") (pintype "passive"))
      (node (ref "C659") (pin "1") (pinfunction "1_1") (pintype "passive"))
      (node (ref "C660") (pin "1") (pinfunction "1_1") (pintype "passive"))
      (node (ref "C661") (pin "1") (pinfunction "1_1") (pintype "passive"))
      (node (ref "C662") (pin "1") (pinfunction "1_1") (pintype "passive"))
      (node (ref "C663") (pin "1") (pinfunction "1_1") (pintype "passive"))
      (node (ref "C664") (pin "1") (pinfunction "1_1") (pintype "passive"))
      (node (ref "C665") (pin "1") (pinfunction "1_1") (pintype "passive"))
      (node (ref "C666") (pin "1") (pinfunction "1_1") (pintype "passive"))
      (node (ref "C667") (pin "1") (pinfunction "1_1") (pintype "passive"))
      (node (ref "C668") (pin "1") (pinfunction "1_1") (pintype "passive"))
      (node (ref "C669") (pin "1") (pinfunction "1_1") (pintype "passive"))
      (node (ref "C670") (pin "1") (pinfunction "1_1") (pintype "passive"))
      (node (ref "C671") (pin "1") (pinfunction "1_1") (pintype "passive"))
      (node (ref "C672") (pin "1") (pinfunction "1_1") (pintype "passive"))
      (node (ref "C673") (pin "1") (pinfunction "1_1") (pintype "passive"))
      (node (ref "C674") (pin "1") (pinfunction "1_1") (pintype "passive"))
      (node (ref "C675") (pin "1") (pinfunction "1_1") (pintype "passive"))
      (node (ref "C676") (pin "2") (pinfunction "2_2") (pintype "passive"))
      (node (ref "C677") (pin "2") (pinfunction "2_2") (pintype "passive"))
      (node (ref "C678") (pin "2") (pinfunction "2_2") (pintype "passive"))
      (node (ref "C679") (pin "2") (pinfunction "2_2") (pintype "passive"))
      (node (ref "C680") (pin "1") (pinfunction "1_1") (pintype "passive"))
      (node (ref "C681") (pin "1") (pinfunction "1_1") (pintype "passive"))
      (node (ref "C682") (pin "1") (pinfunction "1_1") (pintype "passive"))
      (node (ref "C683") (pin "1") (pinfunction "1_1") (pintype "passive"))
      (node (ref "C684") (pin "1") (pinfunction "1_1") (pintype "passive"))
      (node (ref "C685") (pin "1") (pinfunction "1_1") (pintype "passive"))
      (node (ref "C686") (pin "1") (pinfunction "1_1") (pintype "passive"))
      (node (ref "C687") (pin "1") (pinfunction "1_1") (pintype "passive"))
      (node (ref "C688") (pin "1") (pinfunction "1_1") (pintype "passive"))
      (node (ref "C689") (pin "1") (pinfunction "1_1") (pintype "passive"))
      (node (ref "C690") (pin "1") (pinfunction "1_1") (pintype "passive"))
      (node (ref "C691") (pin "1") (pinfunction "1_1") (pintype "passive"))
      (node (ref "C692") (pin "1") (pinfunction "1_1") (pintype "passive"))
      (node (ref "C693") (pin "1") (pinfunction "1_1") (pintype "passive"))
      (node (ref "C694") (pin "1") (pinfunction "1_1") (pintype "passive"))
      (node (ref "C695") (pin "1") (pinfunction "1_1") (pintype "passive"))
      (node (ref "C696") (pin "1") (pinfunction "1_1") (pintype "passive"))
      (node (ref "C697") (pin "1") (pinfunction "1_1") (pintype "passive"))
      (node (ref "C698") (pin "1") (pinfunction "1_1") (pintype "passive"))
      (node (ref "C699") (pin "1") (pinfunction "1_1") (pintype "passive"))
      (node (ref "C700") (pin "1") (pinfunction "1_1") (pintype "passive"))
      (node (ref "C701") (pin "1") (pinfunction "1_1") (pintype "passive"))
      (node (ref "C702") (pin "1") (pinfunction "1_1") (pintype "passive"))
      (node (ref "C703") (pin "1") (pinfunction "1_1") (pintype "passive"))
      (node (ref "C704") (pin "1") (pinfunction "1_1") (pintype "passive"))
      (node (ref "C705") (pin "1") (pinfunction "1_1") (pintype "passive"))
      (node (ref "C706") (pin "1") (pinfunction "1_1") (pintype "passive"))
      (node (ref "C707") (pin "1") (pinfunction "1_1") (pintype "passive"))
      (node (ref "C708") (pin "1") (pinfunction "1_1") (pintype "passive"))
      (node (ref "C709") (pin "1") (pinfunction "1_1") (pintype "passive"))
      (node (ref "C710") (pin "1") (pinfunction "1_1") (pintype "passive"))
      (node (ref "C711") (pin "1") (pinfunction "1_1") (pintype "passive"))
      (node (ref "C712") (pin "2") (pinfunction "2_2") (pintype "passive"))
      (node (ref "C713") (pin "2") (pinfunction "2_2") (pintype "passive"))
      (node (ref "C714") (pin "2") (pinfunction "2_2") (pintype "passive"))
      (node (ref "C715") (pin "2") (pinfunction "2_2") (pintype "passive"))
      (node (ref "C716") (pin "1") (pinfunction "1_1") (pintype "passive"))
      (node (ref "C717") (pin "1") (pinfunction "1_1") (pintype "passive"))
      (node (ref "C718") (pin "1") (pinfunction "1_1") (pintype "passive"))
      (node (ref "C719") (pin "1") (pinfunction "1_1") (pintype "passive"))
      (node (ref "C720") (pin "1") (pinfunction "1_1") (pintype "passive"))
      (node (ref "C721") (pin "1") (pinfunction "1_1") (pintype "passive"))
      (node (ref "C722") (pin "1") (pinfunction "1_1") (pintype "passive"))
      (node (ref "C723") (pin "1") (pinfunction "1_1") (pintype "passive"))
      (node (ref "C724") (pin "1") (pinfunction "1_1") (pintype "passive"))
      (node (ref "C725") (pin "1") (pinfunction "1_1") (pintype "passive"))
      (node (ref "C726") (pin "1") (pinfunction "1_1") (pintype "passive"))
      (node (ref "C727") (pin "1") (pinfunction "1_1") (pintype "passive"))
      (node (ref "C728") (pin "1") (pinfunction "1_1") (pintype "passive"))
      (node (ref "C729") (pin "1") (pinfunction "1_1") (pintype "passive"))
      (node (ref "C730") (pin "1") (pinfunction "1_1") (pintype "passive"))
      (node (ref "C731") (pin "1") (pinfunction "1_1") (pintype "passive"))
      (node (ref "C732") (pin "1") (pinfunction "1_1") (pintype "passive"))
      (node (ref "C733") (pin "1") (pinfunction "1_1") (pintype "passive"))
      (node (ref "C734") (pin "1") (pinfunction "1_1") (pintype "passive"))
      (node (ref "C735") (pin "1") (pinfunction "1_1") (pintype "passive"))
      (node (ref "C736") (pin "1") (pinfunction "1_1") (pintype "passive"))
      (node (ref "C737") (pin "1") (pinfunction "1_1") (pintype "passive"))
      (node (ref "C738") (pin "1") (pinfunction "1_1") (pintype "passive"))
      (node (ref "C739") (pin "1") (pinfunction "1_1") (pintype "passive"))
      (node (ref "C740") (pin "1") (pinfunction "1_1") (pintype "passive"))
      (node (ref "C741") (pin "1") (pinfunction "1_1") (pintype "passive"))
      (node (ref "C742") (pin "1") (pinfunction "1_1") (pintype "passive"))
      (node (ref "C743") (pin "1") (pinfunction "1_1") (pintype "passive"))
      (node (ref "C744") (pin "1") (pinfunction "1_1") (pintype "passive"))
      (node (ref "C745") (pin "1") (pinfunction "1_1") (pintype "passive"))
      (node (ref "C746") (pin "1") (pinfunction "1_1") (pintype "passive"))
      (node (ref "C747") (pin "1") (pinfunction "1_1") (pintype "passive"))
      (node (ref "C748") (pin "1") (pinfunction "1_1") (pintype "passive"))
      (node (ref "IC2") (pin "A1") (pinfunction "GND_A1") (pintype "power_in"))
      (node (ref "IC2") (pin "A11") (pinfunction "GND_A11") (pintype "power_in"))
      (node (ref "IC2") (pin "A12") (pinfunction "GND_A12") (pintype "power_in"))
      (node (ref "IC2") (pin "A14") (pinfunction "GND_A14") (pintype "power_in"))
      (node (ref "IC2") (pin "A16") (pinfunction "GND_A16") (pintype "power_in"))
      (node (ref "IC2") (pin "A18") (pinfunction "GND_A18") (pintype "power_in"))
      (node (ref "IC2") (pin "A20") (pinfunction "GND_A20") (pintype "power_in"))
      (node (ref "IC2") (pin "A22") (pinfunction "GND_A22") (pintype "power_in"))
      (node (ref "IC2") (pin "A24") (pinfunction "GND_A24") (pintype "power_in"))
      (node (ref "IC2") (pin "A26") (pinfunction "GND_A26") (pintype "power_in"))
      (node (ref "IC2") (pin "AA1") (pinfunction "GND_AA1") (pintype "power_in"))
      (node (ref "IC2") (pin "AA11") (pinfunction "GND_AA11") (pintype "power_in"))
      (node (ref "IC2") (pin "AA12") (pinfunction "GND_AA12") (pintype "power_in"))
      (node (ref "IC2") (pin "AA14") (pinfunction "GND_AA14") (pintype "power_in"))
      (node (ref "IC2") (pin "AA16") (pinfunction "GND_AA16") (pintype "power_in"))
      (node (ref "IC2") (pin "AA18") (pinfunction "GND_AA18") (pintype "power_in"))
      (node (ref "IC2") (pin "AA20") (pinfunction "GND_AA20") (pintype "power_in"))
      (node (ref "IC2") (pin "AA22") (pinfunction "GND_AA22") (pintype "power_in"))
      (node (ref "IC2") (pin "AA26") (pinfunction "GND_AA26") (pintype "power_in"))
      (node (ref "IC2") (pin "AB13") (pinfunction "GND_AB13") (pintype "power_in"))
      (node (ref "IC2") (pin "AB15") (pinfunction "GND_AB15") (pintype "power_in"))
      (node (ref "IC2") (pin "AB17") (pinfunction "GND_AB17") (pintype "power_in"))
      (node (ref "IC2") (pin "AB19") (pinfunction "GND_AB19") (pintype "power_in"))
      (node (ref "IC2") (pin "AB21") (pinfunction "GND_AB21") (pintype "power_in"))
      (node (ref "IC2") (pin "AB23") (pinfunction "GND_AB23") (pintype "power_in"))
      (node (ref "IC2") (pin "AB33") (pinfunction "GND_AB33") (pintype "power_in"))
      (node (ref "IC2") (pin "AB8") (pinfunction "GND_AB8") (pintype "power_in"))
      (node (ref "IC2") (pin "AC12") (pinfunction "GND_AC12") (pintype "power_in"))
      (node (ref "IC2") (pin "AC14") (pinfunction "GND_AC14") (pintype "power_in"))
      (node (ref "IC2") (pin "AC16") (pinfunction "GND_AC16") (pintype "power_in"))
      (node (ref "IC2") (pin "AC18") (pinfunction "GND_AC18") (pintype "power_in"))
      (node (ref "IC2") (pin "AC20") (pinfunction "GND_AC20") (pintype "power_in"))
      (node (ref "IC2") (pin "AC22") (pinfunction "GND_AC22") (pintype "power_in"))
      (node (ref "IC2") (pin "AC30") (pinfunction "GND_AC30") (pintype "power_in"))
      (node (ref "IC2") (pin "AC5") (pinfunction "GND_AC5") (pintype "power_in"))
      (node (ref "IC2") (pin "AD15") (pinfunction "GND_AD15") (pintype "power_in"))
      (node (ref "IC2") (pin "AD17") (pinfunction "GND_AD17") (pintype "power_in"))
      (node (ref "IC2") (pin "AD19") (pinfunction "GND_AD19") (pintype "power_in"))
      (node (ref "IC2") (pin "AD2") (pinfunction "GND_AD2") (pintype "power_in"))
      (node (ref "IC2") (pin "AD21") (pinfunction "GND_AD21") (pintype "power_in"))
      (node (ref "IC2") (pin "AD27") (pinfunction "GND_AD27") (pintype "power_in"))
      (node (ref "IC2") (pin "AE16") (pinfunction "GND_AE16") (pintype "power_in"))
      (node (ref "IC2") (pin "AE18") (pinfunction "GND_AE18") (pintype "power_in"))
      (node (ref "IC2") (pin "AE20") (pinfunction "GND_AE20") (pintype "power_in"))
      (node (ref "IC2") (pin "AE22") (pinfunction "GND_AE22") (pintype "power_in"))
      (node (ref "IC2") (pin "AE24") (pinfunction "GND_AE24") (pintype "power_in"))
      (node (ref "IC2") (pin "AE34") (pinfunction "GND_AE34") (pintype "power_in"))
      (node (ref "IC2") (pin "AE9") (pinfunction "GND_AE9") (pintype "power_in"))
      (node (ref "IC2") (pin "AF13") (pinfunction "GND_AF13") (pintype "power_in"))
      (node (ref "IC2") (pin "AF14") (pinfunction "GND_AF14") (pintype "power_in"))
      (node (ref "IC2") (pin "AF15") (pinfunction "GND_AF15") (pintype "power_in"))
      (node (ref "IC2") (pin "AF16") (pinfunction "GND_AF16") (pintype "power_in"))
      (node (ref "IC2") (pin "AF17") (pinfunction "GND_AF17") (pintype "power_in"))
      (node (ref "IC2") (pin "AF18") (pinfunction "GND_AF18") (pintype "power_in"))
      (node (ref "IC2") (pin "AF19") (pinfunction "GND_AF19") (pintype "power_in"))
      (node (ref "IC2") (pin "AF20") (pinfunction "GND_AF20") (pintype "power_in"))
      (node (ref "IC2") (pin "AF21") (pinfunction "GND_AF21") (pintype "power_in"))
      (node (ref "IC2") (pin "AF22") (pinfunction "GND_AF22") (pintype "power_in"))
      (node (ref "IC2") (pin "AF31") (pinfunction "GND_AF31") (pintype "power_in"))
      (node (ref "IC2") (pin "AF6") (pinfunction "GND_AF6") (pintype "power_in"))
      (node (ref "IC2") (pin "AG13") (pinfunction "GND_AG13") (pintype "power_in"))
      (node (ref "IC2") (pin "AG22") (pinfunction "GND_AG22") (pintype "power_in"))
      (node (ref "IC2") (pin "AG23") (pinfunction "GND_AG23") (pintype "power_in"))
      (node (ref "IC2") (pin "AG28") (pinfunction "GND_AG28") (pintype "power_in"))
      (node (ref "IC2") (pin "AG3") (pinfunction "GND_AG3") (pintype "power_in"))
      (node (ref "IC2") (pin "AH10") (pinfunction "GND_AH10") (pintype "power_in"))
      (node (ref "IC2") (pin "AH12") (pinfunction "GND_AH12") (pintype "power_in"))
      (node (ref "IC2") (pin "AH13") (pinfunction "GND_AH13") (pintype "power_in"))
      (node (ref "IC2") (pin "AH15") (pinfunction "GND_AH15") (pintype "power_in"))
      (node (ref "IC2") (pin "AH17") (pinfunction "GND_AH17") (pintype "power_in"))
      (node (ref "IC2") (pin "AH19") (pinfunction "GND_AH19") (pintype "power_in"))
      (node (ref "IC2") (pin "AH21") (pinfunction "GND_AH21") (pintype "power_in"))
      (node (ref "IC2") (pin "AH23") (pinfunction "GND_AH23") (pintype "power_in"))
      (node (ref "IC2") (pin "AH25") (pinfunction "GND_AH25") (pintype "power_in"))
      (node (ref "IC2") (pin "AJ12") (pinfunction "GND_AJ12") (pintype "power_in"))
      (node (ref "IC2") (pin "AJ23") (pinfunction "GND_AJ23") (pintype "power_in"))
      (node (ref "IC2") (pin "AJ32") (pinfunction "GND_AJ32") (pintype "power_in"))
      (node (ref "IC2") (pin "AJ7") (pinfunction "GND_AJ7") (pintype "power_in"))
      (node (ref "IC2") (pin "AK12") (pinfunction "GND_AK12") (pintype "power_in"))
      (node (ref "IC2") (pin "AK14") (pinfunction "GND_AK14") (pintype "power_in"))
      (node (ref "IC2") (pin "AK16") (pinfunction "GND_AK16") (pintype "power_in"))
      (node (ref "IC2") (pin "AK18") (pinfunction "GND_AK18") (pintype "power_in"))
      (node (ref "IC2") (pin "AK20") (pinfunction "GND_AK20") (pintype "power_in"))
      (node (ref "IC2") (pin "AK22") (pinfunction "GND_AK22") (pintype "power_in"))
      (node (ref "IC2") (pin "AK23") (pinfunction "GND_AK23") (pintype "power_in"))
      (node (ref "IC2") (pin "AK24") (pinfunction "GND_AK24") (pintype "power_in"))
      (node (ref "IC2") (pin "AK29") (pinfunction "GND_AK29") (pintype "power_in"))
      (node (ref "IC2") (pin "AK4") (pinfunction "GND_AK4") (pintype "power_in"))
      (node (ref "IC2") (pin "AL1") (pinfunction "GND_AL1") (pintype "power_in"))
      (node (ref "IC2") (pin "AL11") (pinfunction "GND_AL11") (pintype "power_in"))
      (node (ref "IC2") (pin "AL12") (pinfunction "GND_AL12") (pintype "power_in"))
      (node (ref "IC2") (pin "AL23") (pinfunction "GND_AL23") (pintype "power_in"))
      (node (ref "IC2") (pin "AL26") (pinfunction "GND_AL26") (pintype "power_in"))
      (node (ref "IC2") (pin "AM12") (pinfunction "GND_AM12") (pintype "power_in"))
      (node (ref "IC2") (pin "AM13") (pinfunction "GND_AM13") (pintype "power_in"))
      (node (ref "IC2") (pin "AM15") (pinfunction "GND_AM15") (pintype "power_in"))
      (node (ref "IC2") (pin "AM17") (pinfunction "GND_AM17") (pintype "power_in"))
      (node (ref "IC2") (pin "AM19") (pinfunction "GND_AM19") (pintype "power_in"))
      (node (ref "IC2") (pin "AM21") (pinfunction "GND_AM21") (pintype "power_in"))
      (node (ref "IC2") (pin "AM23") (pinfunction "GND_AM23") (pintype "power_in"))
      (node (ref "IC2") (pin "AM24") (pinfunction "GND_AM24") (pintype "power_in"))
      (node (ref "IC2") (pin "AM33") (pinfunction "GND_AM33") (pintype "power_in"))
      (node (ref "IC2") (pin "AM8") (pinfunction "GND_AM8") (pintype "power_in"))
      (node (ref "IC2") (pin "AN12") (pinfunction "GND_AN12") (pintype "power_in"))
      (node (ref "IC2") (pin "AN24") (pinfunction "GND_AN24") (pintype "power_in"))
      (node (ref "IC2") (pin "AN30") (pinfunction "GND_AN30") (pintype "power_in"))
      (node (ref "IC2") (pin "AN5") (pinfunction "GND_AN5") (pintype "power_in"))
      (node (ref "IC2") (pin "AP12") (pinfunction "GND_AP12") (pintype "power_in"))
      (node (ref "IC2") (pin "AP14") (pinfunction "GND_AP14") (pintype "power_in"))
      (node (ref "IC2") (pin "AP16") (pinfunction "GND_AP16") (pintype "power_in"))
      (node (ref "IC2") (pin "AP18") (pinfunction "GND_AP18") (pintype "power_in"))
      (node (ref "IC2") (pin "AP2") (pinfunction "GND_AP2") (pintype "power_in"))
      (node (ref "IC2") (pin "AP20") (pinfunction "GND_AP20") (pintype "power_in"))
      (node (ref "IC2") (pin "AP22") (pinfunction "GND_AP22") (pintype "power_in"))
      (node (ref "IC2") (pin "AP24") (pinfunction "GND_AP24") (pintype "power_in"))
      (node (ref "IC2") (pin "AP27") (pinfunction "GND_AP27") (pintype "power_in"))
      (node (ref "IC2") (pin "B12") (pinfunction "GND_B12") (pintype "power_in"))
      (node (ref "IC2") (pin "B24") (pinfunction "GND_B24") (pintype "power_in"))
      (node (ref "IC2") (pin "B33") (pinfunction "GND_B33") (pintype "power_in"))
      (node (ref "IC2") (pin "B8") (pinfunction "GND_B8") (pintype "power_in"))
      (node (ref "IC2") (pin "C12") (pinfunction "GND_C12") (pintype "power_in"))
      (node (ref "IC2") (pin "C13") (pinfunction "GND_C13") (pintype "power_in"))
      (node (ref "IC2") (pin "C15") (pinfunction "GND_C15") (pintype "power_in"))
      (node (ref "IC2") (pin "C17") (pinfunction "GND_C17") (pintype "power_in"))
      (node (ref "IC2") (pin "C19") (pinfunction "GND_C19") (pintype "power_in"))
      (node (ref "IC2") (pin "C21") (pinfunction "GND_C21") (pintype "power_in"))
      (node (ref "IC2") (pin "C23") (pinfunction "GND_C23") (pintype "power_in"))
      (node (ref "IC2") (pin "C24") (pinfunction "GND_C24") (pintype "power_in"))
      (node (ref "IC2") (pin "C30") (pinfunction "GND_C30") (pintype "power_in"))
      (node (ref "IC2") (pin "C5") (pinfunction "GND_C5") (pintype "power_in"))
      (node (ref "IC2") (pin "D12") (pinfunction "GND_D12") (pintype "power_in"))
      (node (ref "IC2") (pin "D2") (pinfunction "GND_D2") (pintype "power_in"))
      (node (ref "IC2") (pin "D23") (pinfunction "GND_D23") (pintype "power_in"))
      (node (ref "IC2") (pin "D27") (pinfunction "GND_D27") (pintype "power_in"))
      (node (ref "IC2") (pin "E12") (pinfunction "GND_E12") (pintype "power_in"))
      (node (ref "IC2") (pin "E14") (pinfunction "GND_E14") (pintype "power_in"))
      (node (ref "IC2") (pin "E16") (pinfunction "GND_E16") (pintype "power_in"))
      (node (ref "IC2") (pin "E18") (pinfunction "GND_E18") (pintype "power_in"))
      (node (ref "IC2") (pin "E20") (pinfunction "GND_E20") (pintype "power_in"))
      (node (ref "IC2") (pin "E22") (pinfunction "GND_E22") (pintype "power_in"))
      (node (ref "IC2") (pin "E23") (pinfunction "GND_E23") (pintype "power_in"))
      (node (ref "IC2") (pin "E24") (pinfunction "GND_E24") (pintype "power_in"))
      (node (ref "IC2") (pin "E34") (pinfunction "GND_E34") (pintype "power_in"))
      (node (ref "IC2") (pin "E9") (pinfunction "GND_E9") (pintype "power_in"))
      (node (ref "IC2") (pin "F12") (pinfunction "GND_F12") (pintype "power_in"))
      (node (ref "IC2") (pin "F23") (pinfunction "GND_F23") (pintype "power_in"))
      (node (ref "IC2") (pin "F31") (pinfunction "GND_F31") (pintype "power_in"))
      (node (ref "IC2") (pin "F6") (pinfunction "GND_F6") (pintype "power_in"))
      (node (ref "IC2") (pin "G12") (pinfunction "GND_G12") (pintype "power_in"))
      (node (ref "IC2") (pin "G13") (pinfunction "GND_G13") (pintype "power_in"))
      (node (ref "IC2") (pin "G15") (pinfunction "GND_G15") (pintype "power_in"))
      (node (ref "IC2") (pin "G17") (pinfunction "GND_G17") (pintype "power_in"))
      (node (ref "IC2") (pin "G19") (pinfunction "GND_G19") (pintype "power_in"))
      (node (ref "IC2") (pin "G21") (pinfunction "GND_G21") (pintype "power_in"))
      (node (ref "IC2") (pin "G23") (pinfunction "GND_G23") (pintype "power_in"))
      (node (ref "IC2") (pin "G28") (pinfunction "GND_G28") (pintype "power_in"))
      (node (ref "IC2") (pin "G3") (pinfunction "GND_G3") (pintype "power_in"))
      (node (ref "IC2") (pin "H10") (pinfunction "GND_H10") (pintype "power_in"))
      (node (ref "IC2") (pin "H13") (pinfunction "GND_H13") (pintype "power_in"))
      (node (ref "IC2") (pin "H22") (pinfunction "GND_H22") (pintype "power_in"))
      (node (ref "IC2") (pin "H23") (pinfunction "GND_H23") (pintype "power_in"))
      (node (ref "IC2") (pin "H25") (pinfunction "GND_H25") (pintype "power_in"))
      (node (ref "IC2") (pin "J13") (pinfunction "GND_J13") (pintype "power_in"))
      (node (ref "IC2") (pin "J14") (pinfunction "GND_J14") (pintype "power_in"))
      (node (ref "IC2") (pin "J15") (pinfunction "GND_J15") (pintype "power_in"))
      (node (ref "IC2") (pin "J16") (pinfunction "GND_J16") (pintype "power_in"))
      (node (ref "IC2") (pin "J17") (pinfunction "GND_J17") (pintype "power_in"))
      (node (ref "IC2") (pin "J18") (pinfunction "GND_J18") (pintype "power_in"))
      (node (ref "IC2") (pin "J19") (pinfunction "GND_J19") (pintype "power_in"))
      (node (ref "IC2") (pin "J20") (pinfunction "GND_J20") (pintype "power_in"))
      (node (ref "IC2") (pin "J21") (pinfunction "GND_J21") (pintype "power_in"))
      (node (ref "IC2") (pin "J22") (pinfunction "GND_J22") (pintype "power_in"))
      (node (ref "IC2") (pin "J32") (pinfunction "GND_J32") (pintype "power_in"))
      (node (ref "IC2") (pin "J7") (pinfunction "GND_J7") (pintype "power_in"))
      (node (ref "IC2") (pin "K15") (pinfunction "GND_K15") (pintype "power_in"))
      (node (ref "IC2") (pin "K17") (pinfunction "GND_K17") (pintype "power_in"))
      (node (ref "IC2") (pin "K19") (pinfunction "GND_K19") (pintype "power_in"))
      (node (ref "IC2") (pin "K29") (pinfunction "GND_K29") (pintype "power_in"))
      (node (ref "IC2") (pin "K4") (pinfunction "GND_K4") (pintype "power_in"))
      (node (ref "IC2") (pin "L1") (pinfunction "GND_L1") (pintype "power_in"))
      (node (ref "IC2") (pin "L11") (pinfunction "GND_L11") (pintype "power_in"))
      (node (ref "IC2") (pin "L14") (pinfunction "GND_L14") (pintype "power_in"))
      (node (ref "IC2") (pin "L16") (pinfunction "GND_L16") (pintype "power_in"))
      (node (ref "IC2") (pin "L18") (pinfunction "GND_L18") (pintype "power_in"))
      (node (ref "IC2") (pin "L20") (pinfunction "GND_L20") (pintype "power_in"))
      (node (ref "IC2") (pin "L26") (pinfunction "GND_L26") (pintype "power_in"))
      (node (ref "IC2") (pin "M13") (pinfunction "GND_M13") (pintype "power_in"))
      (node (ref "IC2") (pin "M15") (pinfunction "GND_M15") (pintype "power_in"))
      (node (ref "IC2") (pin "M17") (pinfunction "GND_M17") (pintype "power_in"))
      (node (ref "IC2") (pin "M19") (pinfunction "GND_M19") (pintype "power_in"))
      (node (ref "IC2") (pin "M21") (pinfunction "GND_M21") (pintype "power_in"))
      (node (ref "IC2") (pin "M23") (pinfunction "GND_M23") (pintype "power_in"))
      (node (ref "IC2") (pin "M33") (pinfunction "GND_M33") (pintype "power_in"))
      (node (ref "IC2") (pin "M8") (pinfunction "GND_M8") (pintype "power_in"))
      (node (ref "IC2") (pin "N12") (pinfunction "GND_N12") (pintype "power_in"))
      (node (ref "IC2") (pin "N14") (pinfunction "GND_N14") (pintype "power_in"))
      (node (ref "IC2") (pin "N16") (pinfunction "GND_N16") (pintype "power_in"))
      (node (ref "IC2") (pin "N18") (pinfunction "GND_N18") (pintype "power_in"))
      (node (ref "IC2") (pin "N20") (pinfunction "GND_N20") (pintype "power_in"))
      (node (ref "IC2") (pin "N22") (pinfunction "GND_N22") (pintype "power_in"))
      (node (ref "IC2") (pin "N30") (pinfunction "GND_N30") (pintype "power_in"))
      (node (ref "IC2") (pin "N5") (pinfunction "GND_N5") (pintype "power_in"))
      (node (ref "IC2") (pin "P13") (pinfunction "GND_P13") (pintype "power_in"))
      (node (ref "IC2") (pin "P15") (pinfunction "GND_P15") (pintype "power_in"))
      (node (ref "IC2") (pin "P17") (pinfunction "GND_P17") (pintype "power_in"))
      (node (ref "IC2") (pin "P19") (pinfunction "GND_P19") (pintype "power_in"))
      (node (ref "IC2") (pin "P2") (pinfunction "GND_P2") (pintype "power_in"))
      (node (ref "IC2") (pin "P21") (pinfunction "GND_P21") (pintype "power_in"))
      (node (ref "IC2") (pin "P23") (pinfunction "GND_P23") (pintype "power_in"))
      (node (ref "IC2") (pin "P27") (pinfunction "GND_P27") (pintype "power_in"))
      (node (ref "IC2") (pin "R12") (pinfunction "GND_R12") (pintype "power_in"))
      (node (ref "IC2") (pin "R14") (pinfunction "GND_R14") (pintype "power_in"))
      (node (ref "IC2") (pin "R16") (pinfunction "GND_R16") (pintype "power_in"))
      (node (ref "IC2") (pin "R18") (pinfunction "GND_R18") (pintype "power_in"))
      (node (ref "IC2") (pin "R20") (pinfunction "GND_R20") (pintype "power_in"))
      (node (ref "IC2") (pin "R22") (pinfunction "GND_R22") (pintype "power_in"))
      (node (ref "IC2") (pin "R24") (pinfunction "GND_R24") (pintype "power_in"))
      (node (ref "IC2") (pin "R34") (pinfunction "GND_R34") (pintype "power_in"))
      (node (ref "IC2") (pin "R9") (pinfunction "GND_R9") (pintype "power_in"))
      (node (ref "IC2") (pin "T13") (pinfunction "GND_T13") (pintype "power_in"))
      (node (ref "IC2") (pin "T15") (pinfunction "GND_T15") (pintype "power_in"))
      (node (ref "IC2") (pin "T17") (pinfunction "GNDADC_0_T17") (pintype "power_in"))
      (node (ref "IC2") (pin "T19") (pinfunction "GND_T19") (pintype "power_in"))
      (node (ref "IC2") (pin "T21") (pinfunction "GND_T21") (pintype "power_in"))
      (node (ref "IC2") (pin "T23") (pinfunction "GND_T23") (pintype "power_in"))
      (node (ref "IC2") (pin "T31") (pinfunction "GND_T31") (pintype "power_in"))
      (node (ref "IC2") (pin "T6") (pinfunction "GND_T6") (pintype "power_in"))
      (node (ref "IC2") (pin "U12") (pinfunction "GND_U12") (pintype "power_in"))
      (node (ref "IC2") (pin "U14") (pinfunction "GND_U14") (pintype "power_in"))
      (node (ref "IC2") (pin "U16") (pinfunction "GND_U16") (pintype "power_in"))
      (node (ref "IC2") (pin "U17") (pinfunction "VREFN_0_U17") (pintype "input"))
      (node (ref "IC2") (pin "U20") (pinfunction "GND_U20") (pintype "power_in"))
      (node (ref "IC2") (pin "U22") (pinfunction "GND_U22") (pintype "power_in"))
      (node (ref "IC2") (pin "U28") (pinfunction "GND_U28") (pintype "power_in"))
      (node (ref "IC2") (pin "U3") (pinfunction "GND_U3") (pintype "power_in"))
      (node (ref "IC2") (pin "V10") (pinfunction "GND_V10") (pintype "power_in"))
      (node (ref "IC2") (pin "V13") (pinfunction "GND_V13") (pintype "power_in"))
      (node (ref "IC2") (pin "V15") (pinfunction "GND_V15") (pintype "power_in"))
      (node (ref "IC2") (pin "V19") (pinfunction "GND_V19") (pintype "power_in"))
      (node (ref "IC2") (pin "V21") (pinfunction "GND_V21") (pintype "power_in"))
      (node (ref "IC2") (pin "V23") (pinfunction "GND_V23") (pintype "power_in"))
      (node (ref "IC2") (pin "V25") (pinfunction "GND_V25") (pintype "power_in"))
      (node (ref "IC2") (pin "W12") (pinfunction "GND_W12") (pintype "power_in"))
      (node (ref "IC2") (pin "W14") (pinfunction "GND_W14") (pintype "power_in"))
      (node (ref "IC2") (pin "W16") (pinfunction "GND_W16") (pintype "power_in"))
      (node (ref "IC2") (pin "W20") (pinfunction "GND_W20") (pintype "power_in"))
      (node (ref "IC2") (pin "W22") (pinfunction "GND_W22") (pintype "power_in"))
      (node (ref "IC2") (pin "W32") (pinfunction "GND_W32") (pintype "power_in"))
      (node (ref "IC2") (pin "W7") (pinfunction "GND_W7") (pintype "power_in"))
      (node (ref "IC2") (pin "Y13") (pinfunction "GND_Y13") (pintype "power_in"))
      (node (ref "IC2") (pin "Y15") (pinfunction "GND_Y15") (pintype "power_in"))
      (node (ref "IC2") (pin "Y17") (pinfunction "GND_Y17") (pintype "power_in"))
      (node (ref "IC2") (pin "Y19") (pinfunction "GND_Y19") (pintype "power_in"))
      (node (ref "IC2") (pin "Y21") (pinfunction "GND_Y21") (pintype "power_in"))
      (node (ref "IC2") (pin "Y23") (pinfunction "GND_Y23") (pintype "power_in"))
      (node (ref "IC2") (pin "Y29") (pinfunction "GND_Y29") (pintype "power_in"))
      (node (ref "IC2") (pin "Y4") (pinfunction "GND_Y4") (pintype "power_in"))
      (node (ref "IC45") (pin "3") (pinfunction "A_3") (pintype "passive"))
    )
    (net (code "3") (name "MGTAVCC_G10") (class "Default")
      (node (ref "C253") (pin "2") (pinfunction "2_2") (pintype "passive"))
      (node (ref "C254") (pin "2") (pinfunction "2_2") (pintype "passive"))
      (node (ref "C267") (pin "2") (pinfunction "2_2") (pintype "passive"))
      (node (ref "C730") (pin "2") (pinfunction "2_2") (pintype "passive"))
      (node (ref "C731") (pin "2") (pinfunction "2_2") (pintype "passive"))
      (node (ref "C734") (pin "2") (pinfunction "2_2") (pintype "passive"))
      (node (ref "C735") (pin "2") (pinfunction "2_2") (pintype "passive"))
      (node (ref "C736") (pin "2") (pinfunction "2_2") (pintype "passive"))
      (node (ref "C737") (pin "2") (pinfunction "2_2") (pintype "passive"))
      (node (ref "FB5") (pin "2") (pinfunction "-_2") (pintype "passive"))
      (node (ref "IC2") (pin "AG15") (pinfunction "MGTAVCC_G10_AG15") (pintype "power_in"))
      (node (ref "IC2") (pin "AG17") (pinfunction "MGTAVCC_G10_AG17") (pintype "power_in"))
      (node (ref "IC2") (pin "AG19") (pinfunction "MGTAVCC_G10_AG19") (pintype "power_in"))
      (node (ref "IC2") (pin "AG21") (pinfunction "MGTAVCC_G10_AG21") (pintype "power_in"))
      (node (ref "IC2") (pin "AJ14") (pinfunction "MGTAVCC_G10_AJ14") (pintype "power_in"))
      (node (ref "IC2") (pin "AJ16") (pinfunction "MGTAVCC_G10_AJ16") (pintype "power_in"))
      (node (ref "IC2") (pin "AJ18") (pinfunction "MGTAVCC_G10_AJ18") (pintype "power_in"))
      (node (ref "IC2") (pin "AJ20") (pinfunction "MGTAVCC_G10_AJ20") (pintype "power_in"))
    )
    (net (code "4") (name "MGTAVCC_G11") (class "Default")
      (node (ref "C252") (pin "2") (pinfunction "2_2") (pintype "passive"))
      (node (ref "C262") (pin "2") (pinfunction "2_2") (pintype "passive"))
      (node (ref "C263") (pin "2") (pinfunction "2_2") (pintype "passive"))
      (node (ref "C272") (pin "2") (pinfunction "2_2") (pintype "passive"))
      (node (ref "C601") (pin "2") (pinfunction "2_2") (pintype "passive"))
      (node (ref "C603") (pin "2") (pinfunction "2_2") (pintype "passive"))
      (node (ref "C604") (pin "2") (pinfunction "2_2") (pintype "passive"))
      (node (ref "C732") (pin "2") (pinfunction "2_2") (pintype "passive"))
      (node (ref "C733") (pin "2") (pinfunction "2_2") (pintype "passive"))
      (node (ref "FB6") (pin "2") (pinfunction "-_2") (pintype "passive"))
      (node (ref "IC2") (pin "F14") (pinfunction "MGTAVCC_G11_F14") (pintype "power_in"))
      (node (ref "IC2") (pin "F16") (pinfunction "MGTAVCC_G11_F16") (pintype "power_in"))
      (node (ref "IC2") (pin "F18") (pinfunction "MGTAVCC_G11_F18") (pintype "power_in"))
      (node (ref "IC2") (pin "F20") (pinfunction "MGTAVCC_G11_F20") (pintype "power_in"))
      (node (ref "IC2") (pin "H15") (pinfunction "MGTAVCC_G11_H15") (pintype "power_in"))
      (node (ref "IC2") (pin "H17") (pinfunction "MGTAVCC_G11_H17") (pintype "power_in"))
      (node (ref "IC2") (pin "H19") (pinfunction "MGTAVCC_G11_H19") (pintype "power_in"))
      (node (ref "IC2") (pin "H21") (pinfunction "MGTAVCC_G11_H21") (pintype "power_in"))
    )
    (net (code "5") (name "MGTAVTT_G10") (class "Default")
      (node (ref "C251") (pin "2") (pinfunction "2_2") (pintype "passive"))
      (node (ref "C255") (pin "2") (pinfunction "2_2") (pintype "passive"))
      (node (ref "C257") (pin "2") (pinfunction "2_2") (pintype "passive"))
      (node (ref "C600") (pin "2") (pinfunction "2_2") (pintype "passive"))
      (node (ref "C605") (pin "2") (pinfunction "2_2") (pintype "passive"))
      (node (ref "C722") (pin "2") (pinfunction "2_2") (pintype "passive"))
      (node (ref "C725") (pin "2") (pinfunction "2_2") (pintype "passive"))
      (node (ref "C726") (pin "2") (pinfunction "2_2") (pintype "passive"))
      (node (ref "C729") (pin "2") (pinfunction "2_2") (pintype "passive"))
      (node (ref "FB8") (pin "2") (pinfunction "-_2") (pintype "passive"))
      (node (ref "IC2") (pin "AJ22") (pinfunction "MGTAVTT_G10_AJ22") (pintype "power_in"))
      (node (ref "IC2") (pin "AL13") (pinfunction "MGTAVTT_G10_AL13") (pintype "power_in"))
      (node (ref "IC2") (pin "AL15") (pinfunction "MGTAVTT_G10_AL15") (pintype "power_in"))
      (node (ref "IC2") (pin "AL17") (pinfunction "MGTAVTT_G10_AL17") (pintype "power_in"))
      (node (ref "IC2") (pin "AL19") (pinfunction "MGTAVTT_G10_AL19") (pintype "power_in"))
      (node (ref "IC2") (pin "AL21") (pinfunction "MGTAVTT_G10_AL21") (pintype "power_in"))
      (node (ref "IC2") (pin "AN14") (pinfunction "MGTAVTT_G10_AN14") (pintype "power_in"))
      (node (ref "IC2") (pin "AN16") (pinfunction "MGTAVTT_G10_AN16") (pintype "power_in"))
      (node (ref "IC2") (pin "AN18") (pinfunction "MGTAVTT_G10_AN18") (pintype "power_in"))
      (node (ref "IC2") (pin "AN20") (pinfunction "MGTAVTT_G10_AN20") (pintype "power_in"))
      (node (ref "IC2") (pin "AN22") (pinfunction "MGTAVTT_G10_AN22") (pintype "power_in"))
    )
    (net (code "6") (name "MGTAVTT_G11") (class "Default")
      (node (ref "C256") (pin "2") (pinfunction "2_2") (pintype "passive"))
      (node (ref "C258") (pin "2") (pinfunction "2_2") (pintype "passive"))
      (node (ref "C259") (pin "2") (pinfunction "2_2") (pintype "passive"))
      (node (ref "C268") (pin "2") (pinfunction "2_2") (pintype "passive"))
      (node (ref "C599") (pin "2") (pinfunction "2_2") (pintype "passive"))
      (node (ref "C723") (pin "2") (pinfunction "2_2") (pintype "passive"))
      (node (ref "C724") (pin "2") (pinfunction "2_2") (pintype "passive"))
      (node (ref "C727") (pin "2") (pinfunction "2_2") (pintype "passive"))
      (node (ref "C728") (pin "2") (pinfunction "2_2") (pintype "passive"))
      (node (ref "FB7") (pin "2") (pinfunction "-_2") (pintype "passive"))
      (node (ref "IC2") (pin "B14") (pinfunction "MGTAVTT_G11_B14") (pintype "power_in"))
      (node (ref "IC2") (pin "B16") (pinfunction "MGTAVTT_G11_B16") (pintype "power_in"))
      (node (ref "IC2") (pin "B18") (pinfunction "MGTAVTT_G11_B18") (pintype "power_in"))
      (node (ref "IC2") (pin "B20") (pinfunction "MGTAVTT_G11_B20") (pintype "power_in"))
      (node (ref "IC2") (pin "B22") (pinfunction "MGTAVTT_G11_B22") (pintype "power_in"))
      (node (ref "IC2") (pin "D13") (pinfunction "MGTAVTT_G11_D13") (pintype "power_in"))
      (node (ref "IC2") (pin "D15") (pinfunction "MGTAVTT_G11_D15") (pintype "power_in"))
      (node (ref "IC2") (pin "D17") (pinfunction "MGTAVTT_G11_D17") (pintype "power_in"))
      (node (ref "IC2") (pin "D19") (pinfunction "MGTAVTT_G11_D19") (pintype "power_in"))
      (node (ref "IC2") (pin "D21") (pinfunction "MGTAVTT_G11_D21") (pintype "power_in"))
      (node (ref "IC2") (pin "F22") (pinfunction "MGTAVTT_G11_F22") (pintype "power_in"))
    )
    (net (code "7") (name "P1V0") (class "Default")
      (node (ref "C229") (pin "2") (pinfunction "2_2") (pintype "passive"))
      (node (ref "C230") (pin "1") (pinfunction "1_1") (pintype "passive"))
      (node (ref "C231") (pin "1") (pinfunction "1_1") (pintype "passive"))
      (node (ref "C232") (pin "2") (pinfunction "2_2") (pintype "passive"))
      (node (ref "C233") (pin "2") (pinfunction "2_2") (pintype "passive"))
      (node (ref "C234") (pin "2") (pinfunction "2_2") (pintype "passive"))
      (node (ref "C235") (pin "2") (pinfunction "2_2") (pintype "passive"))
      (node (ref "C236") (pin "2") (pinfunction "2_2") (pintype "passive"))
      (node (ref "C237") (pin "2") (pinfunction "2_2") (pintype "passive"))
      (node (ref "C238") (pin "2") (pinfunction "2_2") (pintype "passive"))
      (node (ref "C239") (pin "2") (pinfunction "2_2") (pintype "passive"))
      (node (ref "C240") (pin "2") (pinfunction "2_2") (pintype "passive"))
      (node (ref "C241") (pin "2") (pinfunction "2_2") (pintype "passive"))
      (node (ref "C242") (pin "2") (pinfunction "2_2") (pintype "passive"))
      (node (ref "C283") (pin "2") (pinfunction "2_2") (pintype "passive"))
      (node (ref "C284") (pin "2") (pinfunction "2_2") (pintype "passive"))
      (node (ref "C285") (pin "2") (pinfunction "2_2") (pintype "passive"))
      (node (ref "C286") (pin "2") (pinfunction "2_2") (pintype "passive"))
      (node (ref "C287") (pin "2") (pinfunction "2_2") (pintype "passive"))
      (node (ref "C288") (pin "2") (pinfunction "2_2") (pintype "passive"))
      (node (ref "C291") (pin "2") (pinfunction "2_2") (pintype "passive"))
      (node (ref "C292") (pin "2") (pinfunction "2_2") (pintype "passive"))
      (node (ref "C293") (pin "2") (pinfunction "2_2") (pintype "passive"))
      (node (ref "C294") (pin "2") (pinfunction "2_2") (pintype "passive"))
      (node (ref "C295") (pin "2") (pinfunction "2_2") (pintype "passive"))
      (node (ref "C296") (pin "2") (pinfunction "2_2") (pintype "passive"))
      (node (ref "C549") (pin "2") (pinfunction "2_2") (pintype "passive"))
      (node (ref "C550") (pin "2") (pinfunction "2_2") (pintype "passive"))
      (node (ref "C551") (pin "2") (pinfunction "2_2") (pintype "passive"))
      (node (ref "C552") (pin "2") (pinfunction "2_2") (pintype "passive"))
      (node (ref "C553") (pin "2") (pinfunction "2_2") (pintype "passive"))
      (node (ref "C554") (pin "2") (pinfunction "2_2") (pintype "passive"))
      (node (ref "C555") (pin "2") (pinfunction "2_2") (pintype "passive"))
      (node (ref "C556") (pin "2") (pinfunction "2_2") (pintype "passive"))
      (node (ref "C557") (pin "2") (pinfunction "2_2") (pintype "passive"))
      (node (ref "C558") (pin "2") (pinfunction "2_2") (pintype "passive"))
      (node (ref "C559") (pin "2") (pinfunction "2_2") (pintype "passive"))
      (node (ref "C560") (pin "2") (pinfunction "2_2") (pintype "passive"))
      (node (ref "C561") (pin "2") (pinfunction "2_2") (pintype "passive"))
      (node (ref "C562") (pin "2") (pinfunction "2_2") (pintype "passive"))
      (node (ref "C563") (pin "2") (pinfunction "2_2") (pintype "passive"))
      (node (ref "C564") (pin "2") (pinfunction "2_2") (pintype "passive"))
      (node (ref "C565") (pin "2") (pinfunction "2_2") (pintype "passive"))
      (node (ref "C566") (pin "2") (pinfunction "2_2") (pintype "passive"))
      (node (ref "C576") (pin "2") (pinfunction "2_2") (pintype "passive"))
      (node (ref "C577") (pin "2") (pinfunction "2_2") (pintype "passive"))
      (node (ref "C578") (pin "2") (pinfunction "2_2") (pintype "passive"))
      (node (ref "C579") (pin "2") (pinfunction "2_2") (pintype "passive"))
      (node (ref "C580") (pin "2") (pinfunction "2_2") (pintype "passive"))
      (node (ref "C581") (pin "2") (pinfunction "2_2") (pintype "passive"))
      (node (ref "C582") (pin "2") (pinfunction "2_2") (pintype "passive"))
      (node (ref "C583") (pin "2") (pinfunction "2_2") (pintype "passive"))
      (node (ref "C585") (pin "2") (pinfunction "2_2") (pintype "passive"))
      (node (ref "C586") (pin "2") (pinfunction "2_2") (pintype "passive"))
      (node (ref "C602") (pin "1") (pinfunction "1_1") (pintype "passive"))
      (node (ref "C606") (pin "2") (pinfunction "2_2") (pintype "passive"))
      (node (ref "C607") (pin "2") (pinfunction "2_2") (pintype "passive"))
      (node (ref "C608") (pin "2") (pinfunction "2_2") (pintype "passive"))
      (node (ref "C609") (pin "2") (pinfunction "2_2") (pintype "passive"))
      (node (ref "C610") (pin "2") (pinfunction "2_2") (pintype "passive"))
      (node (ref "C611") (pin "2") (pinfunction "2_2") (pintype "passive"))
      (node (ref "C612") (pin "1") (pinfunction "1_1") (pintype "passive"))
      (node (ref "C740") (pin "2") (pinfunction "2_2") (pintype "passive"))
      (node (ref "C741") (pin "2") (pinfunction "2_2") (pintype "passive"))
      (node (ref "C742") (pin "2") (pinfunction "2_2") (pintype "passive"))
      (node (ref "C743") (pin "2") (pinfunction "2_2") (pintype "passive"))
      (node (ref "C744") (pin "2") (pinfunction "2_2") (pintype "passive"))
      (node (ref "C745") (pin "2") (pinfunction "2_2") (pintype "passive"))
      (node (ref "C746") (pin "2") (pinfunction "2_2") (pintype "passive"))
      (node (ref "C747") (pin "2") (pinfunction "2_2") (pintype "passive"))
      (node (ref "C748") (pin "2") (pinfunction "2_2") (pintype "passive"))
      (node (ref "FB5") (pin "1") (pinfunction "+_1") (pintype "passive"))
      (node (ref "FB6") (pin "1") (pinfunction "+_1") (pintype "passive"))
      (node (ref "IC2") (pin "AA15") (pinfunction "VCCINT_AA15") (pintype "power_in"))
      (node (ref "IC2") (pin "AA17") (pinfunction "VCCINT_AA17") (pintype "power_in"))
      (node (ref "IC2") (pin "AA19") (pinfunction "VCCINT_AA19") (pintype "power_in"))
      (node (ref "IC2") (pin "AB14") (pinfunction "VCCINT_AB14") (pintype "power_in"))
      (node (ref "IC2") (pin "AB16") (pinfunction "VCCINT_AB16") (pintype "power_in"))
      (node (ref "IC2") (pin "AB18") (pinfunction "VCCINT_AB18") (pintype "power_in"))
      (node (ref "IC2") (pin "AC15") (pinfunction "VCCINT_AC15") (pintype "power_in"))
      (node (ref "IC2") (pin "AC17") (pinfunction "VCCINT_AC17") (pintype "power_in"))
      (node (ref "IC2") (pin "AC19") (pinfunction "VCCINT_AC19") (pintype "power_in"))
      (node (ref "IC2") (pin "AD14") (pinfunction "VCCINT_AD14") (pintype "power_in"))
      (node (ref "IC2") (pin "AD16") (pinfunction "VCCINT_AD16") (pintype "power_in"))
      (node (ref "IC2") (pin "AD18") (pinfunction "VCCINT_AD18") (pintype "power_in"))
      (node (ref "IC2") (pin "AD20") (pinfunction "VCCINT_AD20") (pintype "power_in"))
      (node (ref "IC2") (pin "AD22") (pinfunction "VCCINT_AD22") (pintype "power_in"))
      (node (ref "IC2") (pin "AE15") (pinfunction "VCCINT_AE15") (pintype "power_in"))
      (node (ref "IC2") (pin "AE17") (pinfunction "VCCINT_AE17") (pintype "power_in"))
      (node (ref "IC2") (pin "AE19") (pinfunction "VCCINT_AE19") (pintype "power_in"))
      (node (ref "IC2") (pin "AE21") (pinfunction "VCCINT_AE21") (pintype "power_in"))
      (node (ref "IC2") (pin "K14") (pinfunction "VCCINT_K14") (pintype "power_in"))
      (node (ref "IC2") (pin "K16") (pinfunction "VCCINT_K16") (pintype "power_in"))
      (node (ref "IC2") (pin "K18") (pinfunction "VCCINT_K18") (pintype "power_in"))
      (node (ref "IC2") (pin "K20") (pinfunction "VCCINT_K20") (pintype "power_in"))
      (node (ref "IC2") (pin "L15") (pinfunction "VCCINT_L15") (pintype "power_in"))
      (node (ref "IC2") (pin "L17") (pinfunction "VCCINT_L17") (pintype "power_in"))
      (node (ref "IC2") (pin "L19") (pinfunction "VCCINT_L19") (pintype "power_in"))
      (node (ref "IC2") (pin "L21") (pinfunction "VCCINT_L21") (pintype "power_in"))
      (node (ref "IC2") (pin "M14") (pinfunction "VCCINT_M14") (pintype "power_in"))
      (node (ref "IC2") (pin "M16") (pinfunction "VCCINT_M16") (pintype "power_in"))
      (node (ref "IC2") (pin "M18") (pinfunction "VCCINT_M18") (pintype "power_in"))
      (node (ref "IC2") (pin "N15") (pinfunction "VCCINT_N15") (pintype "power_in"))
      (node (ref "IC2") (pin "N17") (pinfunction "VCCINT_N17") (pintype "power_in"))
      (node (ref "IC2") (pin "N19") (pinfunction "VCCINT_N19") (pintype "power_in"))
      (node (ref "IC2") (pin "P14") (pinfunction "VCCINT_P14") (pintype "power_in"))
      (node (ref "IC2") (pin "P16") (pinfunction "VCCINT_P16") (pintype "power_in"))
      (node (ref "IC2") (pin "P18") (pinfunction "VCCINT_P18") (pintype "power_in"))
      (node (ref "IC2") (pin "R15") (pinfunction "VCCINT_R15") (pintype "power_in"))
      (node (ref "IC2") (pin "R17") (pinfunction "VCCINT_R17") (pintype "power_in"))
      (node (ref "IC2") (pin "R19") (pinfunction "VCCINT_R19") (pintype "power_in"))
      (node (ref "IC2") (pin "T14") (pinfunction "VCCINT_T14") (pintype "power_in"))
      (node (ref "IC2") (pin "T16") (pinfunction "VCCINT_T16") (pintype "power_in"))
      (node (ref "IC2") (pin "U15") (pinfunction "VCCINT_U15") (pintype "power_in"))
      (node (ref "IC2") (pin "U19") (pinfunction "VCCINT_U19") (pintype "power_in"))
      (node (ref "IC2") (pin "V14") (pinfunction "VCCINT_V14") (pintype "power_in"))
      (node (ref "IC2") (pin "V16") (pinfunction "VCCINT_V16") (pintype "power_in"))
      (node (ref "IC2") (pin "W15") (pinfunction "VCCINT_W15") (pintype "power_in"))
      (node (ref "IC2") (pin "W19") (pinfunction "VCCINT_W19") (pintype "power_in"))
      (node (ref "IC2") (pin "Y14") (pinfunction "VCCINT_Y14") (pintype "power_in"))
      (node (ref "IC2") (pin "Y16") (pinfunction "VCCINT_Y16") (pintype "power_in"))
      (node (ref "IC2") (pin "Y18") (pinfunction "VCCINT_Y18") (pintype "power_in"))
      (node (ref "L10") (pin "1") (pintype "passive"))
    )
    (net (code "8") (name "P1V2") (class "Default")
      (node (ref "FB7") (pin "1") (pinfunction "+_1") (pintype "passive"))
      (node (ref "FB8") (pin "1") (pinfunction "+_1") (pintype "passive"))
    )
    (net (code "9") (name "P1V5") (class "Default")
      (node (ref "C106") (pin "2") (pinfunction "2_2") (pintype "passive"))
      (node (ref "C107") (pin "2") (pinfunction "2_2") (pintype "passive"))
      (node (ref "C446") (pin "2") (pinfunction "2_2") (pintype "passive"))
      (node (ref "C447") (pin "1") (pinfunction "1_1") (pintype "passive"))
      (node (ref "C448") (pin "2") (pinfunction "2_2") (pintype "passive"))
      (node (ref "C449") (pin "2") (pinfunction "2_2") (pintype "passive"))
      (node (ref "C450") (pin "2") (pinfunction "2_2") (pintype "passive"))
      (node (ref "C451") (pin "2") (pinfunction "2_2") (pintype "passive"))
      (node (ref "C465") (pin "2") (pinfunction "2_2") (pintype "passive"))
      (node (ref "C478") (pin "2") (pinfunction "2_2") (pintype "passive"))
      (node (ref "C636") (pin "2") (pinfunction "2_2") (pintype "passive"))
      (node (ref "C637") (pin "2") (pinfunction "2_2") (pintype "passive"))
      (node (ref "C638") (pin "1") (pinfunction "1_1") (pintype "passive"))
      (node (ref "C639") (pin "2") (pinfunction "2_2") (pintype "passive"))
      (node (ref "C640") (pin "2") (pinfunction "2_2") (pintype "passive"))
      (node (ref "C641") (pin "2") (pinfunction "2_2") (pintype "passive"))
      (node (ref "C642") (pin "2") (pinfunction "2_2") (pintype "passive"))
      (node (ref "C643") (pin "2") (pinfunction "2_2") (pintype "passive"))
      (node (ref "IC2") (pin "AD7") (pinfunction "VCCO_33_AD7") (pintype "power_in"))
      (node (ref "IC2") (pin "AE4") (pinfunction "VCCO_33_AE4") (pintype "power_in"))
      (node (ref "IC2") (pin "AF1") (pinfunction "VCCO_33_AF1") (pintype "power_in"))
      (node (ref "IC2") (pin "AF11") (pinfunction "VCCO_33_AF11") (pintype "power_in"))
      (node (ref "IC2") (pin "AG8") (pinfunction "VCCO_33_AG8") (pintype "power_in"))
      (node (ref "IC2") (pin "AH5") (pinfunction "VCCO_33_AH5") (pintype "power_in"))
      (node (ref "IC2") (pin "AJ2") (pinfunction "VCCO_32_AJ2") (pintype "power_in"))
      (node (ref "IC2") (pin "AK9") (pinfunction "VCCO_32_AK9") (pintype "power_in"))
      (node (ref "IC2") (pin "AL6") (pinfunction "VCCO_32_AL6") (pintype "power_in"))
      (node (ref "IC2") (pin "AM3") (pinfunction "VCCO_32_AM3") (pintype "power_in"))
      (node (ref "IC2") (pin "AN10") (pinfunction "VCCO_32_AN10") (pintype "power_in"))
      (node (ref "IC2") (pin "AP7") (pinfunction "VCCO_32_AP7") (pintype "power_in"))
    )
    (net (code "10") (name "P1V8") (class "Default") (node (ref "L12") (pin "1") (pintype "passive")))
    (net (code "11") (name "P3V3") (class "Default")
      (node (ref "C260") (pin "2") (pinfunction "2_2") (pintype "passive"))
      (node (ref "C261") (pin "2") (pinfunction "2_2") (pintype "passive"))
      (node (ref "IC2") (pin "L13") (pinfunction "VCCO_0_L13") (pintype "power_in"))
      (node (ref "IC2") (pin "T11") (pinfunction "VCCO_0_T11") (pintype "power_in"))
      (node (ref "R213") (pin "2") (pinfunction "2_2") (pintype "passive"))
    )
    (net (code "12") (name "PVADJ1") (class "Default")
      (node (ref "C676") (pin "1") (pinfunction "1_1") (pintype "passive"))
      (node (ref "C677") (pin "1") (pinfunction "1_1") (pintype "passive"))
      (node (ref "C678") (pin "1") (pinfunction "1_1") (pintype "passive"))
      (node (ref "C679") (pin "1") (pinfunction "1_1") (pintype "passive"))
      (node (ref "C680") (pin "2") (pinfunction "2_2") (pintype "passive"))
      (node (ref "C681") (pin "2") (pinfunction "2_2") (pintype "passive"))
      (node (ref "C682") (pin "2") (pinfunction "2_2") (pintype "passive"))
      (node (ref "C683") (pin "2") (pinfunction "2_2") (pintype "passive"))
      (node (ref "C684") (pin "2") (pinfunction "2_2") (pintype "passive"))
      (node (ref "C685") (pin "2") (pinfunction "2_2") (pintype "passive"))
      (node (ref "C686") (pin "2") (pinfunction "2_2") (pintype "passive"))
      (node (ref "C687") (pin "2") (pinfunction "2_2") (pintype "passive"))
      (node (ref "C688") (pin "2") (pinfunction "2_2") (pintype "passive"))
      (node (ref "C689") (pin "2") (pinfunction "2_2") (pintype "passive"))
      (node (ref "C690") (pin "2") (pinfunction "2_2") (pintype "passive"))
      (node (ref "C691") (pin "2") (pinfunction "2_2") (pintype "passive"))
      (node (ref "C692") (pin "2") (pinfunction "2_2") (pintype "passive"))
      (node (ref "C693") (pin "2") (pinfunction "2_2") (pintype "passive"))
      (node (ref "C694") (pin "2") (pinfunction "2_2") (pintype "passive"))
      (node (ref "C695") (pin "2") (pinfunction "2_2") (pintype "passive"))
      (node (ref "C696") (pin "2") (pinfunction "2_2") (pintype "passive"))
      (node (ref "C697") (pin "2") (pinfunction "2_2") (pintype "passive"))
      (node (ref "C698") (pin "2") (pinfunction "2_2") (pintype "passive"))
      (node (ref "C699") (pin "2") (pinfunction "2_2") (pintype "passive"))
      (node (ref "C700") (pin "2") (pinfunction "2_2") (pintype "passive"))
      (node (ref "C701") (pin "2") (pinfunction "2_2") (pintype "passive"))
      (node (ref "C702") (pin "2") (pinfunction "2_2") (pintype "passive"))
      (node (ref "C703") (pin "2") (pinfunction "2_2") (pintype "passive"))
      (node (ref "C704") (pin "2") (pinfunction "2_2") (pintype "passive"))
      (node (ref "C705") (pin "2") (pinfunction "2_2") (pintype "passive"))
      (node (ref "C706") (pin "2") (pinfunction "2_2") (pintype "passive"))
      (node (ref "C707") (pin "2") (pinfunction "2_2") (pintype "passive"))
      (node (ref "C708") (pin "2") (pinfunction "2_2") (pintype "passive"))
      (node (ref "C709") (pin "2") (pinfunction "2_2") (pintype "passive"))
      (node (ref "C710") (pin "2") (pinfunction "2_2") (pintype "passive"))
      (node (ref "C711") (pin "2") (pinfunction "2_2") (pintype "passive"))
      (node (ref "C719") (pin "2") (pinfunction "2_2") (pintype "passive"))
      (node (ref "C720") (pin "2") (pinfunction "2_2") (pintype "passive"))
      (node (ref "C721") (pin "2") (pinfunction "2_2") (pintype "passive"))
      (node (ref "IC2") (pin "A6") (pinfunction "VCCO_37_A6") (pintype "power_in"))
      (node (ref "IC2") (pin "AA6") (pinfunction "VCCO_34_AA6") (pintype "power_in"))
      (node (ref "IC2") (pin "AB3") (pinfunction "VCCO_34_AB3") (pintype "power_in"))
      (node (ref "IC2") (pin "AC10") (pinfunction "VCCO_34_AC10") (pintype "power_in"))
      (node (ref "IC2") (pin "B3") (pinfunction "VCCO_37_B3") (pintype "power_in"))
      (node (ref "IC2") (pin "C10") (pinfunction "VCCO_37_C10") (pintype "power_in"))
      (node (ref "IC2") (pin "D7") (pinfunction "VCCO_37_D7") (pintype "power_in"))
      (node (ref "IC2") (pin "E4") (pinfunction "VCCO_37_E4") (pintype "power_in"))
      (node (ref "IC2") (pin "F1") (pinfunction "VCCO_36_F1") (pintype "power_in"))
      (node (ref "IC2") (pin "F11") (pinfunction "VCCO_37_F11") (pintype "power_in"))
      (node (ref "IC2") (pin "G33") (pinfunction "VCCO_16_G33") (pintype "power_in"))
      (node (ref "IC2") (pin "G8") (pinfunction "VCCO_36_G8") (pintype "power_in"))
      (node (ref "IC2") (pin "H30") (pinfunction "VCCO_16_H30") (pintype "power_in"))
      (node (ref "IC2") (pin "H5") (pinfunction "VCCO_36_H5") (pintype "power_in"))
      (node (ref "IC2") (pin "J12") (pinfunction "VCCO_36_J12") (pintype "power_in"))
      (node (ref "IC2") (pin "J2") (pinfunction "VCCO_36_J2") (pintype "power_in"))
      (node (ref "IC2") (pin "J27") (pinfunction "VCCO_16_J27") (pintype "power_in"))
      (node (ref "IC2") (pin "K24") (pinfunction "VCCO_16_K24") (pintype "power_in"))
      (node (ref "IC2") (pin "K34") (pinfunction "VCCO_16_K34") (pintype "power_in"))
      (node (ref "IC2") (pin "K9") (pinfunction "VCCO_36_K9") (pintype "power_in"))
      (node (ref "IC2") (pin "L31") (pinfunction "VCCO_16_L31") (pintype "power_in"))
      (node (ref "IC2") (pin "L6") (pinfunction "VCCO_36_L6") (pintype "power_in"))
      (node (ref "IC2") (pin "M3") (pinfunction "VCCO_35_M3") (pintype "power_in"))
      (node (ref "IC2") (pin "N10") (pinfunction "VCCO_35_N10") (pintype "power_in"))
      (node (ref "IC2") (pin "P7") (pinfunction "VCCO_35_P7") (pintype "power_in"))
      (node (ref "IC2") (pin "R4") (pinfunction "VCCO_35_R4") (pintype "power_in"))
      (node (ref "IC2") (pin "T1") (pinfunction "VCCO_35_T1") (pintype "power_in"))
      (node (ref "IC2") (pin "U8") (pinfunction "VCCO_35_U8") (pintype "power_in"))
      (node (ref "IC2") (pin "V5") (pinfunction "VCCO_34_V5") (pintype "power_in"))
      (node (ref "IC2") (pin "W2") (pinfunction "VCCO_34_W2") (pintype "power_in"))
      (node (ref "IC2") (pin "Y9") (pinfunction "VCCO_34_Y9") (pintype "power_in"))
    )
    (net (code "13") (name "PVADJ2") (class "Default")
      (node (ref "C644") (pin "2") (pinfunction "2_2") (pintype "passive"))
      (node (ref "C645") (pin "2") (pinfunction "2_2") (pintype "passive"))
      (node (ref "C646") (pin "2") (pinfunction "2_2") (pintype "passive"))
      (node (ref "C647") (pin "2") (pinfunction "2_2") (pintype "passive"))
      (node (ref "C648") (pin "2") (pinfunction "2_2") (pintype "passive"))
      (node (ref "C649") (pin "2") (pinfunction "2_2") (pintype "passive"))
      (node (ref "C650") (pin "2") (pinfunction "2_2") (pintype "passive"))
      (node (ref "C651") (pin "2") (pinfunction "2_2") (pintype "passive"))
      (node (ref "C652") (pin "2") (pinfunction "2_2") (pintype "passive"))
      (node (ref "C653") (pin "2") (pinfunction "2_2") (pintype "passive"))
      (node (ref "C654") (pin "2") (pinfunction "2_2") (pintype "passive"))
      (node (ref "C655") (pin "2") (pinfunction "2_2") (pintype "passive"))
      (node (ref "C656") (pin "2") (pinfunction "2_2") (pintype "passive"))
      (node (ref "C657") (pin "2") (pinfunction "2_2") (pintype "passive"))
      (node (ref "C658") (pin "2") (pinfunction "2_2") (pintype "passive"))
      (node (ref "C659") (pin "2") (pinfunction "2_2") (pintype "passive"))
      (node (ref "C660") (pin "2") (pinfunction "2_2") (pintype "passive"))
      (node (ref "C661") (pin "2") (pinfunction "2_2") (pintype "passive"))
      (node (ref "C662") (pin "2") (pinfunction "2_2") (pintype "passive"))
      (node (ref "C663") (pin "2") (pinfunction "2_2") (pintype "passive"))
      (node (ref "C664") (pin "2") (pinfunction "2_2") (pintype "passive"))
      (node (ref "C665") (pin "2") (pinfunction "2_2") (pintype "passive"))
      (node (ref "C666") (pin "2") (pinfunction "2_2") (pintype "passive"))
      (node (ref "C667") (pin "2") (pinfunction "2_2") (pintype "passive"))
      (node (ref "C668") (pin "2") (pinfunction "2_2") (pintype "passive"))
      (node (ref "C669") (pin "2") (pinfunction "2_2") (pintype "passive"))
      (node (ref "C670") (pin "2") (pinfunction "2_2") (pintype "passive"))
      (node (ref "C671") (pin "2") (pinfunction "2_2") (pintype "passive"))
      (node (ref "C672") (pin "2") (pinfunction "2_2") (pintype "passive"))
      (node (ref "C673") (pin "2") (pinfunction "2_2") (pintype "passive"))
      (node (ref "C674") (pin "2") (pinfunction "2_2") (pintype "passive"))
      (node (ref "C675") (pin "2") (pinfunction "2_2") (pintype "passive"))
      (node (ref "C712") (pin "1") (pinfunction "1_1") (pintype "passive"))
      (node (ref "C713") (pin "1") (pinfunction "1_1") (pintype "passive"))
      (node (ref "C714") (pin "1") (pinfunction "1_1") (pintype "passive"))
      (node (ref "C715") (pin "1") (pinfunction "1_1") (pintype "passive"))
      (node (ref "C716") (pin "2") (pinfunction "2_2") (pintype "passive"))
      (node (ref "C717") (pin "2") (pinfunction "2_2") (pintype "passive"))
      (node (ref "C718") (pin "2") (pinfunction "2_2") (pintype "passive"))
      (node (ref "IC2") (pin "A31") (pinfunction "VCCO_17_A31") (pintype "power_in"))
      (node (ref "IC2") (pin "AA31") (pinfunction "VCCO_14_AA31") (pintype "power_in"))
      (node (ref "IC2") (pin "AB28") (pinfunction "VCCO_14_AB28") (pintype "power_in"))
      (node (ref "IC2") (pin "AC25") (pinfunction "VCCO_13_AC25") (pintype "power_in"))
      (node (ref "IC2") (pin "AD32") (pinfunction "VCCO_13_AD32") (pintype "power_in"))
      (node (ref "IC2") (pin "AE29") (pinfunction "VCCO_13_AE29") (pintype "power_in"))
      (node (ref "IC2") (pin "AF26") (pinfunction "VCCO_13_AF26") (pintype "power_in"))
      (node (ref "IC2") (pin "AG33") (pinfunction "VCCO_13_AG33") (pintype "power_in"))
      (node (ref "IC2") (pin "AH30") (pinfunction "VCCO_13_AH30") (pintype "power_in"))
      (node (ref "IC2") (pin "AJ27") (pinfunction "VCCO_12_AJ27") (pintype "power_in"))
      (node (ref "IC2") (pin "AK34") (pinfunction "VCCO_12_AK34") (pintype "power_in"))
      (node (ref "IC2") (pin "AL31") (pinfunction "VCCO_12_AL31") (pintype "power_in"))
      (node (ref "IC2") (pin "AM28") (pinfunction "VCCO_12_AM28") (pintype "power_in"))
      (node (ref "IC2") (pin "AN25") (pinfunction "VCCO_12_AN25") (pintype "power_in"))
      (node (ref "IC2") (pin "AP32") (pinfunction "VCCO_12_AP32") (pintype "power_in"))
      (node (ref "IC2") (pin "B28") (pinfunction "VCCO_17_B28") (pintype "power_in"))
      (node (ref "IC2") (pin "C25") (pinfunction "VCCO_17_C25") (pintype "power_in"))
      (node (ref "IC2") (pin "D32") (pinfunction "VCCO_17_D32") (pintype "power_in"))
      (node (ref "IC2") (pin "E29") (pinfunction "VCCO_17_E29") (pintype "power_in"))
      (node (ref "IC2") (pin "F26") (pinfunction "VCCO_17_F26") (pintype "power_in"))
      (node (ref "IC2") (pin "M28") (pinfunction "VCCO_15_M28") (pintype "power_in"))
      (node (ref "IC2") (pin "N25") (pinfunction "VCCO_15_N25") (pintype "power_in"))
      (node (ref "IC2") (pin "P32") (pinfunction "VCCO_15_P32") (pintype "power_in"))
      (node (ref "IC2") (pin "R29") (pinfunction "VCCO_15_R29") (pintype "power_in"))
      (node (ref "IC2") (pin "T26") (pinfunction "VCCO_15_T26") (pintype "power_in"))
      (node (ref "IC2") (pin "U33") (pinfunction "VCCO_15_U33") (pintype "power_in"))
      (node (ref "IC2") (pin "V30") (pinfunction "VCCO_14_V30") (pintype "power_in"))
      (node (ref "IC2") (pin "W27") (pinfunction "VCCO_14_W27") (pintype "power_in"))
      (node (ref "IC2") (pin "Y24") (pinfunction "VCCO_14_Y24") (pintype "power_in"))
      (node (ref "IC2") (pin "Y34") (pinfunction "VCCO_14_Y34") (pintype "power_in"))
    )
    (net (code "14") (name "VCCAUX") (class "Default")
      (node (ref "C266") (pin "2") (pinfunction "2_2") (pintype "passive"))
      (node (ref "C269") (pin "2") (pinfunction "2_2") (pintype "passive"))
      (node (ref "C270") (pin "2") (pinfunction "2_2") (pintype "passive"))
      (node (ref "C271") (pin "2") (pinfunction "2_2") (pintype "passive"))
      (node (ref "C275") (pin "2") (pinfunction "2_2") (pintype "passive"))
      (node (ref "C276") (pin "2") (pinfunction "2_2") (pintype "passive"))
      (node (ref "C277") (pin "2") (pinfunction "2_2") (pintype "passive"))
      (node (ref "C278") (pin "2") (pinfunction "2_2") (pintype "passive"))
      (node (ref "C279") (pin "2") (pinfunction "2_2") (pintype "passive"))
      (node (ref "C280") (pin "2") (pinfunction "2_2") (pintype "passive"))
      (node (ref "C592") (pin "1") (pinfunction "1_1") (pintype "passive"))
      (node (ref "C593") (pin "1") (pinfunction "1_1") (pintype "passive"))
      (node (ref "C594") (pin "2") (pinfunction "2_2") (pintype "passive"))
      (node (ref "C596") (pin "2") (pinfunction "2_2") (pintype "passive"))
      (node (ref "C597") (pin "2") (pinfunction "2_2") (pintype "passive"))
      (node (ref "C598") (pin "2") (pinfunction "2_2") (pintype "passive"))
      (node (ref "C614") (pin "2") (pinfunction "2_2") (pintype "passive"))
      (node (ref "C738") (pin "2") (pinfunction "2_2") (pintype "passive"))
      (node (ref "C739") (pin "2") (pinfunction "2_2") (pintype "passive"))
      (node (ref "IC2") (pin "AA13") (pinfunction "VCCAUX_AA13") (pintype "power_in"))
      (node (ref "IC2") (pin "AA23") (pinfunction "VCCAUX_AA23") (pintype "power_in"))
      (node (ref "IC2") (pin "AB12") (pinfunction "VCCAUX_AB12") (pintype "power_in"))
      (node (ref "IC2") (pin "AB22") (pinfunction "VCCAUX_AB22") (pintype "power_in"))
      (node (ref "IC2") (pin "AC13") (pinfunction "VCCAUX_AC13") (pintype "power_in"))
      (node (ref "IC2") (pin "AC23") (pinfunction "VCCAUX_AC23") (pintype "power_in"))
      (node (ref "IC2") (pin "AD12") (pinfunction "VCCAUX_AD12") (pintype "power_in"))
      (node (ref "IC2") (pin "M22") (pinfunction "VCCAUX_M22") (pintype "power_in"))
      (node (ref "IC2") (pin "N13") (pinfunction "VCCAUX_N13") (pintype "power_in"))
      (node (ref "IC2") (pin "N23") (pinfunction "VCCAUX_N23") (pintype "power_in"))
      (node (ref "IC2") (pin "P12") (pinfunction "VCCAUX_P12") (pintype "power_in"))
      (node (ref "IC2") (pin "P22") (pinfunction "VCCAUX_P22") (pintype "power_in"))
      (node (ref "IC2") (pin "R13") (pinfunction "VCCAUX_R13") (pintype "power_in"))
      (node (ref "IC2") (pin "R23") (pinfunction "VCCAUX_R23") (pintype "power_in"))
      (node (ref "IC2") (pin "T12") (pinfunction "VCCAUX_T12") (pintype "power_in"))
      (node (ref "IC2") (pin "T18") (pinfunction "VCCADC_0_T18") (pintype "power_in"))
      (node (ref "IC2") (pin "T22") (pinfunction "VCCAUX_T22") (pintype "power_in"))
      (node (ref "IC2") (pin "U13") (pinfunction "VCCAUX_U13") (pintype "power_in"))
      (node (ref "IC2") (pin "U23") (pinfunction "VCCAUX_U23") (pintype "power_in"))
      (node (ref "IC2") (pin "V12") (pinfunction "VCCAUX_V12") (pintype "power_in"))
      (node (ref "IC2") (pin "V22") (pinfunction "VCCAUX_V22") (pintype "power_in"))
      (node (ref "IC2") (pin "W13") (pinfunction "VCCAUX_W13") (pintype "power_in"))
      (node (ref "IC2") (pin "W23") (pinfunction "VCCAUX_W23") (pintype "power_in"))
      (node (ref "IC2") (pin "Y12") (pinfunction "VCCAUX_Y12") (pintype "power_in"))
      (node (ref "IC2") (pin "Y22") (pinfunction "VCCAUX_Y22") (pintype "power_in"))
      (node (ref "L12") (pin "2") (pintype "passive"))
    )
    (net (code "15") (name "VCCBATT") (class "Default")
      (node (ref "BH1") (pin "pos1") (pinfunction "+_pos1") (pintype "power_in"))
      (node (ref "BH1") (pin "pos2") (pinfunction "+_pos2") (pintype "power_in"))
      (node (ref "C615") (pin "2") (pinfunction "2_2") (pintype "passive"))
      (node (ref "IC2") (pin "K13") (pinfunction "VCCBATT_0_K13") (pintype "power_in"))
    )
    (net (code "16") (name "VCCBRAM") (class "Default")
      (node (ref "C226") (pin "1") (pinfunction "1_1") (pintype "passive"))
      (node (ref "C243") (pin "2") (pinfunction "2_2") (pintype "passive"))
      (node (ref "C244") (pin "2") (pinfunction "2_2") (pintype "passive"))
      (node (ref "C245") (pin "2") (pinfunction "2_2") (pintype "passive"))
      (node (ref "C246") (pin "2") (pinfunction "2_2") (pintype "passive"))
      (node (ref "C247") (pin "2") (pinfunction "2_2") (pintype "passive"))
      (node (ref "C248") (pin "2") (pinfunction "2_2") (pintype "passive"))
      (node (ref "C249") (pin "2") (pinfunction "2_2") (pintype "passive"))
      (node (ref "C250") (pin "2") (pinfunction "2_2") (pintype "passive"))
      (node (ref "C264") (pin "2") (pinfunction "2_2") (pintype "passive"))
      (node (ref "C265") (pin "2") (pinfunction "2_2") (pintype "passive"))
      (node (ref "C587") (pin "1") (pinfunction "1_1") (pintype "passive"))
      (node (ref "C588") (pin "2") (pinfunction "2_2") (pintype "passive"))
      (node (ref "C589") (pin "2") (pinfunction "2_2") (pintype "passive"))
      (node (ref "C591") (pin "2") (pinfunction "2_2") (pintype "passive"))
      (node (ref "IC2") (pin "AA21") (pinfunction "VCCBRAM_AA21") (pintype "power_in"))
      (node (ref "IC2") (pin "AB20") (pinfunction "VCCBRAM_AB20") (pintype "power_in"))
      (node (ref "IC2") (pin "AC21") (pinfunction "VCCBRAM_AC21") (pintype "power_in"))
      (node (ref "IC2") (pin "M20") (pinfunction "VCCBRAM_M20") (pintype "power_in"))
      (node (ref "IC2") (pin "N21") (pinfunction "VCCBRAM_N21") (pintype "power_in"))
      (node (ref "IC2") (pin "P20") (pinfunction "VCCBRAM_P20") (pintype "power_in"))
      (node (ref "IC2") (pin "R21") (pinfunction "VCCBRAM_R21") (pintype "power_in"))
      (node (ref "IC2") (pin "T20") (pinfunction "VCCBRAM_T20") (pintype "power_in"))
      (node (ref "IC2") (pin "U21") (pinfunction "VCCBRAM_U21") (pintype "power_in"))
      (node (ref "IC2") (pin "V20") (pinfunction "VCCBRAM_V20") (pintype "power_in"))
      (node (ref "IC2") (pin "W21") (pinfunction "VCCBRAM_W21") (pintype "power_in"))
      (node (ref "IC2") (pin "Y20") (pinfunction "VCCBRAM_Y20") (pintype "power_in"))
      (node (ref "L10") (pin "2") (pintype "passive"))
    )
    (net (code "17") (name "unconnected-(IC2R-VN_0-PadV17)") (class "Default")
      (node (ref "IC2") (pin "V17") (pinfunction "VN_0_V17") (pintype "input"))
    )
    (net (code "18") (name "unconnected-(IC2R-VP_0-PadU18)") (class "Default")
      (node (ref "IC2") (pin "U18") (pinfunction "VP_0_U18") (pintype "input"))
    )
  )
)
